# BeagleBone_Black_Wireless.net
KiCad netlist of a schematic drawn in EAGLE
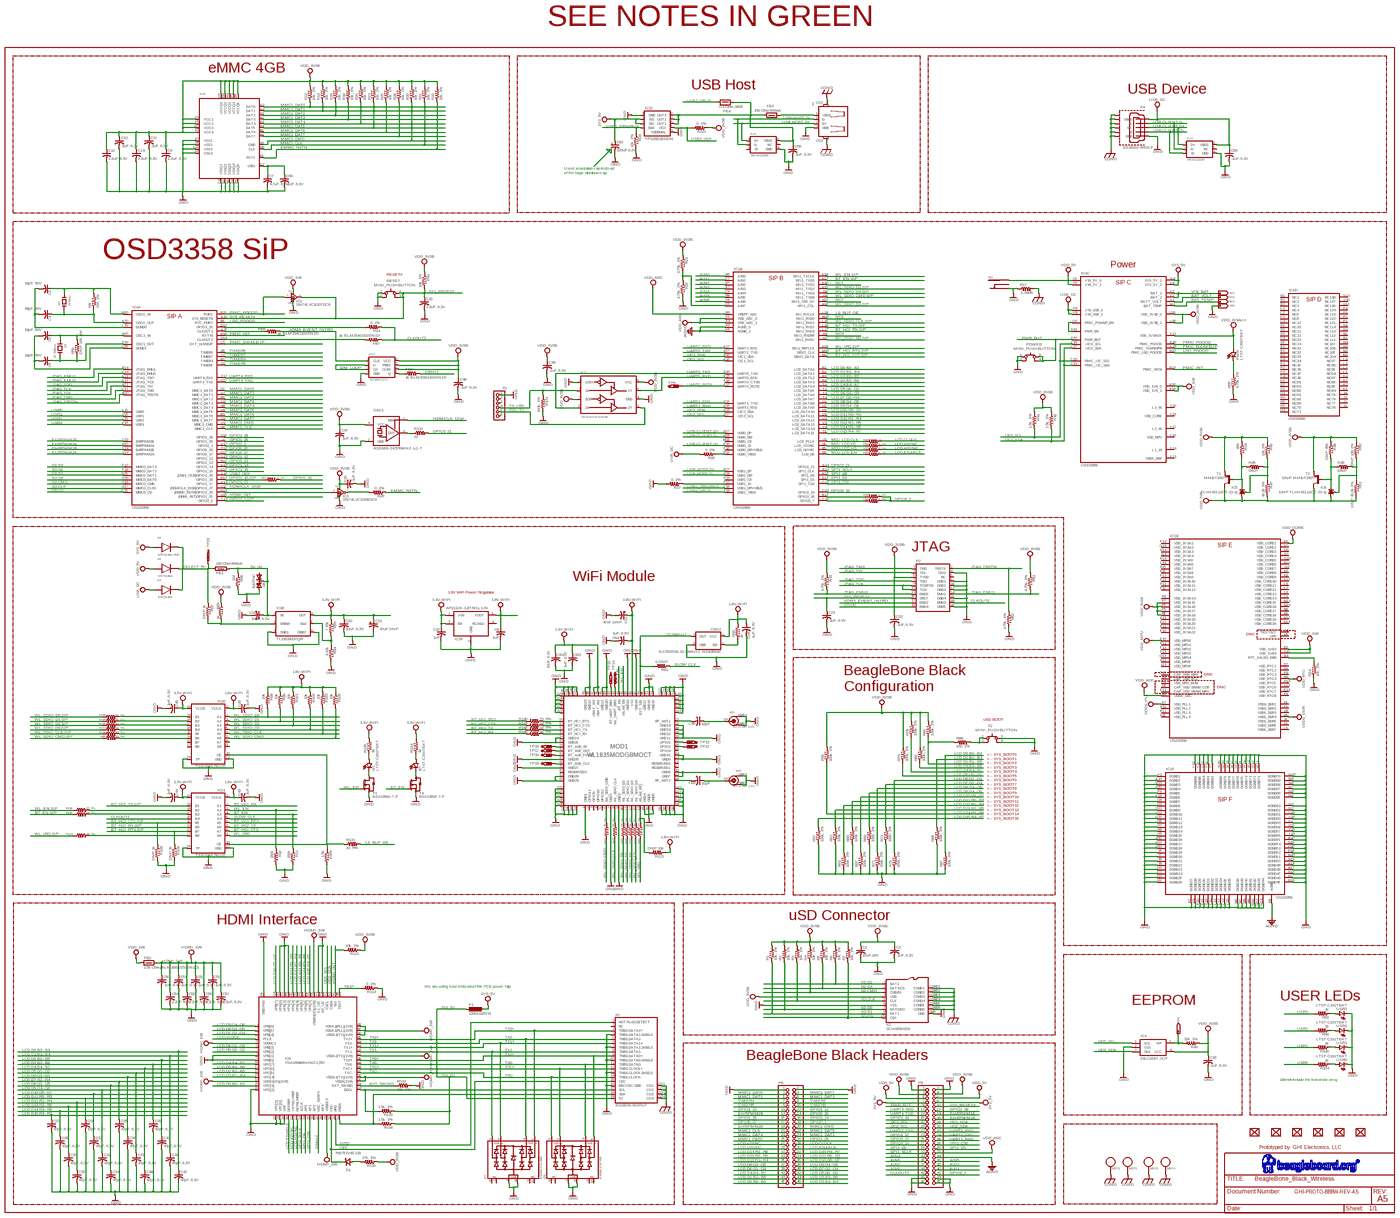
[diagram p0: schematic, sheet 1, overview]
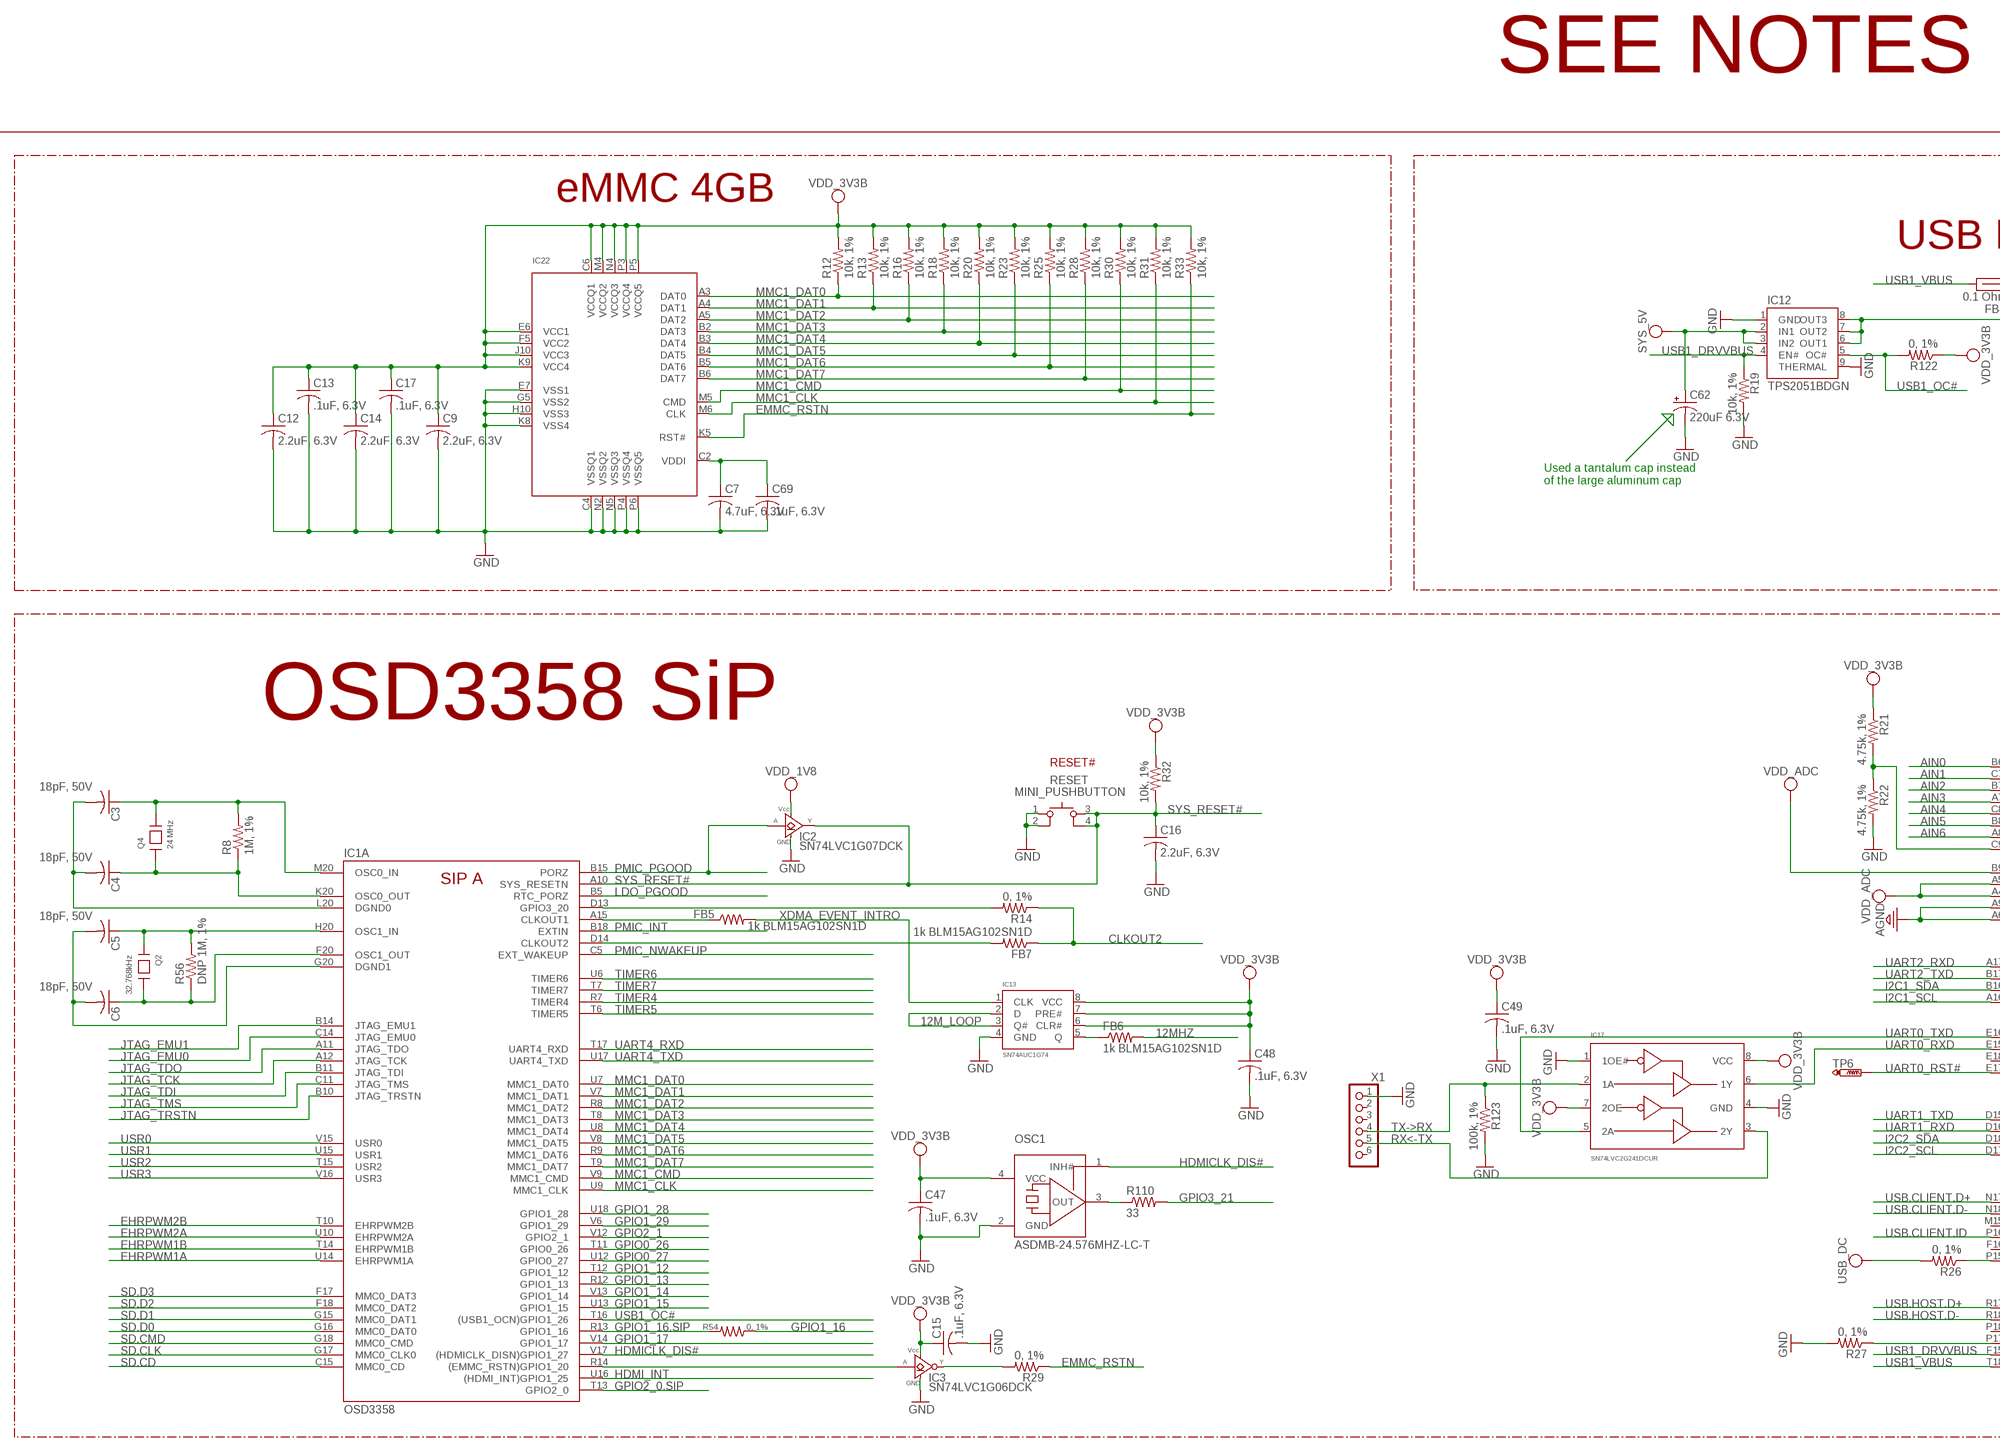
[diagram p1: schematic, sheet 1, part 1 of 4]
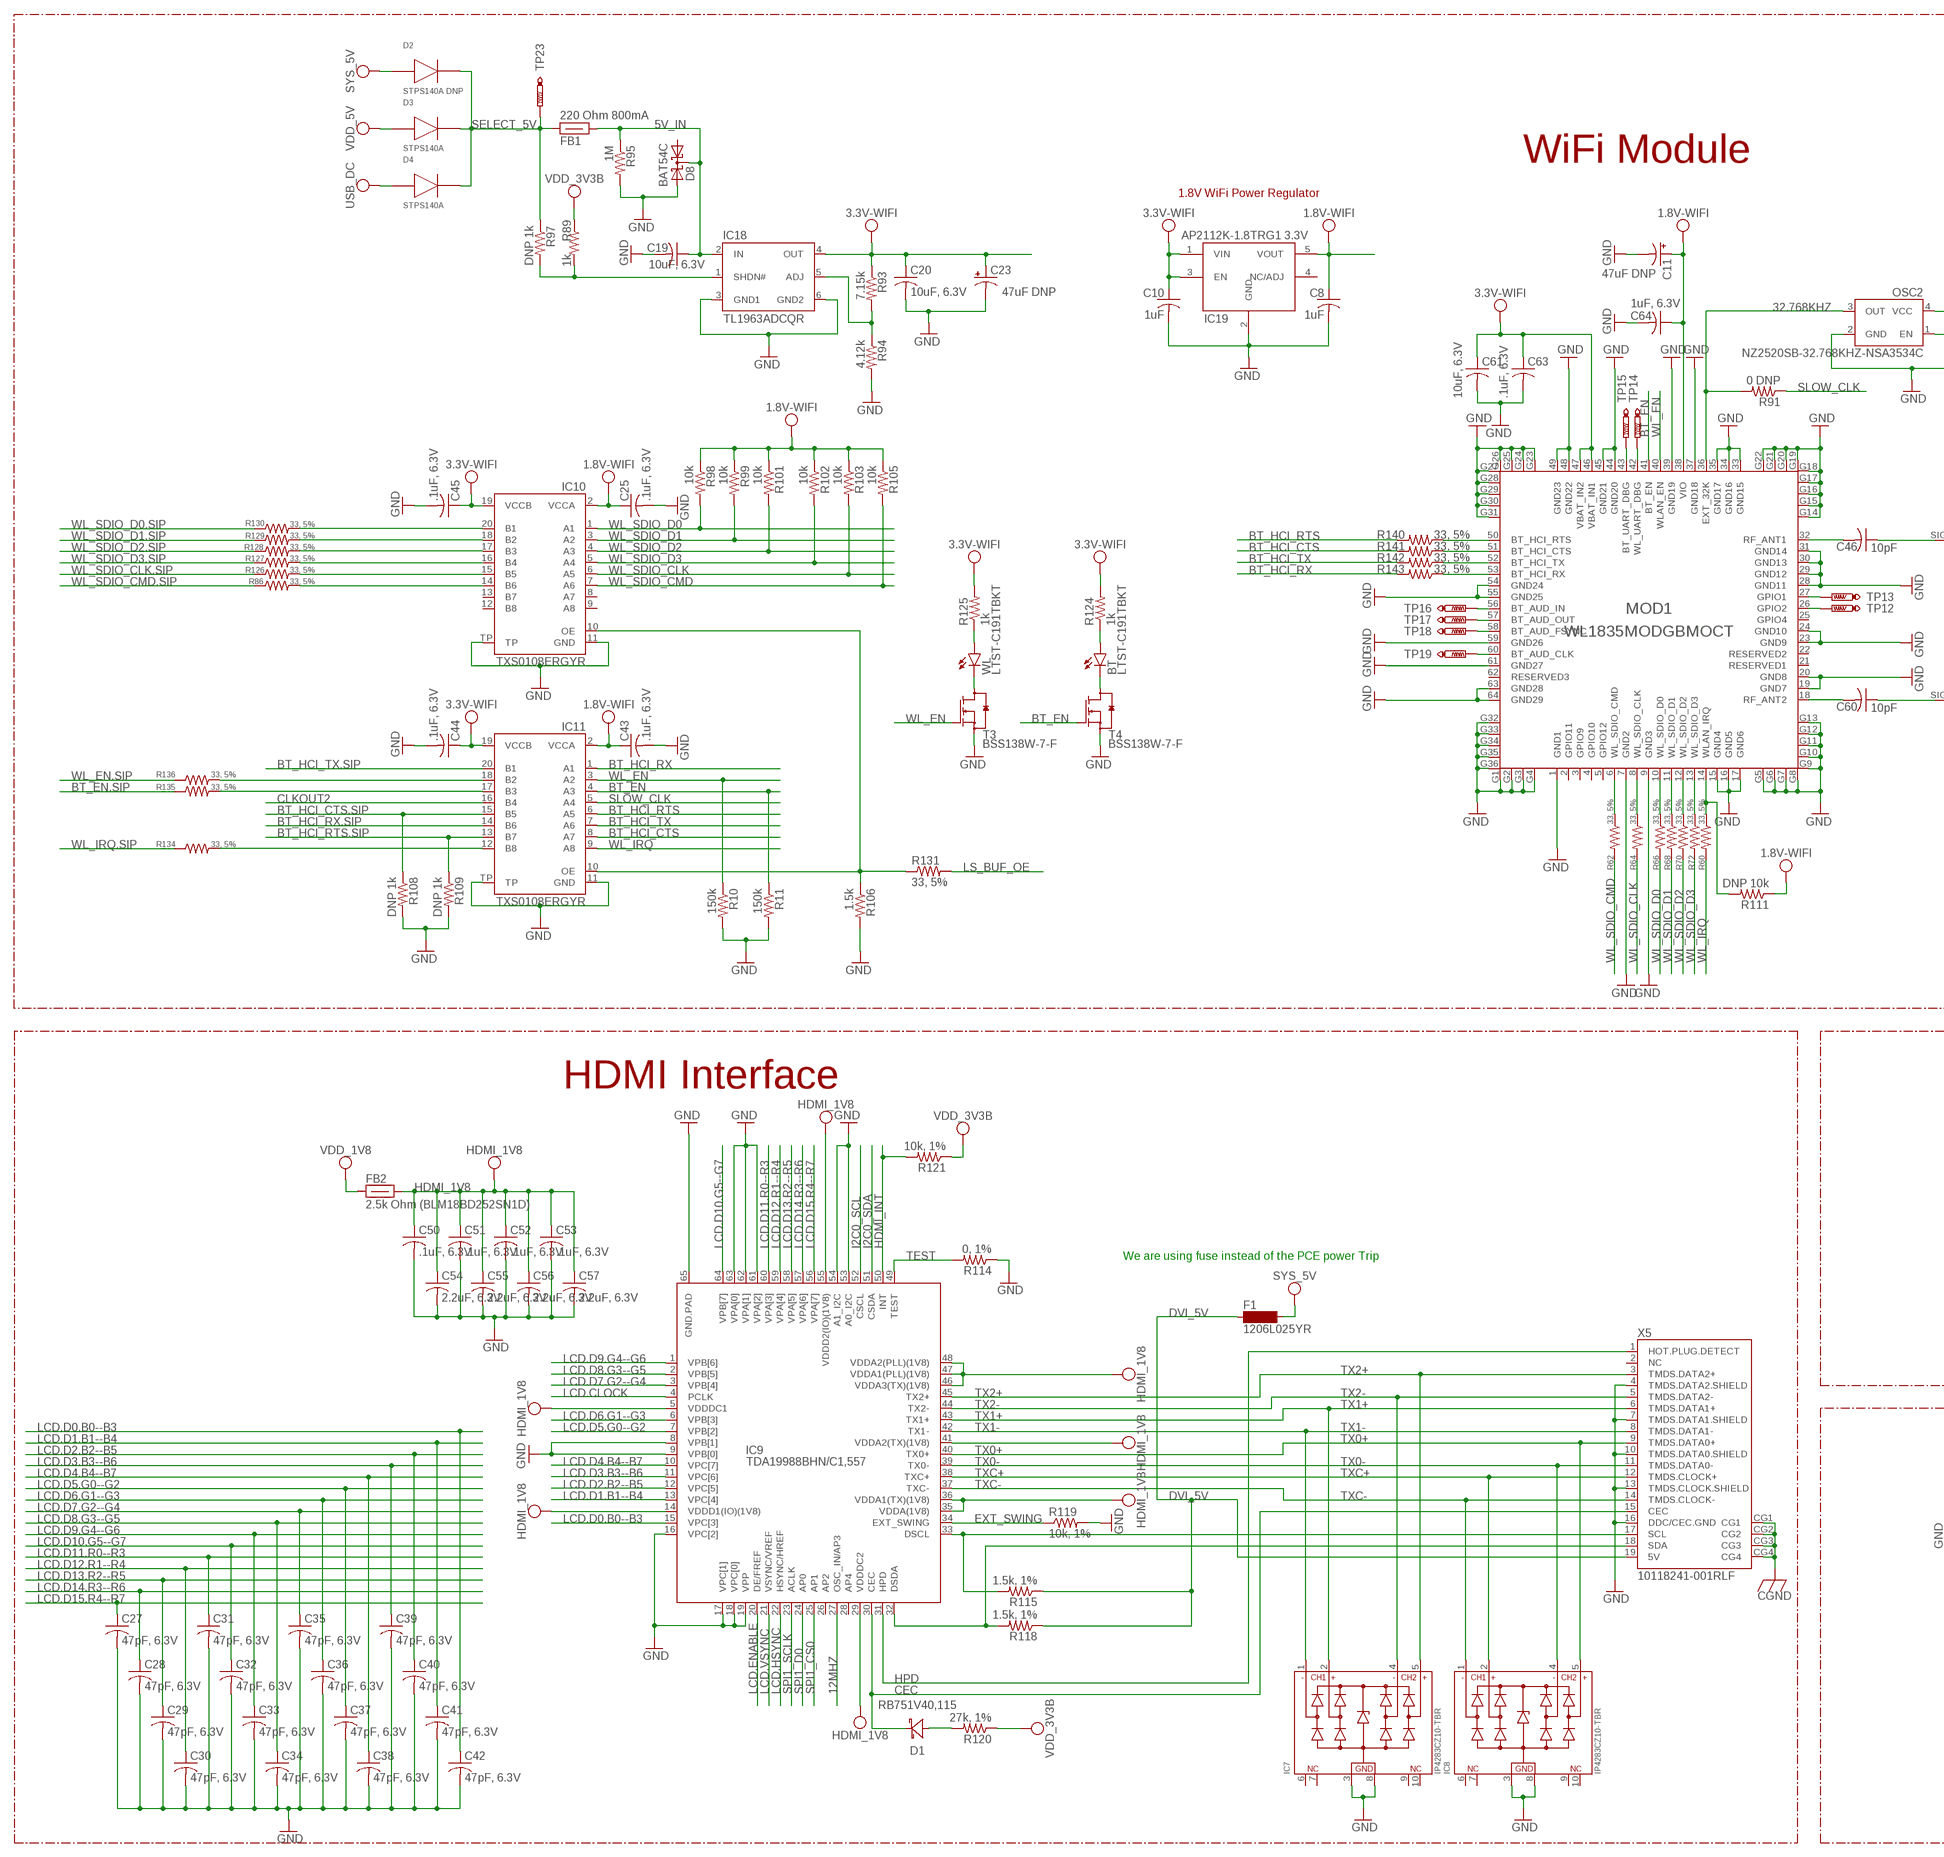
[diagram p2: schematic, sheet 1, part 2 of 4]
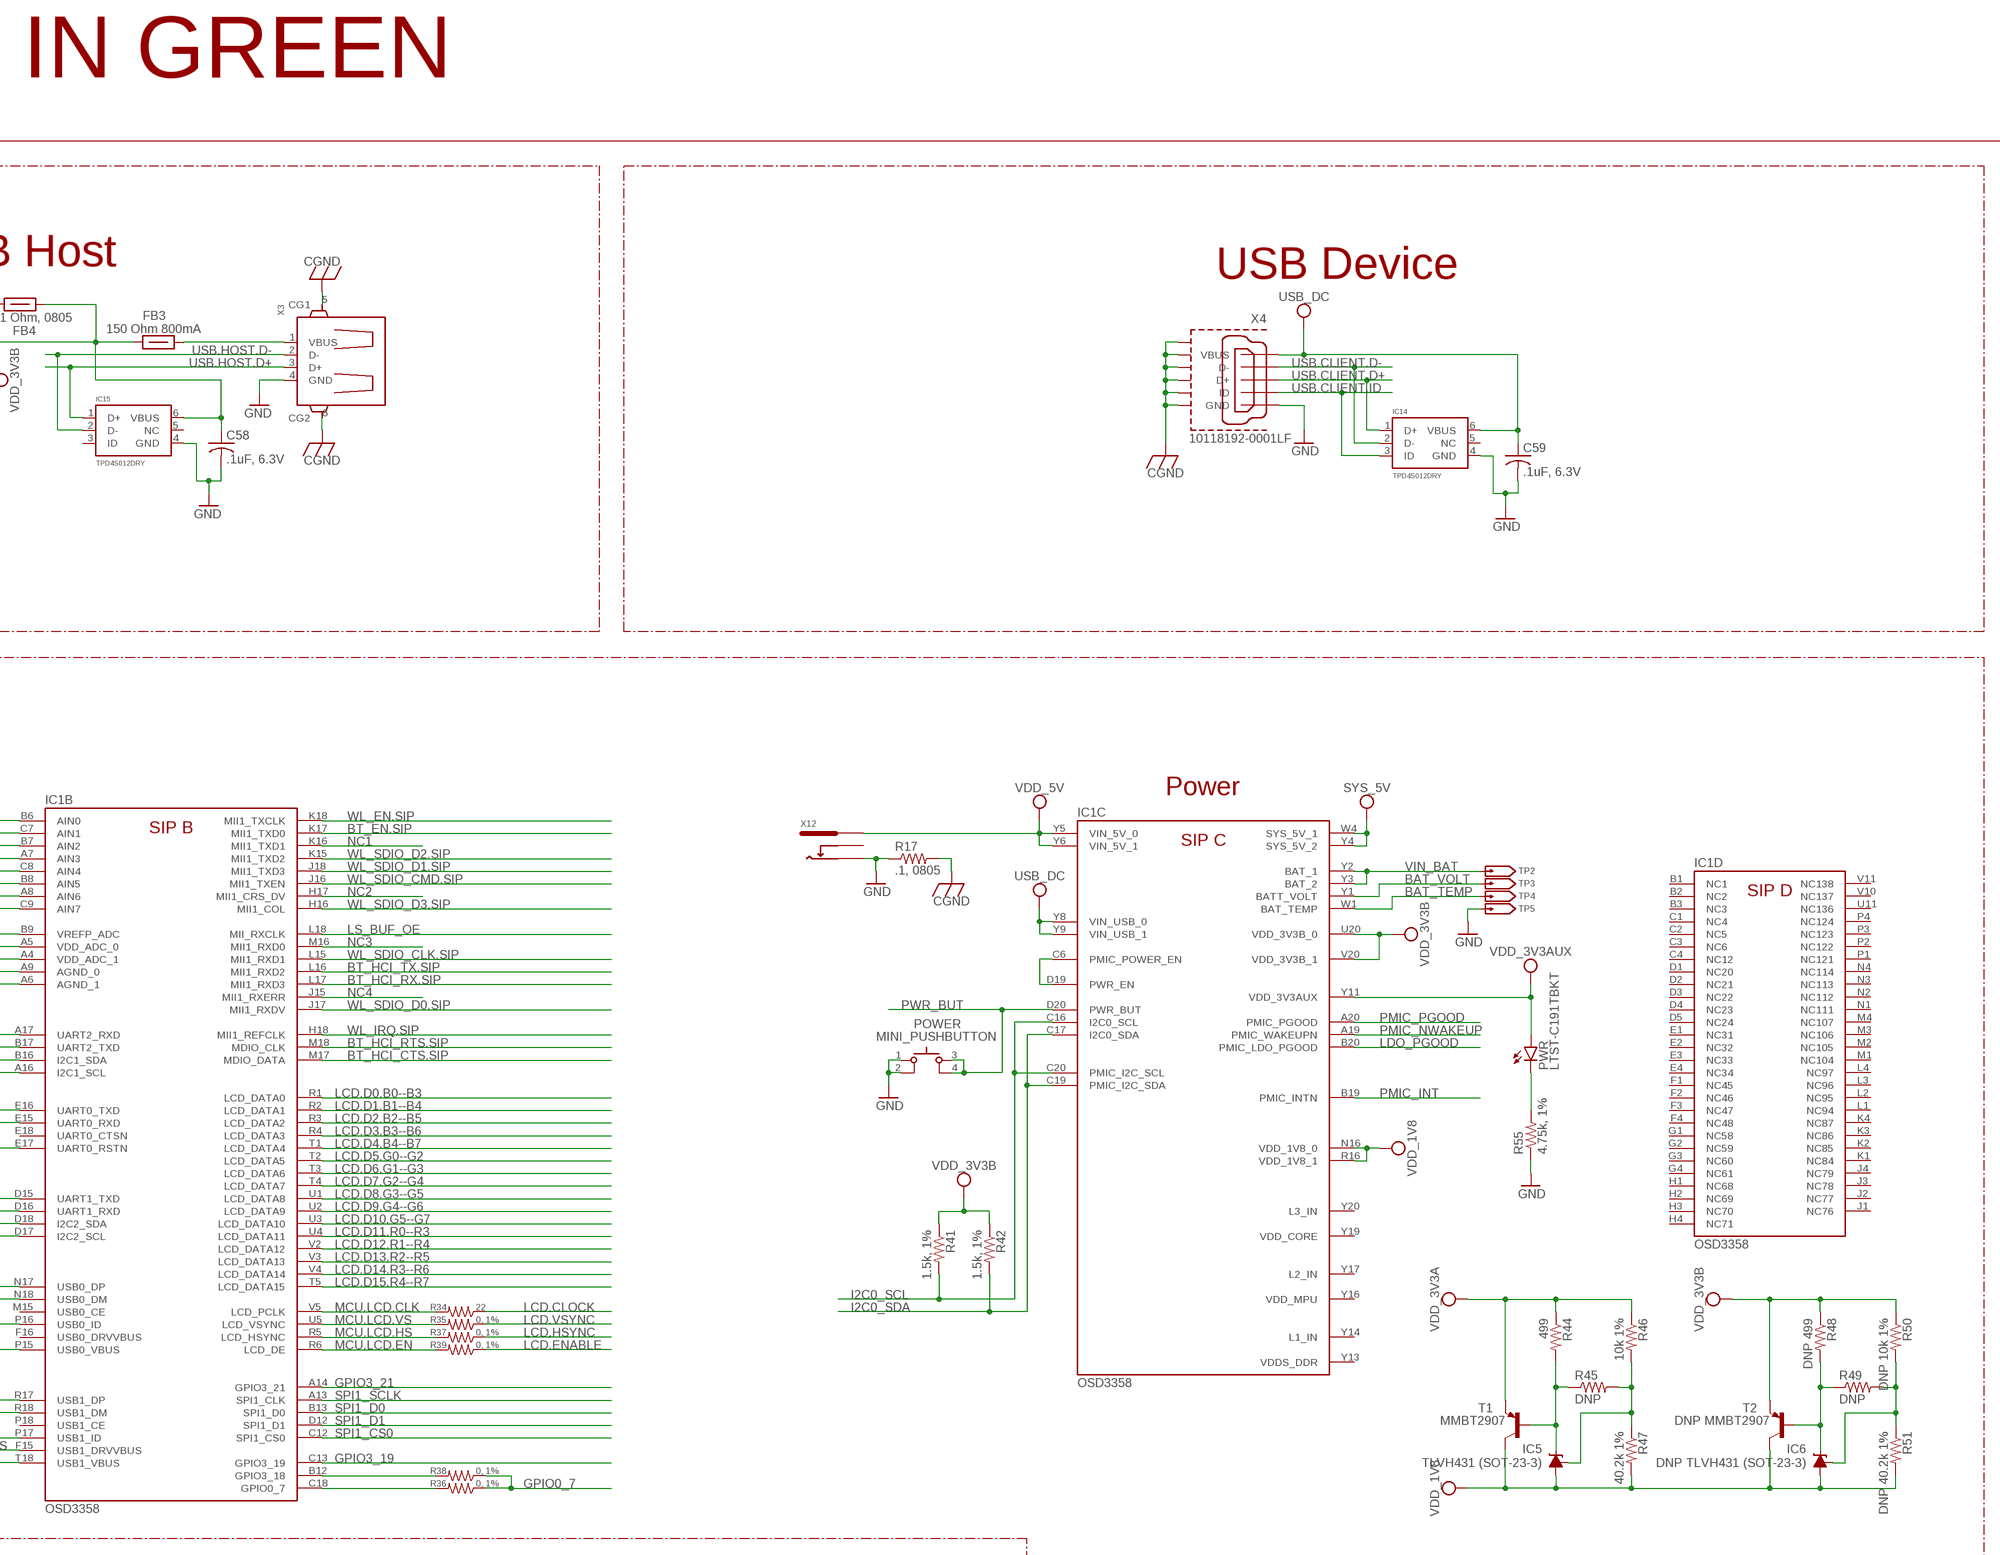
[diagram p3: schematic, sheet 1, part 3 of 4]
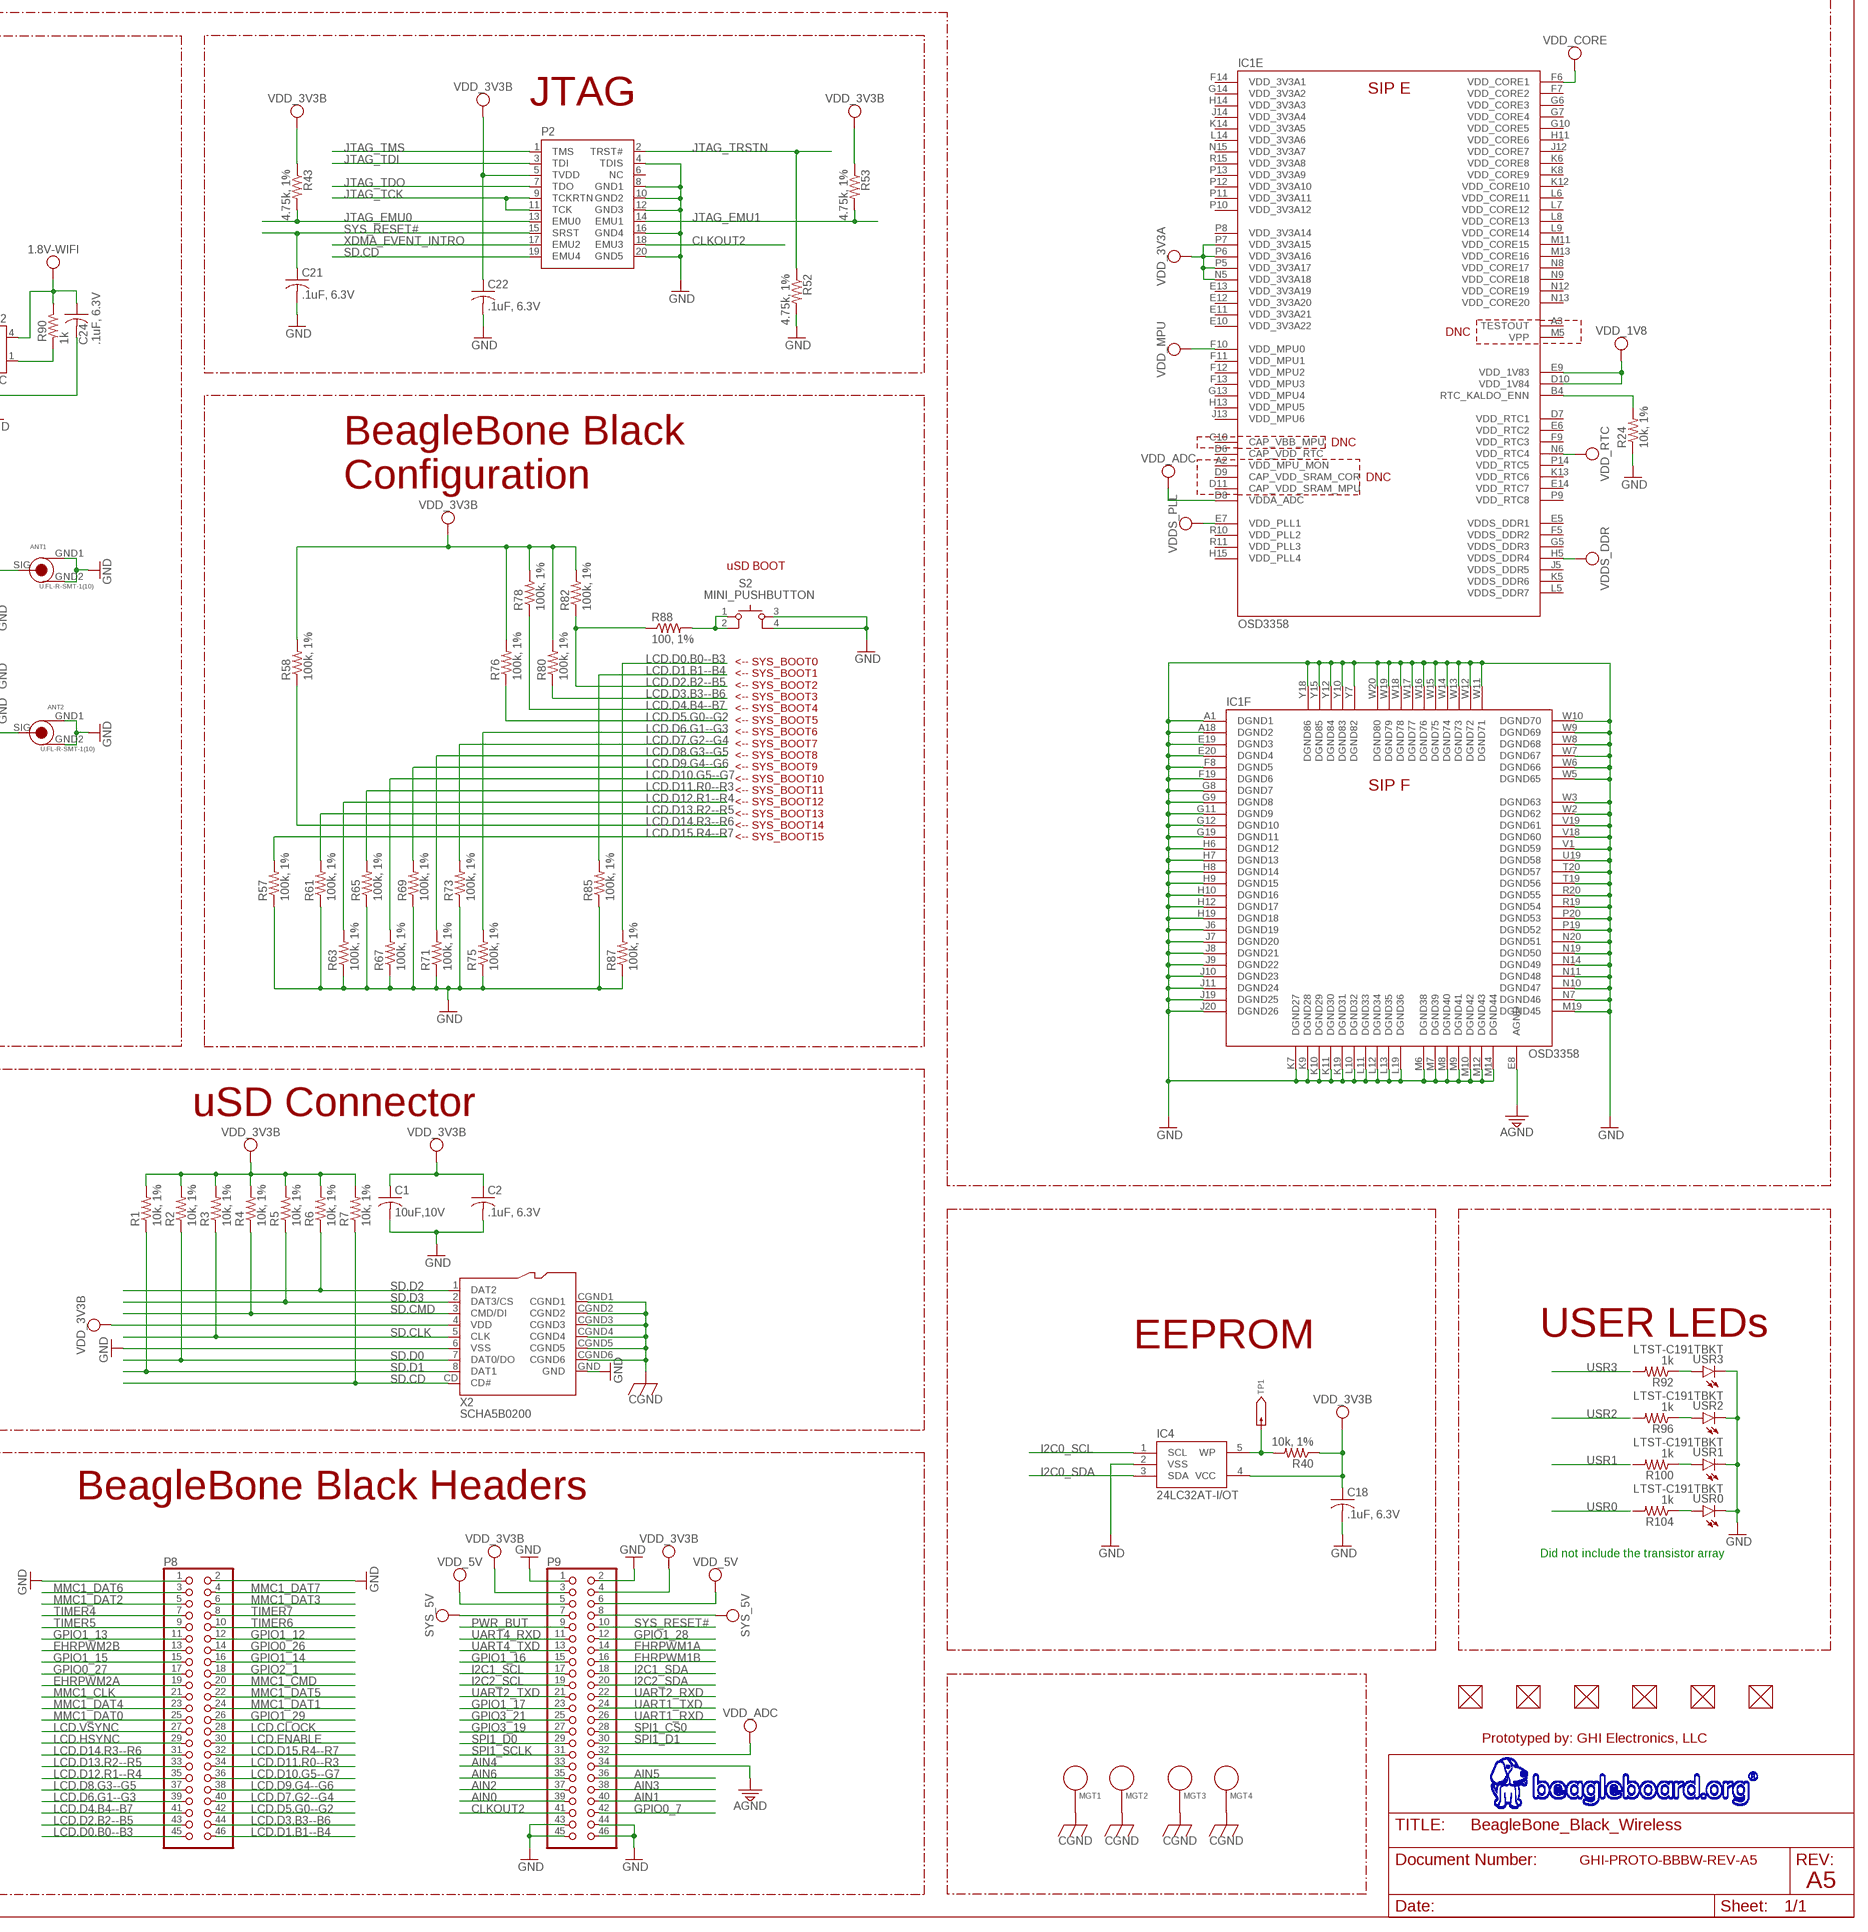
[diagram p4: schematic, sheet 1, part 4 of 4]

(export (version "E")
  (design (tool "Eeschema 10.0.6"))
  (components
    (comp (ref "ANT1")
      (value "U.FL-R-SMT-1(10)")
      (footprint "eagle-import:U.FL-R-SMT-1")
      (libsource (lib "eagle-import") (part "U.FL-R-SMT-1"))
    )
    (comp (ref "ANT2")
      (value "U.FL-R-SMT-1(10)")
      (footprint "eagle-import:U.FL-R-SMT-1")
      (libsource (lib "eagle-import") (part "U.FL-R-SMT-1"))
    )
    (comp (ref "BT")
      (value "LTST-C191TBKT")
      (footprint "eagle-import:0603-LED")
      (libsource (lib "eagle-import") (part "LED-(INCH)-0603"))
    )
    (comp (ref "C1")
      (value "10uF,10V")
      (footprint "eagle-import:C0603K")
      (libsource (lib "eagle-import") (part "C-USC0603K"))
    )
    (comp (ref "C2")
      (value ".1uF, 6.3V")
      (footprint "eagle-import:C0402K")
      (libsource (lib "eagle-import") (part "C-USC0402K"))
    )
    (comp (ref "C3")
      (value "18pF, 50V")
      (footprint "eagle-import:C0402K")
      (libsource (lib "eagle-import") (part "C-USC0402K"))
    )
    (comp (ref "C4")
      (value "18pF, 50V")
      (footprint "eagle-import:C0402K")
      (libsource (lib "eagle-import") (part "C-USC0402K"))
    )
    (comp (ref "C5")
      (value "18pF, 50V")
      (footprint "eagle-import:C0402K")
      (libsource (lib "eagle-import") (part "C-USC0402K"))
    )
    (comp (ref "C6")
      (value "18pF, 50V")
      (footprint "eagle-import:C0402K")
      (libsource (lib "eagle-import") (part "C-USC0402K"))
    )
    (comp (ref "C7")
      (value "4.7uF, 6.3V")
      (footprint "eagle-import:C0805K")
      (libsource (lib "eagle-import") (part "C-USC0805K"))
    )
    (comp (ref "C8")
      (value "1uF")
      (footprint "eagle-import:C0402K")
      (libsource (lib "eagle-import") (part "C-USC0402K"))
    )
    (comp (ref "C9")
      (value "2.2uF, 6.3V")
      (footprint "eagle-import:C0805K")
      (libsource (lib "eagle-import") (part "C-USC0805K"))
    )
    (comp (ref "C10")
      (value "1uF")
      (footprint "eagle-import:C0402K")
      (libsource (lib "eagle-import") (part "C-USC0402K"))
    )
    (comp (ref "C11")
      (value "47uF DNP")
      (footprint "eagle-import:CT3528")
      (libsource (lib "eagle-import") (part "CPOL-USCT3528"))
    )
    (comp (ref "C12")
      (value "2.2uF, 6.3V")
      (footprint "eagle-import:C0805K")
      (libsource (lib "eagle-import") (part "C-USC0805K"))
    )
    (comp (ref "C13")
      (value ".1uF, 6.3V")
      (footprint "eagle-import:C0402K")
      (libsource (lib "eagle-import") (part "C-USC0402K"))
    )
    (comp (ref "C14")
      (value "2.2uF, 6.3V")
      (footprint "eagle-import:C0805K")
      (libsource (lib "eagle-import") (part "C-USC0805K"))
    )
    (comp (ref "C15")
      (value ".1uF, 6.3V")
      (footprint "eagle-import:C0402K")
      (libsource (lib "eagle-import") (part "C-USC0402K"))
    )
    (comp (ref "C16")
      (value "2.2uF, 6.3V")
      (footprint "eagle-import:C0603K")
      (libsource (lib "eagle-import") (part "C-USC0603K"))
    )
    (comp (ref "C17")
      (value ".1uF, 6.3V")
      (footprint "eagle-import:C0402K")
      (libsource (lib "eagle-import") (part "C-USC0402K"))
    )
    (comp (ref "C18")
      (value ".1uF, 6.3V")
      (footprint "eagle-import:C0402K")
      (libsource (lib "eagle-import") (part "C-USC0402K"))
    )
    (comp (ref "C19")
      (value "10uF, 6.3V")
      (footprint "eagle-import:C0603K")
      (libsource (lib "eagle-import") (part "C-USC0603K"))
    )
    (comp (ref "C20")
      (value "10uF, 6.3V")
      (footprint "eagle-import:C0603K")
      (libsource (lib "eagle-import") (part "C-USC0603K"))
    )
    (comp (ref "C21")
      (value ".1uF, 6.3V")
      (footprint "eagle-import:C0402K")
      (libsource (lib "eagle-import") (part "C-USC0402K"))
    )
    (comp (ref "C22")
      (value ".1uF, 6.3V")
      (footprint "eagle-import:C0402K")
      (libsource (lib "eagle-import") (part "C-USC0402K"))
    )
    (comp (ref "C23")
      (value "47uF DNP")
      (footprint "eagle-import:CT3528")
      (libsource (lib "eagle-import") (part "CPOL-USCT3528"))
    )
    (comp (ref "C24")
      (value ".1uF, 6.3V")
      (footprint "eagle-import:C0402K")
      (libsource (lib "eagle-import") (part "C-USC0402K"))
    )
    (comp (ref "C25")
      (value ".1uF, 6.3V")
      (footprint "eagle-import:C0402K")
      (libsource (lib "eagle-import") (part "C-USC0402K"))
    )
    (comp (ref "C27")
      (value "47pF, 6.3V")
      (footprint "eagle-import:C0402K")
      (libsource (lib "eagle-import") (part "C-USC0402K"))
    )
    (comp (ref "C28")
      (value "47pF, 6.3V")
      (footprint "eagle-import:C0402K")
      (libsource (lib "eagle-import") (part "C-USC0402K"))
    )
    (comp (ref "C29")
      (value "47pF, 6.3V")
      (footprint "eagle-import:C0402K")
      (libsource (lib "eagle-import") (part "C-USC0402K"))
    )
    (comp (ref "C30")
      (value "47pF, 6.3V")
      (footprint "eagle-import:C0402K")
      (libsource (lib "eagle-import") (part "C-USC0402K"))
    )
    (comp (ref "C31")
      (value "47pF, 6.3V")
      (footprint "eagle-import:C0402K")
      (libsource (lib "eagle-import") (part "C-USC0402K"))
    )
    (comp (ref "C32")
      (value "47pF, 6.3V")
      (footprint "eagle-import:C0402K")
      (libsource (lib "eagle-import") (part "C-USC0402K"))
    )
    (comp (ref "C33")
      (value "47pF, 6.3V")
      (footprint "eagle-import:C0402K")
      (libsource (lib "eagle-import") (part "C-USC0402K"))
    )
    (comp (ref "C34")
      (value "47pF, 6.3V")
      (footprint "eagle-import:C0402K")
      (libsource (lib "eagle-import") (part "C-USC0402K"))
    )
    (comp (ref "C35")
      (value "47pF, 6.3V")
      (footprint "eagle-import:C0402K")
      (libsource (lib "eagle-import") (part "C-USC0402K"))
    )
    (comp (ref "C36")
      (value "47pF, 6.3V")
      (footprint "eagle-import:C0402K")
      (libsource (lib "eagle-import") (part "C-USC0402K"))
    )
    (comp (ref "C37")
      (value "47pF, 6.3V")
      (footprint "eagle-import:C0402K")
      (libsource (lib "eagle-import") (part "C-USC0402K"))
    )
    (comp (ref "C38")
      (value "47pF, 6.3V")
      (footprint "eagle-import:C0402K")
      (libsource (lib "eagle-import") (part "C-USC0402K"))
    )
    (comp (ref "C39")
      (value "47pF, 6.3V")
      (footprint "eagle-import:C0402K")
      (libsource (lib "eagle-import") (part "C-USC0402K"))
    )
    (comp (ref "C40")
      (value "47pF, 6.3V")
      (footprint "eagle-import:C0402K")
      (libsource (lib "eagle-import") (part "C-USC0402K"))
    )
    (comp (ref "C41")
      (value "47pF, 6.3V")
      (footprint "eagle-import:C0402K")
      (libsource (lib "eagle-import") (part "C-USC0402K"))
    )
    (comp (ref "C42")
      (value "47pF, 6.3V")
      (footprint "eagle-import:C0402K")
      (libsource (lib "eagle-import") (part "C-USC0402K"))
    )
    (comp (ref "C43")
      (value ".1uF, 6.3V")
      (footprint "eagle-import:C0402K")
      (libsource (lib "eagle-import") (part "C-USC0402K"))
    )
    (comp (ref "C44")
      (value ".1uF, 6.3V")
      (footprint "eagle-import:C0402K")
      (libsource (lib "eagle-import") (part "C-USC0402K"))
    )
    (comp (ref "C45")
      (value ".1uF, 6.3V")
      (footprint "eagle-import:C0402K")
      (libsource (lib "eagle-import") (part "C-USC0402K"))
    )
    (comp (ref "C46")
      (value "10pF")
      (footprint "eagle-import:C0402K")
      (libsource (lib "eagle-import") (part "C-USC0402K"))
    )
    (comp (ref "C47")
      (value ".1uF, 6.3V")
      (footprint "eagle-import:C0402K")
      (libsource (lib "eagle-import") (part "C-USC0402K"))
    )
    (comp (ref "C48")
      (value ".1uF, 6.3V")
      (footprint "eagle-import:C0402K")
      (libsource (lib "eagle-import") (part "C-USC0402K"))
    )
    (comp (ref "C49")
      (value ".1uF, 6.3V")
      (footprint "eagle-import:C0402K")
      (libsource (lib "eagle-import") (part "C-USC0402K"))
    )
    (comp (ref "C50")
      (value ".1uF, 6.3V")
      (footprint "eagle-import:C0402K")
      (libsource (lib "eagle-import") (part "C-USC0402K"))
    )
    (comp (ref "C51")
      (value ".1uF, 6.3V")
      (footprint "eagle-import:C0402K")
      (libsource (lib "eagle-import") (part "C-USC0402K"))
    )
    (comp (ref "C52")
      (value ".1uF, 6.3V")
      (footprint "eagle-import:C0402K")
      (libsource (lib "eagle-import") (part "C-USC0402K"))
    )
    (comp (ref "C53")
      (value ".1uF, 6.3V")
      (footprint "eagle-import:C0402K")
      (libsource (lib "eagle-import") (part "C-USC0402K"))
    )
    (comp (ref "C54")
      (value "2.2uF, 6.3V")
      (footprint "eagle-import:C0603K")
      (libsource (lib "eagle-import") (part "C-USC0603K"))
    )
    (comp (ref "C55")
      (value "2.2uF, 6.3V")
      (footprint "eagle-import:C0603K")
      (libsource (lib "eagle-import") (part "C-USC0603K"))
    )
    (comp (ref "C56")
      (value "2.2uF, 6.3V")
      (footprint "eagle-import:C0603K")
      (libsource (lib "eagle-import") (part "C-USC0603K"))
    )
    (comp (ref "C57")
      (value "2.2uF, 6.3V")
      (footprint "eagle-import:C0603K")
      (libsource (lib "eagle-import") (part "C-USC0603K"))
    )
    (comp (ref "C58")
      (value ".1uF, 6.3V")
      (footprint "eagle-import:C0402K")
      (libsource (lib "eagle-import") (part "C-USC0402K"))
    )
    (comp (ref "C59")
      (value ".1uF, 6.3V")
      (footprint "eagle-import:C0402K")
      (libsource (lib "eagle-import") (part "C-USC0402K"))
    )
    (comp (ref "C60")
      (value "10pF")
      (footprint "eagle-import:C0402K")
      (libsource (lib "eagle-import") (part "C-USC0402K"))
    )
    (comp (ref "C61")
      (value "10uF, 6.3V")
      (footprint "eagle-import:C0603K")
      (libsource (lib "eagle-import") (part "C-USC0603K"))
    )
    (comp (ref "C62")
      (value "220uF 6.3V")
      (footprint "eagle-import:D_7343-31W")
      (libsource (lib "eagle-import") (part "CPOL-USD/7343-31W"))
    )
    (comp (ref "C63")
      (value ".1uF, 6.3V")
      (footprint "eagle-import:C0402K")
      (libsource (lib "eagle-import") (part "C-USC0402K"))
    )
    (comp (ref "C64")
      (value "1uF, 6.3V")
      (footprint "eagle-import:C0402K")
      (libsource (lib "eagle-import") (part "C-USC0402K"))
    )
    (comp (ref "C69")
      (value ".1uF, 6.3V")
      (footprint "eagle-import:C0402K")
      (libsource (lib "eagle-import") (part "C-USC0402K"))
    )
    (comp (ref "D1")
      (value "RB751V40,115")
      (footprint "eagle-import:SOD323(NXP)REFLOW")
      (libsource (lib "eagle-import") (part "DIODE-SCHOTTKY-(NXP)-SOD323-(REFLOW)"))
    )
    (comp (ref "D2")
      (value "STPS140A DNP")
      (footprint "eagle-import:DIODE_SMA")
      (libsource (lib "eagle-import") (part "DIODE_SMA"))
    )
    (comp (ref "D3")
      (value "STPS140A")
      (footprint "eagle-import:DIODE_SMA")
      (libsource (lib "eagle-import") (part "DIODE_SMA"))
    )
    (comp (ref "D4")
      (value "STPS140A")
      (footprint "eagle-import:DIODE_SMA")
      (libsource (lib "eagle-import") (part "DIODE_SMA"))
    )
    (comp (ref "D8")
      (value "BAT54C")
      (footprint "eagle-import:SOT23")
      (libsource (lib "eagle-import") (part "BAT54C"))
    )
    (comp (ref "F1")
      (value "1206L025YR")
      (footprint "eagle-import:SM-1206")
      (libsource (lib "eagle-import") (part "SM-1206"))
    )
    (comp (ref "FB1")
      (value "220 Ohm 800mA")
      (footprint "eagle-import:0805-RESISTOR")
      (libsource (lib "eagle-import") (part "FB-(INCH)-0805"))
    )
    (comp (ref "FB2")
      (value "2.5k Ohm (BLM18BD252SN1D)")
      (footprint "eagle-import:0805-RESISTOR")
      (libsource (lib "eagle-import") (part "FB-(INCH)-0805"))
    )
    (comp (ref "FB3")
      (value "150 Ohm 800mA")
      (footprint "eagle-import:0805-RESISTOR")
      (libsource (lib "eagle-import") (part "FB-(INCH)-0805"))
    )
    (comp (ref "FB4")
      (value "0.1 Ohm, 0805")
      (footprint "eagle-import:0805-RESISTOR")
      (libsource (lib "eagle-import") (part "FB-(INCH)-0805"))
    )
    (comp (ref "FB5")
      (value "1k BLM15AG102SN1D")
      (footprint "eagle-import:R0402")
      (libsource (lib "eagle-import") (part "R-US_R0402"))
    )
    (comp (ref "FB6")
      (value "1k BLM15AG102SN1D")
      (footprint "eagle-import:R0402")
      (libsource (lib "eagle-import") (part "R-US_R0402"))
    )
    (comp (ref "FB7")
      (value "1k BLM15AG102SN1D")
      (footprint "eagle-import:R0402")
      (libsource (lib "eagle-import") (part "R-US_R0402"))
    )
    (comp (ref "FUD1")
      (value "FIDUCIAL")
      (footprint "eagle-import:FIDUCIAL_40MIL")
      (libsource (lib "eagle-import") (part "FIDUCIAL"))
    )
    (comp (ref "FUD2")
      (value "FIDUCIAL")
      (footprint "eagle-import:FIDUCIAL_40MIL")
      (libsource (lib "eagle-import") (part "FIDUCIAL"))
    )
    (comp (ref "FUD3")
      (value "FIDUCIAL")
      (footprint "eagle-import:FIDUCIAL_40MIL")
      (libsource (lib "eagle-import") (part "FIDUCIAL"))
    )
    (comp (ref "FUD4")
      (value "FIDUCIAL")
      (footprint "eagle-import:FIDUCIAL_40MIL")
      (libsource (lib "eagle-import") (part "FIDUCIAL"))
    )
    (comp (ref "FUD5")
      (value "FIDUCIAL")
      (footprint "eagle-import:FIDUCIAL_40MIL")
      (libsource (lib "eagle-import") (part "FIDUCIAL"))
    )
    (comp (ref "FUD6")
      (value "FIDUCIAL")
      (footprint "eagle-import:FIDUCIAL_40MIL")
      (libsource (lib "eagle-import") (part "FIDUCIAL"))
    )
    (comp (ref "IC1")
      (value "OSD3358")
      (footprint "eagle-import:OSD3358")
      (libsource (lib "eagle-import") (part "SIP1000"))
    )
    (comp (ref "IC2")
      (value "SN74LVC1G07DCK")
      (footprint "eagle-import:SC70(TI-DCK)")
      (libsource (lib "eagle-import") (part "SN74LVC1G07DCK"))
    )
    (comp (ref "IC3")
      (value "SN74LVC1G06DCK")
      (footprint "eagle-import:SC70(TI-DCK)")
      (libsource (lib "eagle-import") (part "SN74LVC1G06DCK"))
    )
    (comp (ref "IC4")
      (value "24LC32AT-I/OT")
      (footprint "eagle-import:SOT23-5(MICROCHIP)")
      (libsource (lib "eagle-import") (part "24LC32A{dblquote}"))
    )
    (comp (ref "IC5")
      (value "TLVH431 (SOT-23-3)")
      (footprint "eagle-import:DBZ_R-PDSO-G3")
      (fields (field (name "MF") "TEXAS INSTRUMENT CONNECTORS") (field (name "MPN") "LM4041DIDBZR"))
      (libsource (lib "eagle-import") (part "LM4041IDBZD"))
    )
    (comp (ref "IC6")
      (value "DNP TLVH431 (SOT-23-3)")
      (footprint "eagle-import:DBZ_R-PDSO-G3")
      (fields (field (name "MF") "TEXAS INSTRUMENT CONNECTORS") (field (name "MPN") "LM4041DIDBZR"))
      (libsource (lib "eagle-import") (part "LM4041IDBZD"))
    )
    (comp (ref "IC7")
      (value "IP4283CZ10-TBR")
      (footprint "eagle-import:SOT1176-1(NXP)")
      (libsource (lib "eagle-import") (part "IP4283CZ10IP4283CZ10-TBR"))
    )
    (comp (ref "IC8")
      (value "IP4283CZ10-TBR")
      (footprint "eagle-import:SOT1176-1(NXP)")
      (libsource (lib "eagle-import") (part "IP4283CZ10IP4283CZ10-TBR"))
    )
    (comp (ref "IC9")
      (value "TDA19988BHN/C1,557")
      (footprint "eagle-import:SOT804-4(NXP)")
      (libsource (lib "eagle-import") (part "TDA19988BHN/C1"))
    )
    (comp (ref "IC10")
      (value "TXS0108ERGYR")
      (footprint "eagle-import:R-PVQFN-N20(TI)")
      (libsource (lib "eagle-import") (part "TXS0108ERGYR"))
    )
    (comp (ref "IC11")
      (value "TXS0108ERGYR")
      (footprint "eagle-import:R-PVQFN-N20(TI)")
      (libsource (lib "eagle-import") (part "TXS0108ERGYR"))
    )
    (comp (ref "IC12")
      (value "TPS2051BDGN")
      (footprint "eagle-import:MSOP-POWER.PAD-8(TI)")
      (libsource (lib "eagle-import") (part "TPS2051B"))
    )
    (comp (ref "IC13")
      (value "SN74AUC1G74")
      (footprint "eagle-import:SM8-8(TI)")
      (libsource (lib "eagle-import") (part "SN74AUC1G74"))
    )
    (comp (ref "IC14")
      (value "TPD4S012DRY")
      (footprint "eagle-import:SON-6(TI)-DRY")
      (libsource (lib "eagle-import") (part "TPD4S012DRYR"))
    )
    (comp (ref "IC15")
      (value "TPD4S012DRY")
      (footprint "eagle-import:SON-6(TI)-DRY")
      (libsource (lib "eagle-import") (part "TPD4S012DRYR"))
    )
    (comp (ref "IC17")
      (value "SN74LVC2G241DCUR")
      (footprint "eagle-import:VSSOP8(TI)")
      (libsource (lib "eagle-import") (part "SN74LVC2G241DCUR"))
    )
    (comp (ref "IC18")
      (value "TL1963ADCQR")
      (footprint "eagle-import:SOT-223(DCQ_R-PDSO-G6_TI)")
      (libsource (lib "eagle-import") (part "TL1963A"))
    )
    (comp (ref "IC19")
      (value "AP2112K-1.8TRG1 3.3V")
      (footprint "eagle-import:SOT23-5")
      (libsource (lib "eagle-import") (part "5PIN_REG"))
    )
    (comp (ref "IC22")
      (value "EMMC04G-S100-B08U")
      (footprint "eagle-import:MICRON_EMMC_153")
      (libsource (lib "eagle-import") (part "EMMC04G-S100-B08U"))
    )
    (comp (ref "MGT1")
      (value "MOUNTING_HOLE")
      (footprint "eagle-import:MOUNTING_HOLE")
      (libsource (lib "eagle-import") (part "MOUNTING_HOLE"))
    )
    (comp (ref "MGT2")
      (value "MOUNTING_HOLE")
      (footprint "eagle-import:MOUNTING_HOLE")
      (libsource (lib "eagle-import") (part "MOUNTING_HOLE"))
    )
    (comp (ref "MGT3")
      (value "MOUNTING_HOLE")
      (footprint "eagle-import:MOUNTING_HOLE")
      (libsource (lib "eagle-import") (part "MOUNTING_HOLE"))
    )
    (comp (ref "MGT4")
      (value "MOUNTING_HOLE")
      (footprint "eagle-import:MOUNTING_HOLE")
      (libsource (lib "eagle-import") (part "MOUNTING_HOLE"))
    )
    (comp (ref "MOD1")
      (value "WL1835MODGBMOCT")
      (footprint "eagle-import:MOC-100(TI)")
      (libsource (lib "eagle-import") (part "WL1835MOD"))
    )
    (comp (ref "OSC1")
      (value "ASDMB-24.576MHZ-LC-T")
      (footprint "eagle-import:OSCILLATOR-2.5X2.0-BBB")
      (libsource (lib "eagle-import") (part "OSC-2.5X2.0"))
    )
    (comp (ref "OSC2")
      (value "NZ2520SB-32.768KHZ-NSA3534C")
      (footprint "eagle-import:NZ2520S")
      (libsource (lib "eagle-import") (part "OSCILLATOR"))
    )
    (comp (ref "P2")
      (value "JTAG")
      (footprint "eagle-import:JTAG")
      (libsource (lib "eagle-import") (part "JTAG"))
    )
    (comp (ref "P8")
      (value "HEADER-2X23-(INCH)-0.1-TH")
      (footprint "eagle-import:TH-2X23")
      (libsource (lib "eagle-import") (part "HEADER-2X23-(INCH)-0.1-TH"))
    )
    (comp (ref "P9")
      (value "HEADER-2X23-(INCH)-0.1-TH")
      (footprint "eagle-import:TH-2X23")
      (libsource (lib "eagle-import") (part "HEADER-2X23-(INCH)-0.1-TH"))
    )
    (comp (ref "POWER")
      (value "MINI_PUSHBUTTON")
      (footprint "eagle-import:MINI_PUSHBUTTON")
      (libsource (lib "eagle-import") (part "MINI_PUSHBUTTON"))
    )
    (comp (ref "PWR")
      (value "LTST-C191TBKT")
      (footprint "eagle-import:0603-LED")
      (libsource (lib "eagle-import") (part "LED-(INCH)-0603"))
    )
    (comp (ref "Q2")
      (value "32.768kHz")
      (footprint "eagle-import:CRYSTAL_3.2X1.5")
      (libsource (lib "eagle-import") (part "CRYSTAL_3.2X1.5"))
    )
    (comp (ref "Q4")
      (value "24 MHz")
      (footprint "eagle-import:CRYSTAL_5X3.2MM")
      (libsource (lib "eagle-import") (part "CRYSTAL_5X3.2MM"))
    )
    (comp (ref "R1")
      (value "10k, 1%")
      (footprint "eagle-import:R0402")
      (libsource (lib "eagle-import") (part "R-US_R0402"))
    )
    (comp (ref "R2")
      (value "10k, 1%")
      (footprint "eagle-import:R0402")
      (libsource (lib "eagle-import") (part "R-US_R0402"))
    )
    (comp (ref "R3")
      (value "10k, 1%")
      (footprint "eagle-import:R0402")
      (libsource (lib "eagle-import") (part "R-US_R0402"))
    )
    (comp (ref "R4")
      (value "10k, 1%")
      (footprint "eagle-import:R0402")
      (libsource (lib "eagle-import") (part "R-US_R0402"))
    )
    (comp (ref "R5")
      (value "10k, 1%")
      (footprint "eagle-import:R0402")
      (libsource (lib "eagle-import") (part "R-US_R0402"))
    )
    (comp (ref "R6")
      (value "10k, 1%")
      (footprint "eagle-import:R0402")
      (libsource (lib "eagle-import") (part "R-US_R0402"))
    )
    (comp (ref "R7")
      (value "10k, 1%")
      (footprint "eagle-import:R0402")
      (libsource (lib "eagle-import") (part "R-US_R0402"))
    )
    (comp (ref "R8")
      (value "1M, 1%")
      (footprint "eagle-import:R0402")
      (libsource (lib "eagle-import") (part "R-US_R0402"))
    )
    (comp (ref "R10")
      (value "150k")
      (footprint "eagle-import:R0402")
      (libsource (lib "eagle-import") (part "R-US_R0402"))
    )
    (comp (ref "R11")
      (value "150k")
      (footprint "eagle-import:R0402")
      (libsource (lib "eagle-import") (part "R-US_R0402"))
    )
    (comp (ref "R12")
      (value "10k, 1%")
      (footprint "eagle-import:R0402")
      (libsource (lib "eagle-import") (part "R-US_R0402"))
    )
    (comp (ref "R13")
      (value "10k, 1%")
      (footprint "eagle-import:R0402")
      (libsource (lib "eagle-import") (part "R-US_R0402"))
    )
    (comp (ref "R14")
      (value "0, 1%")
      (footprint "eagle-import:R0402")
      (libsource (lib "eagle-import") (part "R-US_R0402"))
    )
    (comp (ref "R16")
      (value "10k, 1%")
      (footprint "eagle-import:R0402")
      (libsource (lib "eagle-import") (part "R-US_R0402"))
    )
    (comp (ref "R17")
      (value ".1, 0805")
      (footprint "eagle-import:R0805")
      (libsource (lib "eagle-import") (part "R-US_R0805"))
    )
    (comp (ref "R18")
      (value "10k, 1%")
      (footprint "eagle-import:R0402")
      (libsource (lib "eagle-import") (part "R-US_R0402"))
    )
    (comp (ref "R19")
      (value "10k, 1%")
      (footprint "eagle-import:R0402")
      (libsource (lib "eagle-import") (part "R-US_R0402"))
    )
    (comp (ref "R20")
      (value "10k, 1%")
      (footprint "eagle-import:R0402")
      (libsource (lib "eagle-import") (part "R-US_R0402"))
    )
    (comp (ref "R21")
      (value "4.75k, 1%")
      (footprint "eagle-import:R0402")
      (libsource (lib "eagle-import") (part "R-US_R0402"))
    )
    (comp (ref "R22")
      (value "4.75k, 1%")
      (footprint "eagle-import:R0402")
      (libsource (lib "eagle-import") (part "R-US_R0402"))
    )
    (comp (ref "R23")
      (value "10k, 1%")
      (footprint "eagle-import:R0402")
      (libsource (lib "eagle-import") (part "R-US_R0402"))
    )
    (comp (ref "R24")
      (value "10k, 1%")
      (footprint "eagle-import:R0402")
      (libsource (lib "eagle-import") (part "R-US_R0402"))
    )
    (comp (ref "R25")
      (value "10k, 1%")
      (footprint "eagle-import:R0402")
      (libsource (lib "eagle-import") (part "R-US_R0402"))
    )
    (comp (ref "R26")
      (value "0, 1%")
      (footprint "eagle-import:R0402")
      (libsource (lib "eagle-import") (part "R-US_R0402"))
    )
    (comp (ref "R27")
      (value "0, 1%")
      (footprint "eagle-import:R0402")
      (libsource (lib "eagle-import") (part "R-US_R0402"))
    )
    (comp (ref "R28")
      (value "10k, 1%")
      (footprint "eagle-import:R0402")
      (libsource (lib "eagle-import") (part "R-US_R0402"))
    )
    (comp (ref "R29")
      (value "0, 1%")
      (footprint "eagle-import:R0402")
      (libsource (lib "eagle-import") (part "R-US_R0402"))
    )
    (comp (ref "R30")
      (value "10k, 1%")
      (footprint "eagle-import:R0402")
      (libsource (lib "eagle-import") (part "R-US_R0402"))
    )
    (comp (ref "R31")
      (value "10k, 1%")
      (footprint "eagle-import:R0402")
      (libsource (lib "eagle-import") (part "R-US_R0402"))
    )
    (comp (ref "R32")
      (value "10k, 1%")
      (footprint "eagle-import:R0402")
      (libsource (lib "eagle-import") (part "R-US_R0402"))
    )
    (comp (ref "R33")
      (value "10k, 1%")
      (footprint "eagle-import:R0402")
      (libsource (lib "eagle-import") (part "R-US_R0402"))
    )
    (comp (ref "R34")
      (value "22")
      (footprint "eagle-import:R0402")
      (libsource (lib "eagle-import") (part "R-US_R0402"))
    )
    (comp (ref "R35")
      (value "0, 1%")
      (footprint "eagle-import:R0402")
      (libsource (lib "eagle-import") (part "R-US_R0402"))
    )
    (comp (ref "R36")
      (value "0, 1%")
      (footprint "eagle-import:R0402")
      (libsource (lib "eagle-import") (part "R-US_R0402"))
    )
    (comp (ref "R37")
      (value "0, 1%")
      (footprint "eagle-import:R0402")
      (libsource (lib "eagle-import") (part "R-US_R0402"))
    )
    (comp (ref "R38")
      (value "0, 1%")
      (footprint "eagle-import:R0402")
      (libsource (lib "eagle-import") (part "R-US_R0402"))
    )
    (comp (ref "R39")
      (value "0, 1%")
      (footprint "eagle-import:R0402")
      (libsource (lib "eagle-import") (part "R-US_R0402"))
    )
    (comp (ref "R40")
      (value "10k, 1%")
      (footprint "eagle-import:R0402")
      (libsource (lib "eagle-import") (part "R-US_R0402"))
    )
    (comp (ref "R41")
      (value "1.5k, 1%")
      (footprint "eagle-import:R0402")
      (libsource (lib "eagle-import") (part "R-US_R0402"))
    )
    (comp (ref "R42")
      (value "1.5k, 1%")
      (footprint "eagle-import:R0402")
      (libsource (lib "eagle-import") (part "R-US_R0402"))
    )
    (comp (ref "R43")
      (value "4.75k, 1%")
      (footprint "eagle-import:R0402")
      (libsource (lib "eagle-import") (part "R-US_R0402"))
    )
    (comp (ref "R44")
      (value "499")
      (footprint "eagle-import:R0402")
      (libsource (lib "eagle-import") (part "R-US_R0402"))
    )
    (comp (ref "R45")
      (value "DNP")
      (footprint "eagle-import:R0402")
      (libsource (lib "eagle-import") (part "R-US_R0402"))
    )
    (comp (ref "R46")
      (value "10k 1%")
      (footprint "eagle-import:R0402")
      (libsource (lib "eagle-import") (part "R-US_R0402"))
    )
    (comp (ref "R47")
      (value "40.2k 1%")
      (footprint "eagle-import:R0402")
      (libsource (lib "eagle-import") (part "R-US_R0402"))
    )
    (comp (ref "R48")
      (value "DNP 499")
      (footprint "eagle-import:R0402")
      (libsource (lib "eagle-import") (part "R-US_R0402"))
    )
    (comp (ref "R49")
      (value "DNP")
      (footprint "eagle-import:R0402")
      (libsource (lib "eagle-import") (part "R-US_R0402"))
    )
    (comp (ref "R50")
      (value "DNP 10k 1%")
      (footprint "eagle-import:R0402")
      (libsource (lib "eagle-import") (part "R-US_R0402"))
    )
    (comp (ref "R51")
      (value "DNP 40.2k 1%")
      (footprint "eagle-import:R0402")
      (libsource (lib "eagle-import") (part "R-US_R0402"))
    )
    (comp (ref "R52")
      (value "4.75k, 1%")
      (footprint "eagle-import:R0402")
      (libsource (lib "eagle-import") (part "R-US_R0402"))
    )
    (comp (ref "R53")
      (value "4.75k, 1%")
      (footprint "eagle-import:R0402")
      (libsource (lib "eagle-import") (part "R-US_R0402"))
    )
    (comp (ref "R54")
      (value "0, 1%")
      (footprint "eagle-import:R0402")
      (libsource (lib "eagle-import") (part "R-US_R0402"))
    )
    (comp (ref "R55")
      (value "4.75k, 1%")
      (footprint "eagle-import:R0402")
      (libsource (lib "eagle-import") (part "R-US_R0402"))
    )
    (comp (ref "R56")
      (value "DNP 1M, 1%")
      (footprint "eagle-import:R0402")
      (libsource (lib "eagle-import") (part "R-US_R0402"))
    )
    (comp (ref "R57")
      (value "100k, 1%")
      (footprint "eagle-import:R0402")
      (libsource (lib "eagle-import") (part "R-US_R0402"))
    )
    (comp (ref "R58")
      (value "100k, 1%")
      (footprint "eagle-import:R0402")
      (libsource (lib "eagle-import") (part "R-US_R0402"))
    )
    (comp (ref "R60")
      (value "33, 5%")
      (footprint "eagle-import:R0402")
      (libsource (lib "eagle-import") (part "R-US_R0402"))
    )
    (comp (ref "R61")
      (value "100k, 1%")
      (footprint "eagle-import:R0402")
      (libsource (lib "eagle-import") (part "R-US_R0402"))
    )
    (comp (ref "R62")
      (value "33, 5%")
      (footprint "eagle-import:R0402")
      (libsource (lib "eagle-import") (part "R-US_R0402"))
    )
    (comp (ref "R63")
      (value "100k, 1%")
      (footprint "eagle-import:R0402")
      (libsource (lib "eagle-import") (part "R-US_R0402"))
    )
    (comp (ref "R64")
      (value "33, 5%")
      (footprint "eagle-import:R0402")
      (libsource (lib "eagle-import") (part "R-US_R0402"))
    )
    (comp (ref "R65")
      (value "100k, 1%")
      (footprint "eagle-import:R0402")
      (libsource (lib "eagle-import") (part "R-US_R0402"))
    )
    (comp (ref "R66")
      (value "33, 5%")
      (footprint "eagle-import:R0402")
      (libsource (lib "eagle-import") (part "R-US_R0402"))
    )
    (comp (ref "R67")
      (value "100k, 1%")
      (footprint "eagle-import:R0402")
      (libsource (lib "eagle-import") (part "R-US_R0402"))
    )
    (comp (ref "R68")
      (value "33, 5%")
      (footprint "eagle-import:R0402")
      (libsource (lib "eagle-import") (part "R-US_R0402"))
    )
    (comp (ref "R69")
      (value "100k, 1%")
      (footprint "eagle-import:R0402")
      (libsource (lib "eagle-import") (part "R-US_R0402"))
    )
    (comp (ref "R70")
      (value "33, 5%")
      (footprint "eagle-import:R0402")
      (libsource (lib "eagle-import") (part "R-US_R0402"))
    )
    (comp (ref "R71")
      (value "100k, 1%")
      (footprint "eagle-import:R0402")
      (libsource (lib "eagle-import") (part "R-US_R0402"))
    )
    (comp (ref "R72")
      (value "33, 5%")
      (footprint "eagle-import:R0402")
      (libsource (lib "eagle-import") (part "R-US_R0402"))
    )
    (comp (ref "R73")
      (value "100k, 1%")
      (footprint "eagle-import:R0402")
      (libsource (lib "eagle-import") (part "R-US_R0402"))
    )
    (comp (ref "R75")
      (value "100k, 1%")
      (footprint "eagle-import:R0402")
      (libsource (lib "eagle-import") (part "R-US_R0402"))
    )
    (comp (ref "R76")
      (value "100k, 1%")
      (footprint "eagle-import:R0402")
      (libsource (lib "eagle-import") (part "R-US_R0402"))
    )
    (comp (ref "R78")
      (value "100k, 1%")
      (footprint "eagle-import:R0402")
      (libsource (lib "eagle-import") (part "R-US_R0402"))
    )
    (comp (ref "R80")
      (value "100k, 1%")
      (footprint "eagle-import:R0402")
      (libsource (lib "eagle-import") (part "R-US_R0402"))
    )
    (comp (ref "R82")
      (value "100k, 1%")
      (footprint "eagle-import:R0402")
      (libsource (lib "eagle-import") (part "R-US_R0402"))
    )
    (comp (ref "R85")
      (value "100k, 1%")
      (footprint "eagle-import:R0402")
      (libsource (lib "eagle-import") (part "R-US_R0402"))
    )
    (comp (ref "R86")
      (value "33, 5%")
      (footprint "eagle-import:R0603")
      (libsource (lib "eagle-import") (part "R-US_R0603"))
    )
    (comp (ref "R87")
      (value "100k, 1%")
      (footprint "eagle-import:R0402")
      (libsource (lib "eagle-import") (part "R-US_R0402"))
    )
    (comp (ref "R88")
      (value "100, 1%")
      (footprint "eagle-import:R0402")
      (libsource (lib "eagle-import") (part "R-US_R0402"))
    )
    (comp (ref "R89")
      (value "1k")
      (footprint "eagle-import:R0402")
      (libsource (lib "eagle-import") (part "R-US_R0402"))
    )
    (comp (ref "R90")
      (value "1k")
      (footprint "eagle-import:R0402")
      (libsource (lib "eagle-import") (part "R-US_R0402"))
    )
    (comp (ref "R91")
      (value "0 DNP")
      (footprint "eagle-import:R0402")
      (libsource (lib "eagle-import") (part "R-US_R0402"))
    )
    (comp (ref "R92")
      (value "1k")
      (footprint "eagle-import:R0402")
      (libsource (lib "eagle-import") (part "R-US_R0402"))
    )
    (comp (ref "R93")
      (value "7.15k")
      (footprint "eagle-import:R0402")
      (libsource (lib "eagle-import") (part "R-US_R0402"))
    )
    (comp (ref "R94")
      (value "4.12k")
      (footprint "eagle-import:R0402")
      (libsource (lib "eagle-import") (part "R-US_R0402"))
    )
    (comp (ref "R95")
      (value "1M")
      (footprint "eagle-import:R0402")
      (libsource (lib "eagle-import") (part "R-US_R0402"))
    )
    (comp (ref "R96")
      (value "1k")
      (footprint "eagle-import:R0402")
      (libsource (lib "eagle-import") (part "R-US_R0402"))
    )
    (comp (ref "R97")
      (value "DNP 1k")
      (footprint "eagle-import:R0402")
      (libsource (lib "eagle-import") (part "R-US_R0402"))
    )
    (comp (ref "R98")
      (value "10k")
      (footprint "eagle-import:R0402")
      (libsource (lib "eagle-import") (part "R-US_R0402"))
    )
    (comp (ref "R99")
      (value "10k")
      (footprint "eagle-import:R0402")
      (libsource (lib "eagle-import") (part "R-US_R0402"))
    )
    (comp (ref "R100")
      (value "1k")
      (footprint "eagle-import:R0402")
      (libsource (lib "eagle-import") (part "R-US_R0402"))
    )
    (comp (ref "R101")
      (value "10k")
      (footprint "eagle-import:R0402")
      (libsource (lib "eagle-import") (part "R-US_R0402"))
    )
    (comp (ref "R102")
      (value "10k")
      (footprint "eagle-import:R0402")
      (libsource (lib "eagle-import") (part "R-US_R0402"))
    )
    (comp (ref "R103")
      (value "10k")
      (footprint "eagle-import:R0402")
      (libsource (lib "eagle-import") (part "R-US_R0402"))
    )
    (comp (ref "R104")
      (value "1k")
      (footprint "eagle-import:R0402")
      (libsource (lib "eagle-import") (part "R-US_R0402"))
    )
    (comp (ref "R105")
      (value "10k")
      (footprint "eagle-import:R0402")
      (libsource (lib "eagle-import") (part "R-US_R0402"))
    )
    (comp (ref "R106")
      (value "1.5k")
      (footprint "eagle-import:R0402")
      (libsource (lib "eagle-import") (part "R-US_R0402"))
    )
    (comp (ref "R108")
      (value "DNP 1k")
      (footprint "eagle-import:R0402")
      (libsource (lib "eagle-import") (part "R-US_R0402"))
    )
    (comp (ref "R109")
      (value "DNP 1k")
      (footprint "eagle-import:R0402")
      (libsource (lib "eagle-import") (part "R-US_R0402"))
    )
    (comp (ref "R110")
      (value "33")
      (footprint "eagle-import:R0402")
      (libsource (lib "eagle-import") (part "R-US_R0402"))
    )
    (comp (ref "R111")
      (value "DNP 10k")
      (footprint "eagle-import:R0402")
      (libsource (lib "eagle-import") (part "R-US_R0402"))
    )
    (comp (ref "R114")
      (value "0, 1%")
      (footprint "eagle-import:R0402")
      (libsource (lib "eagle-import") (part "R-US_R0402"))
    )
    (comp (ref "R115")
      (value "1.5k, 1%")
      (footprint "eagle-import:R0402")
      (libsource (lib "eagle-import") (part "R-US_R0402"))
    )
    (comp (ref "R118")
      (value "1.5k, 1%")
      (footprint "eagle-import:R0402")
      (libsource (lib "eagle-import") (part "R-US_R0402"))
    )
    (comp (ref "R119")
      (value "10k, 1%")
      (footprint "eagle-import:R0402")
      (libsource (lib "eagle-import") (part "R-US_R0402"))
    )
    (comp (ref "R120")
      (value "27k, 1%")
      (footprint "eagle-import:R0402")
      (libsource (lib "eagle-import") (part "R-US_R0402"))
    )
    (comp (ref "R121")
      (value "10k, 1%")
      (footprint "eagle-import:R0402")
      (libsource (lib "eagle-import") (part "R-US_R0402"))
    )
    (comp (ref "R122")
      (value "0, 1%")
      (footprint "eagle-import:R0402")
      (libsource (lib "eagle-import") (part "R-US_R0402"))
    )
    (comp (ref "R123")
      (value "100k, 1%")
      (footprint "eagle-import:R0402")
      (libsource (lib "eagle-import") (part "R-US_R0402"))
    )
    (comp (ref "R124")
      (value "1k")
      (footprint "eagle-import:R0402")
      (libsource (lib "eagle-import") (part "R-US_R0402"))
    )
    (comp (ref "R125")
      (value "1k")
      (footprint "eagle-import:R0402")
      (libsource (lib "eagle-import") (part "R-US_R0402"))
    )
    (comp (ref "R126")
      (value "33, 5%")
      (footprint "eagle-import:R0603")
      (libsource (lib "eagle-import") (part "R-US_R0603"))
    )
    (comp (ref "R127")
      (value "33, 5%")
      (footprint "eagle-import:R0603")
      (libsource (lib "eagle-import") (part "R-US_R0603"))
    )
    (comp (ref "R128")
      (value "33, 5%")
      (footprint "eagle-import:R0603")
      (libsource (lib "eagle-import") (part "R-US_R0603"))
    )
    (comp (ref "R129")
      (value "33, 5%")
      (footprint "eagle-import:R0603")
      (libsource (lib "eagle-import") (part "R-US_R0603"))
    )
    (comp (ref "R130")
      (value "33, 5%")
      (footprint "eagle-import:R0603")
      (libsource (lib "eagle-import") (part "R-US_R0603"))
    )
    (comp (ref "R131")
      (value "33, 5%")
      (footprint "eagle-import:R0603")
      (libsource (lib "eagle-import") (part "R-US_R0603"))
    )
    (comp (ref "R134")
      (value "33, 5%")
      (footprint "eagle-import:R0603")
      (libsource (lib "eagle-import") (part "R-US_R0603"))
    )
    (comp (ref "R135")
      (value "33, 5%")
      (footprint "eagle-import:R0603")
      (libsource (lib "eagle-import") (part "R-US_R0603"))
    )
    (comp (ref "R136")
      (value "33, 5%")
      (footprint "eagle-import:R0603")
      (libsource (lib "eagle-import") (part "R-US_R0603"))
    )
    (comp (ref "R140")
      (value "33, 5%")
      (footprint "eagle-import:R0402")
      (libsource (lib "eagle-import") (part "R-US_R0402"))
    )
    (comp (ref "R141")
      (value "33, 5%")
      (footprint "eagle-import:R0402")
      (libsource (lib "eagle-import") (part "R-US_R0402"))
    )
    (comp (ref "R142")
      (value "33, 5%")
      (footprint "eagle-import:R0402")
      (libsource (lib "eagle-import") (part "R-US_R0402"))
    )
    (comp (ref "R143")
      (value "33, 5%")
      (footprint "eagle-import:R0402")
      (libsource (lib "eagle-import") (part "R-US_R0402"))
    )
    (comp (ref "RESET")
      (value "MINI_PUSHBUTTON")
      (footprint "eagle-import:MINI_PUSHBUTTON")
      (libsource (lib "eagle-import") (part "MINI_PUSHBUTTON"))
    )
    (comp (ref "S2")
      (value "MINI_PUSHBUTTON")
      (footprint "eagle-import:MINI_PUSHBUTTON")
      (libsource (lib "eagle-import") (part "MINI_PUSHBUTTON"))
    )
    (comp (ref "T1")
      (value "MMBT2907")
      (footprint "eagle-import:SOT23-BEC")
      (libsource (lib "eagle-import") (part "MMBT2907SMDALT1"))
    )
    (comp (ref "T2")
      (value "DNP MMBT2907")
      (footprint "eagle-import:SOT23-BEC")
      (libsource (lib "eagle-import") (part "MMBT2907SMDALT1"))
    )
    (comp (ref "T3")
      (value "BSS138W-7-F")
      (footprint "eagle-import:SOT-323(DIODES)")
      (libsource (lib "eagle-import") (part "BSS138W-7-F"))
    )
    (comp (ref "T4")
      (value "BSS138W-7-F")
      (footprint "eagle-import:SOT-323(DIODES)")
      (libsource (lib "eagle-import") (part "BSS138W-7-F"))
    )
    (comp (ref "TP1")
      (value "TESTPAD/W_HOLE_1X1")
      (footprint "eagle-import:TESTPAD_W_HOLE_1X1")
      (libsource (lib "eagle-import") (part "TESTPAD/W_HOLE_1X1"))
    )
    (comp (ref "TP2")
      (value "TESTPAD/W_HOLE_1X1")
      (footprint "eagle-import:TESTPAD_W_HOLE_1X1")
      (libsource (lib "eagle-import") (part "TESTPAD/W_HOLE_1X1"))
    )
    (comp (ref "TP3")
      (value "TESTPAD/W_HOLE_1X1")
      (footprint "eagle-import:TESTPAD_W_HOLE_1X1")
      (libsource (lib "eagle-import") (part "TESTPAD/W_HOLE_1X1"))
    )
    (comp (ref "TP4")
      (value "TESTPAD/W_HOLE_1X1")
      (footprint "eagle-import:TESTPAD_W_HOLE_1X1")
      (libsource (lib "eagle-import") (part "TESTPAD/W_HOLE_1X1"))
    )
    (comp (ref "TP5")
      (value "TESTPAD/W_HOLE_1X1")
      (footprint "eagle-import:TESTPAD_W_HOLE_1X1")
      (libsource (lib "eagle-import") (part "TESTPAD/W_HOLE_1X1"))
    )
    (comp (ref "TP6")
      (value "PTR1B1,27")
      (footprint "eagle-import:B1,27")
      (libsource (lib "eagle-import") (part "PTR1B1,27"))
    )
    (comp (ref "TP12")
      (value "PTR1B1,27")
      (footprint "eagle-import:B1,27")
      (libsource (lib "eagle-import") (part "PTR1B1,27"))
    )
    (comp (ref "TP13")
      (value "PTR1B1,27")
      (footprint "eagle-import:B1,27")
      (libsource (lib "eagle-import") (part "PTR1B1,27"))
    )
    (comp (ref "TP14")
      (value "PTR1B1,27")
      (footprint "eagle-import:B1,27")
      (libsource (lib "eagle-import") (part "PTR1B1,27"))
    )
    (comp (ref "TP15")
      (value "PTR1B1,27")
      (footprint "eagle-import:B1,27")
      (libsource (lib "eagle-import") (part "PTR1B1,27"))
    )
    (comp (ref "TP16")
      (value "PTR1B1,27")
      (footprint "eagle-import:B1,27")
      (libsource (lib "eagle-import") (part "PTR1B1,27"))
    )
    (comp (ref "TP17")
      (value "PTR1B1,27")
      (footprint "eagle-import:B1,27")
      (libsource (lib "eagle-import") (part "PTR1B1,27"))
    )
    (comp (ref "TP18")
      (value "PTR1B1,27")
      (footprint "eagle-import:B1,27")
      (libsource (lib "eagle-import") (part "PTR1B1,27"))
    )
    (comp (ref "TP19")
      (value "PTR1B1,27")
      (footprint "eagle-import:B1,27")
      (libsource (lib "eagle-import") (part "PTR1B1,27"))
    )
    (comp (ref "TP23")
      (value "PTR1B1,27")
      (footprint "eagle-import:B1,27")
      (libsource (lib "eagle-import") (part "PTR1B1,27"))
    )
    (comp (ref "USR0")
      (value "LTST-C191TBKT")
      (footprint "eagle-import:0603-LED")
      (libsource (lib "eagle-import") (part "LED-(INCH)-0603"))
    )
    (comp (ref "USR1")
      (value "LTST-C191TBKT")
      (footprint "eagle-import:0603-LED")
      (libsource (lib "eagle-import") (part "LED-(INCH)-0603"))
    )
    (comp (ref "USR2")
      (value "LTST-C191TBKT")
      (footprint "eagle-import:0603-LED")
      (libsource (lib "eagle-import") (part "LED-(INCH)-0603"))
    )
    (comp (ref "USR3")
      (value "LTST-C191TBKT")
      (footprint "eagle-import:0603-LED")
      (libsource (lib "eagle-import") (part "LED-(INCH)-0603"))
    )
    (comp (ref "WL")
      (value "LTST-C191TBKT")
      (footprint "eagle-import:0603-LED")
      (libsource (lib "eagle-import") (part "LED-(INCH)-0603"))
    )
    (comp (ref "X1")
      (value "1X6-(INCH)-0.1-TH")
      (footprint "eagle-import:TH-1X6")
      (libsource (lib "eagle-import") (part "1X6-(INCH)-0.1-TH"))
    )
    (comp (ref "X2")
      (value "SCHA5B0200")
      (footprint "eagle-import:SCHA5B0200")
      (libsource (lib "eagle-import") (part "SCHA5B0200(ALPS_USD)"))
    )
    (comp (ref "X3")
      (value "USB_HOST_W/CHASSIS_GND")
      (footprint "eagle-import:USB_HOST_HORIZONTAL_W_CHASSIS_GND")
      (libsource (lib "eagle-import") (part "USB_HOST_W/CHASSIS_GND"))
    )
    (comp (ref "X4")
      (value "10118192-0001LF")
      (footprint "eagle-import:10118192-0001LF(MICRO-USB-B-AMPHENOL-FCI)")
      (libsource (lib "eagle-import") (part "10118192-0001LF"))
    )
    (comp (ref "X5")
      (value "10118241-001RLF")
      (footprint "eagle-import:HDMI-TYPE-D-10118241")
      (libsource (lib "eagle-import") (part "HDMI-TYPE-D-10118241"))
    )
    (comp (ref "X12")
      (value "PJ-102B_POWER_CON")
      (footprint "eagle-import:PJ-102B_POWER_CON")
      (libsource (lib "eagle-import") (part "PJ-102B_POWER_CON"))
    )
  )
  (nets
    (net (code "1") (name "/5V_IN") (class "Default")
      (node (ref "C19") (pin "1") (pinfunction "1_1") (pintype "passive"))
      (node (ref "D8") (pin "3") (pinfunction "CC_3") (pintype "passive"))
      (node (ref "FB1") (pin "2") (pinfunction "P$2_2") (pintype "bidirectional"))
      (node (ref "IC18") (pin "2") (pinfunction "IN_2") (pintype "bidirectional"))
      (node (ref "R95") (pin "1") (pinfunction "1_1") (pintype "passive"))
    )
    (net (code "2") (name "/12MHZ") (class "Default")
      (node (ref "FB6") (pin "2") (pinfunction "2_2") (pintype "passive"))
      (node (ref "IC9") (pin "27") (pinfunction "OSC_IN/AP3_27") (pintype "bidirectional"))
    )
    (net (code "3") (name "/12M_LOOP") (class "Default")
      (node (ref "IC13") (pin "2") (pinfunction "D_2") (pintype "bidirectional"))
      (node (ref "IC13") (pin "3") (pinfunction "Q#_3") (pintype "bidirectional"))
    )
    (net (code "4") (name "/32.768KHZ") (class "Default")
      (node (ref "MOD1") (pin "36") (pinfunction "EXT_32K_36") (pintype "bidirectional"))
      (node (ref "OSC2") (pin "3") (pinfunction "OUT_3") (pintype "bidirectional"))
      (node (ref "R91") (pin "2") (pinfunction "2_2") (pintype "passive"))
    )
    (net (code "5") (name "/AIN0") (class "Default")
      (node (ref "IC1") (pin "B6") (pinfunction "AIN0_B6") (pintype "bidirectional"))
      (node (ref "P9") (pin "39") (pinfunction "39_39") (pintype "passive"))
    )
    (net (code "6") (name "/AIN1") (class "Default")
      (node (ref "IC1") (pin "C7") (pinfunction "AIN1_C7") (pintype "bidirectional"))
      (node (ref "P9") (pin "40") (pinfunction "40_40") (pintype "passive"))
    )
    (net (code "7") (name "/AIN2") (class "Default")
      (node (ref "IC1") (pin "B7") (pinfunction "AIN2_B7") (pintype "bidirectional"))
      (node (ref "P9") (pin "37") (pinfunction "37_37") (pintype "passive"))
    )
    (net (code "8") (name "/AIN3") (class "Default")
      (node (ref "IC1") (pin "A7") (pinfunction "AIN3_A7") (pintype "bidirectional"))
      (node (ref "P9") (pin "38") (pinfunction "38_38") (pintype "passive"))
    )
    (net (code "9") (name "/AIN4") (class "Default")
      (node (ref "IC1") (pin "C8") (pinfunction "AIN4_C8") (pintype "bidirectional"))
      (node (ref "P9") (pin "33") (pinfunction "33_33") (pintype "passive"))
    )
    (net (code "10") (name "/AIN5") (class "Default")
      (node (ref "IC1") (pin "B8") (pinfunction "AIN5_B8") (pintype "bidirectional"))
      (node (ref "P9") (pin "36") (pinfunction "36_36") (pintype "passive"))
    )
    (net (code "11") (name "/AIN6") (class "Default")
      (node (ref "IC1") (pin "A8") (pinfunction "AIN6_A8") (pintype "bidirectional"))
      (node (ref "P9") (pin "35") (pinfunction "35_35") (pintype "passive"))
    )
    (net (code "12") (name "/BAT_TEMP") (class "Default")
      (node (ref "IC1") (pin "W1") (pinfunction "BAT_TEMP_W1") (pintype "bidirectional"))
      (node (ref "TP4") (pin "P$1") (pinfunction "TP_P$1") (pintype "bidirectional"))
    )
    (net (code "13") (name "/BAT_VOLT") (class "Default")
      (node (ref "IC1") (pin "Y1") (pinfunction "BATT_VOLT_Y1") (pintype "bidirectional"))
      (node (ref "TP3") (pin "P$1") (pinfunction "TP_P$1") (pintype "bidirectional"))
    )
    (net (code "14") (name "/BT_EN") (class "Default")
      (node (ref "IC11") (pin "4") (pinfunction "A3_4") (pintype "bidirectional"))
      (node (ref "MOD1") (pin "41") (pinfunction "BT_EN_41") (pintype "bidirectional"))
      (node (ref "R11") (pin "1") (pinfunction "1_1") (pintype "passive"))
      (node (ref "T4") (pin "G") (pinfunction "G_G") (pintype "bidirectional"))
    )
    (net (code "15") (name "/BT_EN.SIP") (class "Default")
      (node (ref "IC1") (pin "K17") (pinfunction "MII1_TXD0_K17") (pintype "bidirectional"))
      (node (ref "R135") (pin "1") (pinfunction "1_1") (pintype "passive"))
    )
    (net (code "16") (name "/BT_HCI_CTS") (class "Default")
      (node (ref "IC11") (pin "8") (pinfunction "A7_8") (pintype "bidirectional"))
      (node (ref "R141") (pin "2") (pinfunction "2_2") (pintype "passive"))
    )
    (net (code "17") (name "/BT_HCI_CTS.SIP") (class "Default")
      (node (ref "IC1") (pin "M17") (pinfunction "MDIO_DATA_M17") (pintype "bidirectional"))
      (node (ref "IC11") (pin "15") (pinfunction "B5_15") (pintype "bidirectional"))
      (node (ref "R108") (pin "1") (pinfunction "1_1") (pintype "passive"))
    )
    (net (code "18") (name "/BT_HCI_RTS") (class "Default")
      (node (ref "IC11") (pin "6") (pinfunction "A5_6") (pintype "bidirectional"))
      (node (ref "R140") (pin "2") (pinfunction "2_2") (pintype "passive"))
    )
    (net (code "19") (name "/BT_HCI_RTS.SIP") (class "Default")
      (node (ref "IC1") (pin "M18") (pinfunction "MDIO_CLK_M18") (pintype "bidirectional"))
      (node (ref "IC11") (pin "13") (pinfunction "B7_13") (pintype "bidirectional"))
      (node (ref "R109") (pin "1") (pinfunction "1_1") (pintype "passive"))
    )
    (net (code "20") (name "/BT_HCI_RX") (class "Default")
      (node (ref "IC11") (pin "1") (pinfunction "A1_1") (pintype "bidirectional"))
      (node (ref "R143") (pin "2") (pinfunction "2_2") (pintype "passive"))
    )
    (net (code "21") (name "/BT_HCI_RX.SIP") (class "Default")
      (node (ref "IC1") (pin "L17") (pinfunction "MII1_RXD3_L17") (pintype "bidirectional"))
      (node (ref "IC11") (pin "14") (pinfunction "B6_14") (pintype "bidirectional"))
    )
    (net (code "22") (name "/BT_HCI_TX") (class "Default")
      (node (ref "IC11") (pin "7") (pinfunction "A6_7") (pintype "bidirectional"))
      (node (ref "R142") (pin "2") (pinfunction "2_2") (pintype "passive"))
    )
    (net (code "23") (name "/BT_HCI_TX.SIP") (class "Default")
      (node (ref "IC1") (pin "L16") (pinfunction "MII1_RXD2_L16") (pintype "bidirectional"))
      (node (ref "IC11") (pin "20") (pinfunction "B1_20") (pintype "bidirectional"))
    )
    (net (code "24") (name "/CEC") (class "Default")
      (node (ref "D1") (pin "C") (pinfunction "CATHODE_C") (pintype "bidirectional"))
      (node (ref "IC9") (pin "30") (pinfunction "CEC_30") (pintype "bidirectional"))
      (node (ref "X5") (pin "15") (pinfunction "CEC_15") (pintype "bidirectional"))
    )
    (net (code "25") (name "/CLKOUT2") (class "Default")
      (node (ref "FB7") (pin "1") (pinfunction "1_1") (pintype "passive"))
      (node (ref "IC11") (pin "16") (pinfunction "B4_16") (pintype "bidirectional"))
      (node (ref "P2") (pin "18") (pinfunction "EMU3_18") (pintype "bidirectional"))
      (node (ref "P9") (pin "41") (pinfunction "41_41") (pintype "passive"))
      (node (ref "R14") (pin "1") (pinfunction "1_1") (pintype "passive"))
    )
    (net (code "26") (name "/DVI_5V") (class "Default")
      (node (ref "F1") (pin "1") (pinfunction "1_1") (pintype "passive"))
      (node (ref "R115") (pin "1") (pinfunction "1_1") (pintype "passive"))
      (node (ref "R118") (pin "1") (pinfunction "1_1") (pintype "passive"))
      (node (ref "X5") (pin "19") (pinfunction "5V_19") (pintype "bidirectional"))
    )
    (net (code "27") (name "/EHRPWM1A") (class "Default")
      (node (ref "IC1") (pin "U14") (pinfunction "EHRPWM1A_U14") (pintype "bidirectional"))
      (node (ref "P9") (pin "14") (pinfunction "14_14") (pintype "passive"))
    )
    (net (code "28") (name "/EHRPWM1B") (class "Default")
      (node (ref "IC1") (pin "T14") (pinfunction "EHRPWM1B_T14") (pintype "bidirectional"))
      (node (ref "P9") (pin "16") (pinfunction "16_16") (pintype "passive"))
    )
    (net (code "29") (name "/EHRPWM2A") (class "Default")
      (node (ref "IC1") (pin "U10") (pinfunction "EHRPWM2A_U10") (pintype "bidirectional"))
      (node (ref "P8") (pin "19") (pinfunction "19_19") (pintype "passive"))
    )
    (net (code "30") (name "/EHRPWM2B") (class "Default")
      (node (ref "IC1") (pin "T10") (pinfunction "EHRPWM2B_T10") (pintype "bidirectional"))
      (node (ref "P8") (pin "13") (pinfunction "13_13") (pintype "passive"))
    )
    (net (code "31") (name "/EMMC_RSTN") (class "Default")
      (node (ref "IC22") (pin "K5") (pinfunction "RST#_K5") (pintype "bidirectional"))
      (node (ref "R29") (pin "1") (pinfunction "1_1") (pintype "passive"))
      (node (ref "R33") (pin "1") (pinfunction "1_1") (pintype "passive"))
    )
    (net (code "32") (name "/EXT_SWING") (class "Default")
      (node (ref "IC9") (pin "34") (pinfunction "EXT_SWING_34") (pintype "bidirectional"))
      (node (ref "R119") (pin "1") (pinfunction "1_1") (pintype "passive"))
    )
    (net (code "33") (name "/GPIO0_7") (class "Default")
      (node (ref "P9") (pin "42") (pinfunction "42_42") (pintype "passive"))
      (node (ref "R36") (pin "1") (pinfunction "1_1") (pintype "passive"))
      (node (ref "R38") (pin "1") (pinfunction "1_1") (pintype "passive"))
    )
    (net (code "34") (name "/GPIO0_26") (class "Default")
      (node (ref "IC1") (pin "T11") (pinfunction "GPIO0_26_T11") (pintype "bidirectional"))
      (node (ref "P8") (pin "14") (pinfunction "14_14") (pintype "passive"))
    )
    (net (code "35") (name "/GPIO0_27") (class "Default")
      (node (ref "IC1") (pin "U12") (pinfunction "GPIO0_27_U12") (pintype "bidirectional"))
      (node (ref "P8") (pin "17") (pinfunction "17_17") (pintype "passive"))
    )
    (net (code "36") (name "/GPIO1_12") (class "Default")
      (node (ref "IC1") (pin "T12") (pinfunction "GPIO1_12_T12") (pintype "bidirectional"))
      (node (ref "P8") (pin "12") (pinfunction "12_12") (pintype "passive"))
    )
    (net (code "37") (name "/GPIO1_13") (class "Default")
      (node (ref "IC1") (pin "R12") (pinfunction "GPIO1_13_R12") (pintype "bidirectional"))
      (node (ref "P8") (pin "11") (pinfunction "11_11") (pintype "passive"))
    )
    (net (code "38") (name "/GPIO1_14") (class "Default")
      (node (ref "IC1") (pin "V13") (pinfunction "GPIO1_14_V13") (pintype "bidirectional"))
      (node (ref "P8") (pin "16") (pinfunction "16_16") (pintype "passive"))
    )
    (net (code "39") (name "/GPIO1_15") (class "Default")
      (node (ref "IC1") (pin "U13") (pinfunction "GPIO1_15_U13") (pintype "bidirectional"))
      (node (ref "P8") (pin "15") (pinfunction "15_15") (pintype "passive"))
    )
    (net (code "40") (name "/GPIO1_16") (class "Default")
      (node (ref "P9") (pin "15") (pinfunction "15_15") (pintype "passive"))
      (node (ref "R54") (pin "1") (pinfunction "1_1") (pintype "passive"))
    )
    (net (code "41") (name "/GPIO1_16.SIP") (class "Default")
      (node (ref "IC1") (pin "R13") (pinfunction "GPIO1_16_R13") (pintype "bidirectional"))
      (node (ref "R54") (pin "2") (pinfunction "2_2") (pintype "passive"))
    )
    (net (code "42") (name "/GPIO1_17") (class "Default")
      (node (ref "IC1") (pin "V14") (pinfunction "GPIO1_17_V14") (pintype "bidirectional"))
      (node (ref "P9") (pin "23") (pinfunction "23_23") (pintype "passive"))
    )
    (net (code "43") (name "/GPIO1_28") (class "Default")
      (node (ref "IC1") (pin "U18") (pinfunction "GPIO1_28_U18") (pintype "bidirectional"))
      (node (ref "P9") (pin "12") (pinfunction "12_12") (pintype "passive"))
    )
    (net (code "44") (name "/GPIO1_29") (class "Default")
      (node (ref "IC1") (pin "V6") (pinfunction "GPIO1_29_V6") (pintype "bidirectional"))
      (node (ref "P8") (pin "26") (pinfunction "26_26") (pintype "passive"))
    )
    (net (code "45") (name "/GPIO2_0.SIP") (class "Default")
      (node (ref "IC1") (pin "T13") (pinfunction "GPIO2_0_T13") (pintype "bidirectional"))
    )
    (net (code "46") (name "/GPIO2_1") (class "Default")
      (node (ref "IC1") (pin "V12") (pinfunction "GPIO2_1_V12") (pintype "bidirectional"))
      (node (ref "P8") (pin "18") (pinfunction "18_18") (pintype "passive"))
    )
    (net (code "47") (name "/GPIO3_19") (class "Default")
      (node (ref "IC1") (pin "C13") (pinfunction "GPIO3_19_C13") (pintype "bidirectional"))
      (node (ref "P9") (pin "27") (pinfunction "27_27") (pintype "passive"))
    )
    (net (code "48") (name "/GPIO3_21") (class "Default")
      (node (ref "IC1") (pin "A14") (pinfunction "GPIO3_21_A14") (pintype "bidirectional"))
      (node (ref "P9") (pin "25") (pinfunction "25_25") (pintype "passive"))
      (node (ref "R110") (pin "2") (pinfunction "2_2") (pintype "passive"))
    )
    (net (code "49") (name "/HDMICLK_DIS#") (class "Default")
      (node (ref "IC1") (pin "V17") (pinfunction "(HDMICLK_DISN)GPIO1_27_V17") (pintype "bidirectional"))
      (node (ref "OSC1") (pin "1") (pinfunction "INH#_1") (pintype "bidirectional"))
    )
    (net (code "50") (name "/HDMI_INT") (class "Default")
      (node (ref "IC1") (pin "U16") (pinfunction "(HDMI_INT)GPIO1_25_U16") (pintype "bidirectional"))
      (node (ref "IC9") (pin "50") (pinfunction "INT_50") (pintype "bidirectional"))
      (node (ref "R121") (pin "2") (pinfunction "2_2") (pintype "passive"))
    )
    (net (code "51") (name "/HPD") (class "Default")
      (node (ref "IC9") (pin "31") (pinfunction "HPD_31") (pintype "bidirectional"))
      (node (ref "X5") (pin "1") (pinfunction "HOT.PLUG.DETECT_1") (pintype "bidirectional"))
    )
    (net (code "52") (name "/I2C0_SCL") (class "Default")
      (node (ref "IC1") (pin "C16") (pinfunction "I2C0_SCL_C16") (pintype "bidirectional"))
      (node (ref "IC1") (pin "C20") (pinfunction "PMIC_I2C_SCL_C20") (pintype "bidirectional"))
      (node (ref "IC4") (pin "1") (pinfunction "SCL_1") (pintype "bidirectional"))
      (node (ref "IC9") (pin "52") (pinfunction "CSCL_52") (pintype "bidirectional"))
      (node (ref "R41") (pin "2") (pinfunction "2_2") (pintype "passive"))
    )
    (net (code "53") (name "/I2C0_SDA") (class "Default")
      (node (ref "IC1") (pin "C17") (pinfunction "I2C0_SDA_C17") (pintype "bidirectional"))
      (node (ref "IC1") (pin "C19") (pinfunction "PMIC_I2C_SDA_C19") (pintype "bidirectional"))
      (node (ref "IC4") (pin "3") (pinfunction "SDA_3") (pintype "bidirectional"))
      (node (ref "IC9") (pin "51") (pinfunction "CSDA_51") (pintype "bidirectional"))
      (node (ref "R42") (pin "2") (pinfunction "2_2") (pintype "passive"))
    )
    (net (code "54") (name "/I2C1_SCL") (class "Default")
      (node (ref "IC1") (pin "A16") (pinfunction "I2C1_SCL_A16") (pintype "bidirectional"))
      (node (ref "P9") (pin "17") (pinfunction "17_17") (pintype "passive"))
    )
    (net (code "55") (name "/I2C1_SDA") (class "Default")
      (node (ref "IC1") (pin "B16") (pinfunction "I2C1_SDA_B16") (pintype "bidirectional"))
      (node (ref "P9") (pin "18") (pinfunction "18_18") (pintype "passive"))
    )
    (net (code "56") (name "/I2C2_SCL") (class "Default")
      (node (ref "IC1") (pin "D17") (pinfunction "I2C2_SCL_D17") (pintype "bidirectional"))
      (node (ref "P9") (pin "19") (pinfunction "19_19") (pintype "passive"))
    )
    (net (code "57") (name "/I2C2_SDA") (class "Default")
      (node (ref "IC1") (pin "D18") (pinfunction "I2C2_SDA_D18") (pintype "bidirectional"))
      (node (ref "P9") (pin "20") (pinfunction "20_20") (pintype "passive"))
    )
    (net (code "58") (name "/JTAG_EMU0") (class "Default")
      (node (ref "IC1") (pin "C14") (pinfunction "JTAG_EMU0_C14") (pintype "bidirectional"))
      (node (ref "P2") (pin "13") (pinfunction "EMU0_13") (pintype "bidirectional"))
      (node (ref "R43") (pin "2") (pinfunction "2_2") (pintype "passive"))
    )
    (net (code "59") (name "/JTAG_EMU1") (class "Default")
      (node (ref "IC1") (pin "B14") (pinfunction "JTAG_EMU1_B14") (pintype "bidirectional"))
      (node (ref "P2") (pin "14") (pinfunction "EMU1_14") (pintype "bidirectional"))
      (node (ref "R53") (pin "2") (pinfunction "2_2") (pintype "passive"))
    )
    (net (code "60") (name "/JTAG_TCK") (class "Default")
      (node (ref "IC1") (pin "A12") (pinfunction "JTAG_TCK_A12") (pintype "bidirectional"))
      (node (ref "P2") (pin "11") (pinfunction "TCK_11") (pintype "bidirectional"))
      (node (ref "P2") (pin "9") (pinfunction "TCKRTN_9") (pintype "bidirectional"))
    )
    (net (code "61") (name "/JTAG_TDI") (class "Default")
      (node (ref "IC1") (pin "B11") (pinfunction "JTAG_TDI_B11") (pintype "bidirectional"))
      (node (ref "P2") (pin "3") (pinfunction "TDI_3") (pintype "bidirectional"))
    )
    (net (code "62") (name "/JTAG_TDO") (class "Default")
      (node (ref "IC1") (pin "A11") (pinfunction "JTAG_TDO_A11") (pintype "bidirectional"))
      (node (ref "P2") (pin "7") (pinfunction "TDO_7") (pintype "bidirectional"))
    )
    (net (code "63") (name "/JTAG_TMS") (class "Default")
      (node (ref "IC1") (pin "C11") (pinfunction "JTAG_TMS_C11") (pintype "bidirectional"))
      (node (ref "P2") (pin "1") (pinfunction "TMS_1") (pintype "bidirectional"))
    )
    (net (code "64") (name "/JTAG_TRSTN") (class "Default")
      (node (ref "IC1") (pin "B10") (pinfunction "JTAG_TRSTN_B10") (pintype "bidirectional"))
      (node (ref "P2") (pin "2") (pinfunction "TRST#_2") (pintype "bidirectional"))
      (node (ref "R52") (pin "1") (pinfunction "1_1") (pintype "passive"))
    )
    (net (code "65") (name "/LCD.CLOCK") (class "Default")
      (node (ref "IC9") (pin "4") (pinfunction "PCLK_4") (pintype "bidirectional"))
      (node (ref "P8") (pin "28") (pinfunction "28_28") (pintype "passive"))
      (node (ref "R34") (pin "1") (pinfunction "1_1") (pintype "passive"))
    )
    (net (code "66") (name "/LCD.D0.B0--B3") (class "Default")
      (node (ref "C42") (pin "1") (pinfunction "1_1") (pintype "passive"))
      (node (ref "IC1") (pin "R1") (pinfunction "LCD_DATA0_R1") (pintype "bidirectional"))
      (node (ref "IC9") (pin "15") (pinfunction "VPC[3]_15") (pintype "bidirectional"))
      (node (ref "P8") (pin "45") (pinfunction "45_45") (pintype "passive"))
      (node (ref "R87") (pin "2") (pinfunction "2_2") (pintype "passive"))
    )
    (net (code "67") (name "/LCD.D1.B1--B4") (class "Default")
      (node (ref "C41") (pin "1") (pinfunction "1_1") (pintype "passive"))
      (node (ref "IC1") (pin "R2") (pinfunction "LCD_DATA1_R2") (pintype "bidirectional"))
      (node (ref "IC9") (pin "13") (pinfunction "VPC[4]_13") (pintype "bidirectional"))
      (node (ref "P8") (pin "46") (pinfunction "46_46") (pintype "passive"))
      (node (ref "R85") (pin "2") (pinfunction "2_2") (pintype "passive"))
    )
    (net (code "68") (name "/LCD.D2.B2--B5") (class "Default")
      (node (ref "C40") (pin "1") (pinfunction "1_1") (pintype "passive"))
      (node (ref "IC1") (pin "R3") (pinfunction "LCD_DATA2_R3") (pintype "bidirectional"))
      (node (ref "IC9") (pin "12") (pinfunction "VPC[5]_12") (pintype "bidirectional"))
      (node (ref "P8") (pin "43") (pinfunction "43_43") (pintype "passive"))
      (node (ref "R82") (pin "1") (pinfunction "1_1") (pintype "passive"))
      (node (ref "R88") (pin "1") (pinfunction "1_1") (pintype "passive"))
    )
    (net (code "69") (name "/LCD.D3.B3--B6") (class "Default")
      (node (ref "C39") (pin "1") (pinfunction "1_1") (pintype "passive"))
      (node (ref "IC1") (pin "R4") (pinfunction "LCD_DATA3_R4") (pintype "bidirectional"))
      (node (ref "IC9") (pin "11") (pinfunction "VPC[6]_11") (pintype "bidirectional"))
      (node (ref "P8") (pin "44") (pinfunction "44_44") (pintype "passive"))
      (node (ref "R80") (pin "1") (pinfunction "1_1") (pintype "passive"))
    )
    (net (code "70") (name "/LCD.D4.B4--B7") (class "Default")
      (node (ref "C38") (pin "1") (pinfunction "1_1") (pintype "passive"))
      (node (ref "IC1") (pin "T1") (pinfunction "LCD_DATA4_T1") (pintype "bidirectional"))
      (node (ref "IC9") (pin "10") (pinfunction "VPC[7]_10") (pintype "bidirectional"))
      (node (ref "P8") (pin "41") (pinfunction "41_41") (pintype "passive"))
      (node (ref "R78") (pin "1") (pinfunction "1_1") (pintype "passive"))
    )
    (net (code "71") (name "/LCD.D5.G0--G2") (class "Default")
      (node (ref "C37") (pin "1") (pinfunction "1_1") (pintype "passive"))
      (node (ref "IC1") (pin "T2") (pinfunction "LCD_DATA5_T2") (pintype "bidirectional"))
      (node (ref "IC9") (pin "7") (pinfunction "VPB[2]_7") (pintype "bidirectional"))
      (node (ref "P8") (pin "42") (pinfunction "42_42") (pintype "passive"))
      (node (ref "R76") (pin "1") (pinfunction "1_1") (pintype "passive"))
    )
    (net (code "72") (name "/LCD.D6.G1--G3") (class "Default")
      (node (ref "C36") (pin "1") (pinfunction "1_1") (pintype "passive"))
      (node (ref "IC1") (pin "T3") (pinfunction "LCD_DATA6_T3") (pintype "bidirectional"))
      (node (ref "IC9") (pin "6") (pinfunction "VPB[3]_6") (pintype "bidirectional"))
      (node (ref "P8") (pin "39") (pinfunction "39_39") (pintype "passive"))
      (node (ref "R75") (pin "2") (pinfunction "2_2") (pintype "passive"))
    )
    (net (code "73") (name "/LCD.D7.G2--G4") (class "Default")
      (node (ref "C35") (pin "1") (pinfunction "1_1") (pintype "passive"))
      (node (ref "IC1") (pin "T4") (pinfunction "LCD_DATA7_T4") (pintype "bidirectional"))
      (node (ref "IC9") (pin "3") (pinfunction "VPB[4]_3") (pintype "bidirectional"))
      (node (ref "P8") (pin "40") (pinfunction "40_40") (pintype "passive"))
      (node (ref "R73") (pin "2") (pinfunction "2_2") (pintype "passive"))
    )
    (net (code "74") (name "/LCD.D8.G3--G5") (class "Default")
      (node (ref "C34") (pin "1") (pinfunction "1_1") (pintype "passive"))
      (node (ref "IC1") (pin "U1") (pinfunction "LCD_DATA8_U1") (pintype "bidirectional"))
      (node (ref "IC9") (pin "2") (pinfunction "VPB[5]_2") (pintype "bidirectional"))
      (node (ref "P8") (pin "37") (pinfunction "37_37") (pintype "passive"))
      (node (ref "R71") (pin "2") (pinfunction "2_2") (pintype "passive"))
    )
    (net (code "75") (name "/LCD.D9.G4--G6") (class "Default")
      (node (ref "C33") (pin "1") (pinfunction "1_1") (pintype "passive"))
      (node (ref "IC1") (pin "U2") (pinfunction "LCD_DATA9_U2") (pintype "bidirectional"))
      (node (ref "IC9") (pin "1") (pinfunction "VPB[6]_1") (pintype "bidirectional"))
      (node (ref "P8") (pin "38") (pinfunction "38_38") (pintype "passive"))
      (node (ref "R69") (pin "2") (pinfunction "2_2") (pintype "passive"))
    )
    (net (code "76") (name "/LCD.D10.G5--G7") (class "Default")
      (node (ref "C32") (pin "1") (pinfunction "1_1") (pintype "passive"))
      (node (ref "IC1") (pin "U3") (pinfunction "LCD_DATA10_U3") (pintype "bidirectional"))
      (node (ref "IC9") (pin "64") (pinfunction "VPB[7]_64") (pintype "bidirectional"))
      (node (ref "P8") (pin "36") (pinfunction "36_36") (pintype "passive"))
      (node (ref "R67") (pin "2") (pinfunction "2_2") (pintype "passive"))
    )
    (net (code "77") (name "/LCD.D11.R0--R3") (class "Default")
      (node (ref "C31") (pin "1") (pinfunction "1_1") (pintype "passive"))
      (node (ref "IC1") (pin "U4") (pinfunction "LCD_DATA11_U4") (pintype "bidirectional"))
      (node (ref "IC9") (pin "60") (pinfunction "VPA[3]_60") (pintype "bidirectional"))
      (node (ref "P8") (pin "34") (pinfunction "34_34") (pintype "passive"))
      (node (ref "R65") (pin "2") (pinfunction "2_2") (pintype "passive"))
    )
    (net (code "78") (name "/LCD.D12.R1--R4") (class "Default")
      (node (ref "C30") (pin "1") (pinfunction "1_1") (pintype "passive"))
      (node (ref "IC1") (pin "V2") (pinfunction "LCD_DATA12_V2") (pintype "bidirectional"))
      (node (ref "IC9") (pin "59") (pinfunction "VPA[4]_59") (pintype "bidirectional"))
      (node (ref "P8") (pin "35") (pinfunction "35_35") (pintype "passive"))
      (node (ref "R63") (pin "2") (pinfunction "2_2") (pintype "passive"))
    )
    (net (code "79") (name "/LCD.D13.R2--R5") (class "Default")
      (node (ref "C29") (pin "1") (pinfunction "1_1") (pintype "passive"))
      (node (ref "IC1") (pin "V3") (pinfunction "LCD_DATA13_V3") (pintype "bidirectional"))
      (node (ref "IC9") (pin "58") (pinfunction "VPA[5]_58") (pintype "bidirectional"))
      (node (ref "P8") (pin "33") (pinfunction "33_33") (pintype "passive"))
      (node (ref "R61") (pin "2") (pinfunction "2_2") (pintype "passive"))
    )
    (net (code "80") (name "/LCD.D14.R3--R6") (class "Default")
      (node (ref "C28") (pin "1") (pinfunction "1_1") (pintype "passive"))
      (node (ref "IC1") (pin "V4") (pinfunction "LCD_DATA14_V4") (pintype "bidirectional"))
      (node (ref "IC9") (pin "57") (pinfunction "VPA[6]_57") (pintype "bidirectional"))
      (node (ref "P8") (pin "31") (pinfunction "31_31") (pintype "passive"))
      (node (ref "R58") (pin "1") (pinfunction "1_1") (pintype "passive"))
    )
    (net (code "81") (name "/LCD.D15.R4--R7") (class "Default")
      (node (ref "C27") (pin "1") (pinfunction "1_1") (pintype "passive"))
      (node (ref "IC1") (pin "T5") (pinfunction "LCD_DATA15_T5") (pintype "bidirectional"))
      (node (ref "IC9") (pin "56") (pinfunction "VPA[7]_56") (pintype "bidirectional"))
      (node (ref "P8") (pin "32") (pinfunction "32_32") (pintype "passive"))
      (node (ref "R57") (pin "2") (pinfunction "2_2") (pintype "passive"))
    )
    (net (code "82") (name "/LCD.ENABLE") (class "Default")
      (node (ref "IC9") (pin "20") (pinfunction "DE/FREF_20") (pintype "bidirectional"))
      (node (ref "P8") (pin "30") (pinfunction "30_30") (pintype "passive"))
      (node (ref "R39") (pin "1") (pinfunction "1_1") (pintype "passive"))
    )
    (net (code "83") (name "/LCD.HSYNC") (class "Default")
      (node (ref "IC9") (pin "22") (pinfunction "HSYNC/HREF_22") (pintype "bidirectional"))
      (node (ref "P8") (pin "29") (pinfunction "29_29") (pintype "passive"))
      (node (ref "R37") (pin "1") (pinfunction "1_1") (pintype "passive"))
    )
    (net (code "84") (name "/LCD.VSYNC") (class "Default")
      (node (ref "IC9") (pin "21") (pinfunction "VSYNC/VREF_21") (pintype "bidirectional"))
      (node (ref "P8") (pin "27") (pinfunction "27_27") (pintype "passive"))
      (node (ref "R35") (pin "1") (pinfunction "1_1") (pintype "passive"))
    )
    (net (code "85") (name "/LDO_PGOOD") (class "Default")
      (node (ref "IC1") (pin "B20") (pinfunction "PMIC_LDO_PGOOD_B20") (pintype "bidirectional"))
      (node (ref "IC1") (pin "B5") (pinfunction "RTC_PORZ_B5") (pintype "bidirectional"))
    )
    (net (code "86") (name "/LS_BUF_OE") (class "Default")
      (node (ref "IC1") (pin "L18") (pinfunction "MII_RXCLK_L18") (pintype "bidirectional"))
      (node (ref "R131") (pin "2") (pinfunction "2_2") (pintype "passive"))
    )
    (net (code "87") (name "/MCU.LCD.CLK") (class "Default")
      (node (ref "IC1") (pin "V5") (pinfunction "LCD_PCLK_V5") (pintype "bidirectional"))
      (node (ref "R34") (pin "2") (pinfunction "2_2") (pintype "passive"))
    )
    (net (code "88") (name "/MCU.LCD.EN") (class "Default")
      (node (ref "IC1") (pin "R6") (pinfunction "LCD_DE_R6") (pintype "bidirectional"))
      (node (ref "R39") (pin "2") (pinfunction "2_2") (pintype "passive"))
    )
    (net (code "89") (name "/MCU.LCD.HS") (class "Default")
      (node (ref "IC1") (pin "R5") (pinfunction "LCD_HSYNC_R5") (pintype "bidirectional"))
      (node (ref "R37") (pin "2") (pinfunction "2_2") (pintype "passive"))
    )
    (net (code "90") (name "/MCU.LCD.VS") (class "Default")
      (node (ref "IC1") (pin "U5") (pinfunction "LCD_VSYNC_U5") (pintype "bidirectional"))
      (node (ref "R35") (pin "2") (pinfunction "2_2") (pintype "passive"))
    )
    (net (code "91") (name "/MMC1_CLK") (class "Default")
      (node (ref "IC1") (pin "U9") (pinfunction "MMC1_CLK_U9") (pintype "bidirectional"))
      (node (ref "IC22") (pin "M6") (pinfunction "CLK_M6") (pintype "bidirectional"))
      (node (ref "P8") (pin "21") (pinfunction "21_21") (pintype "passive"))
      (node (ref "R31") (pin "1") (pinfunction "1_1") (pintype "passive"))
    )
    (net (code "92") (name "/MMC1_CMD") (class "Default")
      (node (ref "IC1") (pin "V9") (pinfunction "MMC1_CMD_V9") (pintype "bidirectional"))
      (node (ref "IC22") (pin "M5") (pinfunction "CMD_M5") (pintype "bidirectional"))
      (node (ref "P8") (pin "20") (pinfunction "20_20") (pintype "passive"))
      (node (ref "R30") (pin "1") (pinfunction "1_1") (pintype "passive"))
    )
    (net (code "93") (name "/MMC1_DAT0") (class "Default")
      (node (ref "IC1") (pin "U7") (pinfunction "MMC1_DAT0_U7") (pintype "bidirectional"))
      (node (ref "IC22") (pin "A3") (pinfunction "DAT0_A3") (pintype "bidirectional"))
      (node (ref "P8") (pin "25") (pinfunction "25_25") (pintype "passive"))
      (node (ref "R12") (pin "1") (pinfunction "1_1") (pintype "passive"))
    )
    (net (code "94") (name "/MMC1_DAT1") (class "Default")
      (node (ref "IC1") (pin "V7") (pinfunction "MMC1_DAT1_V7") (pintype "bidirectional"))
      (node (ref "IC22") (pin "A4") (pinfunction "DAT1_A4") (pintype "bidirectional"))
      (node (ref "P8") (pin "24") (pinfunction "24_24") (pintype "passive"))
      (node (ref "R13") (pin "1") (pinfunction "1_1") (pintype "passive"))
    )
    (net (code "95") (name "/MMC1_DAT2") (class "Default")
      (node (ref "IC1") (pin "R8") (pinfunction "MMC1_DAT2_R8") (pintype "bidirectional"))
      (node (ref "IC22") (pin "A5") (pinfunction "DAT2_A5") (pintype "bidirectional"))
      (node (ref "P8") (pin "5") (pinfunction "5_5") (pintype "passive"))
      (node (ref "R16") (pin "1") (pinfunction "1_1") (pintype "passive"))
    )
    (net (code "96") (name "/MMC1_DAT3") (class "Default")
      (node (ref "IC1") (pin "T8") (pinfunction "MMC1_DAT3_T8") (pintype "bidirectional"))
      (node (ref "IC22") (pin "B2") (pinfunction "DAT3_B2") (pintype "bidirectional"))
      (node (ref "P8") (pin "6") (pinfunction "6_6") (pintype "passive"))
      (node (ref "R18") (pin "1") (pinfunction "1_1") (pintype "passive"))
    )
    (net (code "97") (name "/MMC1_DAT4") (class "Default")
      (node (ref "IC1") (pin "U8") (pinfunction "MMC1_DAT4_U8") (pintype "bidirectional"))
      (node (ref "IC22") (pin "B3") (pinfunction "DAT4_B3") (pintype "bidirectional"))
      (node (ref "P8") (pin "23") (pinfunction "23_23") (pintype "passive"))
      (node (ref "R20") (pin "1") (pinfunction "1_1") (pintype "passive"))
    )
    (net (code "98") (name "/MMC1_DAT5") (class "Default")
      (node (ref "IC1") (pin "V8") (pinfunction "MMC1_DAT5_V8") (pintype "bidirectional"))
      (node (ref "IC22") (pin "B4") (pinfunction "DAT5_B4") (pintype "bidirectional"))
      (node (ref "P8") (pin "22") (pinfunction "22_22") (pintype "passive"))
      (node (ref "R23") (pin "1") (pinfunction "1_1") (pintype "passive"))
    )
    (net (code "99") (name "/MMC1_DAT6") (class "Default")
      (node (ref "IC1") (pin "R9") (pinfunction "MMC1_DAT6_R9") (pintype "bidirectional"))
      (node (ref "IC22") (pin "B5") (pinfunction "DAT6_B5") (pintype "bidirectional"))
      (node (ref "P8") (pin "3") (pinfunction "3_3") (pintype "passive"))
      (node (ref "R25") (pin "1") (pinfunction "1_1") (pintype "passive"))
    )
    (net (code "100") (name "/MMC1_DAT7") (class "Default")
      (node (ref "IC1") (pin "T9") (pinfunction "MMC1_DAT7_T9") (pintype "bidirectional"))
      (node (ref "IC22") (pin "B6") (pinfunction "DAT7_B6") (pintype "bidirectional"))
      (node (ref "P8") (pin "4") (pinfunction "4_4") (pintype "passive"))
      (node (ref "R28") (pin "1") (pinfunction "1_1") (pintype "passive"))
    )
    (net (code "101") (name "/NC1") (class "Default")
      (node (ref "IC1") (pin "K16") (pinfunction "MII1_TXD1_K16") (pintype "bidirectional"))
    )
    (net (code "102") (name "/NC2") (class "Default")
      (node (ref "IC1") (pin "H17") (pinfunction "MII1_CRS_DV_H17") (pintype "bidirectional"))
    )
    (net (code "103") (name "/NC3") (class "Default")
      (node (ref "IC1") (pin "M16") (pinfunction "MII1_RXD0_M16") (pintype "bidirectional"))
    )
    (net (code "104") (name "/NC4") (class "Default")
      (node (ref "IC1") (pin "J15") (pinfunction "MII1_RXERR_J15") (pintype "bidirectional"))
    )
    (net (code "105") (name "/PMIC_INT") (class "Default")
      (node (ref "IC1") (pin "B18") (pinfunction "EXTIN_B18") (pintype "bidirectional"))
      (node (ref "IC1") (pin "B19") (pinfunction "PMIC_INTN_B19") (pintype "bidirectional"))
    )
    (net (code "106") (name "/PMIC_NWAKEUP") (class "Default")
      (node (ref "IC1") (pin "A19") (pinfunction "PMIC_WAKEUPN_A19") (pintype "bidirectional"))
      (node (ref "IC1") (pin "C5") (pinfunction "EXT_WAKEUP_C5") (pintype "bidirectional"))
    )
    (net (code "107") (name "/PMIC_PGOOD") (class "Default")
      (node (ref "IC1") (pin "A20") (pinfunction "PMIC_PGOOD_A20") (pintype "bidirectional"))
      (node (ref "IC1") (pin "B15") (pinfunction "PORZ_B15") (pintype "bidirectional"))
      (node (ref "IC2") (pin "2") (pinfunction "A_2") (pintype "bidirectional"))
    )
    (net (code "108") (name "/PWR_BUT") (class "Default")
      (node (ref "IC1") (pin "D20") (pinfunction "PWR_BUT_D20") (pintype "bidirectional"))
      (node (ref "P9") (pin "9") (pinfunction "9_9") (pintype "passive"))
      (node (ref "POWER") (pin "3") (pinfunction "3_3") (pintype "bidirectional"))
      (node (ref "POWER") (pin "4") (pinfunction "4_4") (pintype "bidirectional"))
    )
    (net (code "109") (name "/RX<-TX") (class "Default")
      (node (ref "IC17") (pin "3") (pinfunction "2Y_3") (pintype "bidirectional"))
      (node (ref "X1") (pin "5") (pinfunction "5_5") (pintype "passive"))
    )
    (net (code "110") (name "/SD.CD") (class "Default")
      (node (ref "IC1") (pin "C15") (pinfunction "MMC0_CD_C15") (pintype "bidirectional"))
      (node (ref "P2") (pin "19") (pinfunction "EMU4_19") (pintype "bidirectional"))
      (node (ref "R7") (pin "1") (pinfunction "1_1") (pintype "passive"))
      (node (ref "X2") (pin "CD") (pinfunction "CD#_CD") (pintype "bidirectional"))
    )
    (net (code "111") (name "/SD.CLK") (class "Default")
      (node (ref "IC1") (pin "G17") (pinfunction "MMC0_CLK0_G17") (pintype "bidirectional"))
      (node (ref "R3") (pin "1") (pinfunction "1_1") (pintype "passive"))
      (node (ref "X2") (pin "5") (pinfunction "CLK_5") (pintype "bidirectional"))
    )
    (net (code "112") (name "/SD.CMD") (class "Default")
      (node (ref "IC1") (pin "G18") (pinfunction "MMC0_CMD_G18") (pintype "bidirectional"))
      (node (ref "R4") (pin "1") (pinfunction "1_1") (pintype "passive"))
      (node (ref "X2") (pin "3") (pinfunction "CMD/DI_3") (pintype "bidirectional"))
    )
    (net (code "113") (name "/SD.D0") (class "Default")
      (node (ref "IC1") (pin "G16") (pinfunction "MMC0_DAT0_G16") (pintype "bidirectional"))
      (node (ref "R2") (pin "1") (pinfunction "1_1") (pintype "passive"))
      (node (ref "X2") (pin "7") (pinfunction "DAT0/DO_7") (pintype "bidirectional"))
    )
    (net (code "114") (name "/SD.D1") (class "Default")
      (node (ref "IC1") (pin "G15") (pinfunction "MMC0_DAT1_G15") (pintype "bidirectional"))
      (node (ref "R1") (pin "1") (pinfunction "1_1") (pintype "passive"))
      (node (ref "X2") (pin "8") (pinfunction "DAT1_8") (pintype "bidirectional"))
    )
    (net (code "115") (name "/SD.D2") (class "Default")
      (node (ref "IC1") (pin "F18") (pinfunction "MMC0_DAT2_F18") (pintype "bidirectional"))
      (node (ref "R6") (pin "1") (pinfunction "1_1") (pintype "passive"))
      (node (ref "X2") (pin "1") (pinfunction "DAT2_1") (pintype "bidirectional"))
    )
    (net (code "116") (name "/SD.D3") (class "Default")
      (node (ref "IC1") (pin "F17") (pinfunction "MMC0_DAT3_F17") (pintype "bidirectional"))
      (node (ref "R5") (pin "1") (pinfunction "1_1") (pintype "passive"))
      (node (ref "X2") (pin "2") (pinfunction "DAT3/CS_2") (pintype "bidirectional"))
    )
    (net (code "117") (name "/SELECT_5V") (class "Default")
      (node (ref "D2") (pin "K") (pinfunction "K_K") (pintype "bidirectional"))
      (node (ref "D3") (pin "K") (pinfunction "K_K") (pintype "bidirectional"))
      (node (ref "D4") (pin "K") (pinfunction "K_K") (pintype "bidirectional"))
      (node (ref "FB1") (pin "1") (pinfunction "P$1_1") (pintype "bidirectional"))
      (node (ref "R97") (pin "1") (pinfunction "1_1") (pintype "passive"))
      (node (ref "TP23") (pin "TP") (pinfunction "TP_TP") (pintype "input"))
    )
    (net (code "118") (name "/SLOW_CLK") (class "Default")
      (node (ref "IC11") (pin "5") (pinfunction "A4_5") (pintype "bidirectional"))
      (node (ref "R91") (pin "1") (pinfunction "1_1") (pintype "passive"))
    )
    (net (code "119") (name "/SPI1_CS0") (class "Default")
      (node (ref "IC1") (pin "C12") (pinfunction "SPI1_CS0_C12") (pintype "bidirectional"))
      (node (ref "IC9") (pin "25") (pinfunction "AP1_25") (pintype "bidirectional"))
      (node (ref "P9") (pin "28") (pinfunction "28_28") (pintype "passive"))
    )
    (net (code "120") (name "/SPI1_D0") (class "Default")
      (node (ref "IC1") (pin "B13") (pinfunction "SPI1_D0_B13") (pintype "bidirectional"))
      (node (ref "IC9") (pin "24") (pinfunction "AP0_24") (pintype "bidirectional"))
      (node (ref "P9") (pin "29") (pinfunction "29_29") (pintype "passive"))
    )
    (net (code "121") (name "/SPI1_D1") (class "Default")
      (node (ref "IC1") (pin "D12") (pinfunction "SPI1_D1_D12") (pintype "bidirectional"))
      (node (ref "P9") (pin "30") (pinfunction "30_30") (pintype "passive"))
    )
    (net (code "122") (name "/SPI1_SCLK") (class "Default")
      (node (ref "IC1") (pin "A13") (pinfunction "SPI1_CLK_A13") (pintype "bidirectional"))
      (node (ref "IC9") (pin "23") (pinfunction "ACLK_23") (pintype "bidirectional"))
      (node (ref "P9") (pin "31") (pinfunction "31_31") (pintype "passive"))
    )
    (net (code "123") (name "/SYS_RESET#") (class "Default")
      (node (ref "C16") (pin "1") (pinfunction "1_1") (pintype "passive"))
      (node (ref "C21") (pin "1") (pinfunction "1_1") (pintype "passive"))
      (node (ref "IC1") (pin "A10") (pinfunction "SYS_RESETN_A10") (pintype "bidirectional"))
      (node (ref "IC2") (pin "4") (pinfunction "Y_4") (pintype "bidirectional"))
      (node (ref "P2") (pin "15") (pinfunction "SRST_15") (pintype "bidirectional"))
      (node (ref "P9") (pin "10") (pinfunction "10_10") (pintype "passive"))
      (node (ref "R32") (pin "2") (pinfunction "2_2") (pintype "passive"))
      (node (ref "RESET") (pin "3") (pinfunction "3_3") (pintype "bidirectional"))
      (node (ref "RESET") (pin "4") (pinfunction "4_4") (pintype "bidirectional"))
    )
    (net (code "124") (name "/TEST") (class "Default")
      (node (ref "IC9") (pin "49") (pinfunction "TEST_49") (pintype "bidirectional"))
      (node (ref "R114") (pin "2") (pinfunction "2_2") (pintype "passive"))
    )
    (net (code "125") (name "/TIMER4") (class "Default")
      (node (ref "IC1") (pin "R7") (pinfunction "TIMER4_R7") (pintype "bidirectional"))
      (node (ref "P8") (pin "7") (pinfunction "7_7") (pintype "passive"))
    )
    (net (code "126") (name "/TIMER5") (class "Default")
      (node (ref "IC1") (pin "T6") (pinfunction "TIMER5_T6") (pintype "bidirectional"))
      (node (ref "P8") (pin "9") (pinfunction "9_9") (pintype "passive"))
    )
    (net (code "127") (name "/TIMER6") (class "Default")
      (node (ref "IC1") (pin "U6") (pinfunction "TIMER6_U6") (pintype "bidirectional"))
      (node (ref "P8") (pin "10") (pinfunction "10_10") (pintype "passive"))
    )
    (net (code "128") (name "/TIMER7") (class "Default")
      (node (ref "IC1") (pin "T7") (pinfunction "TIMER7_T7") (pintype "bidirectional"))
      (node (ref "P8") (pin "8") (pinfunction "8_8") (pintype "passive"))
    )
    (net (code "129") (name "/TX->RX") (class "Default")
      (node (ref "IC17") (pin "2") (pinfunction "1A_2") (pintype "bidirectional"))
      (node (ref "R123") (pin "1") (pinfunction "1_1") (pintype "passive"))
      (node (ref "X1") (pin "4") (pinfunction "4_4") (pintype "passive"))
    )
    (net (code "130") (name "/TX0+") (class "Default")
      (node (ref "IC8") (pin "5") (pinfunction "TMDS.CH2+_5") (pintype "bidirectional"))
      (node (ref "IC9") (pin "40") (pinfunction "TX0+_40") (pintype "bidirectional"))
      (node (ref "X5") (pin "9") (pinfunction "TMDS.DATA0+_9") (pintype "bidirectional"))
    )
    (net (code "131") (name "/TX0-") (class "Default")
      (node (ref "IC8") (pin "4") (pinfunction "TMDS.CH2-_4") (pintype "bidirectional"))
      (node (ref "IC9") (pin "39") (pinfunction "TX0-_39") (pintype "bidirectional"))
      (node (ref "X5") (pin "11") (pinfunction "TMDS.DATA0-_11") (pintype "bidirectional"))
    )
    (net (code "132") (name "/TX1+") (class "Default")
      (node (ref "IC7") (pin "2") (pinfunction "TMDS.CH1+_2") (pintype "bidirectional"))
      (node (ref "IC9") (pin "43") (pinfunction "TX1+_43") (pintype "bidirectional"))
      (node (ref "X5") (pin "6") (pinfunction "TMDS.DATA1+_6") (pintype "bidirectional"))
    )
    (net (code "133") (name "/TX1-") (class "Default")
      (node (ref "IC7") (pin "1") (pinfunction "TMDS.CH1-_1") (pintype "bidirectional"))
      (node (ref "IC9") (pin "42") (pinfunction "TX1-_42") (pintype "bidirectional"))
      (node (ref "X5") (pin "8") (pinfunction "TMDS.DATA1-_8") (pintype "bidirectional"))
    )
    (net (code "134") (name "/TX2+") (class "Default")
      (node (ref "IC7") (pin "5") (pinfunction "TMDS.CH2+_5") (pintype "bidirectional"))
      (node (ref "IC9") (pin "45") (pinfunction "TX2+_45") (pintype "bidirectional"))
      (node (ref "X5") (pin "3") (pinfunction "TMDS.DATA2+_3") (pintype "bidirectional"))
    )
    (net (code "135") (name "/TX2-") (class "Default")
      (node (ref "IC7") (pin "4") (pinfunction "TMDS.CH2-_4") (pintype "bidirectional"))
      (node (ref "IC9") (pin "44") (pinfunction "TX2-_44") (pintype "bidirectional"))
      (node (ref "X5") (pin "5") (pinfunction "TMDS.DATA2-_5") (pintype "bidirectional"))
    )
    (net (code "136") (name "/TXC+") (class "Default")
      (node (ref "IC8") (pin "2") (pinfunction "TMDS.CH1+_2") (pintype "bidirectional"))
      (node (ref "IC9") (pin "38") (pinfunction "TXC+_38") (pintype "bidirectional"))
      (node (ref "X5") (pin "12") (pinfunction "TMDS.CLOCK+_12") (pintype "bidirectional"))
    )
    (net (code "137") (name "/TXC-") (class "Default")
      (node (ref "IC8") (pin "1") (pinfunction "TMDS.CH1-_1") (pintype "bidirectional"))
      (node (ref "IC9") (pin "37") (pinfunction "TXC-_37") (pintype "bidirectional"))
      (node (ref "X5") (pin "14") (pinfunction "TMDS.CLOCK-_14") (pintype "bidirectional"))
    )
    (net (code "138") (name "/UART0_RST#") (class "Default")
      (node (ref "IC1") (pin "E17") (pinfunction "UART0_RSTN_E17") (pintype "bidirectional"))
      (node (ref "TP6") (pin "TP") (pinfunction "TP_TP") (pintype "input"))
    )
    (net (code "139") (name "/UART0_RXD") (class "Default")
      (node (ref "IC1") (pin "E15") (pinfunction "UART0_RXD_E15") (pintype "bidirectional"))
      (node (ref "IC17") (pin "6") (pinfunction "1Y_6") (pintype "bidirectional"))
    )
    (net (code "140") (name "/UART0_TXD") (class "Default")
      (node (ref "IC1") (pin "E16") (pinfunction "UART0_TXD_E16") (pintype "bidirectional"))
      (node (ref "IC17") (pin "5") (pinfunction "2A_5") (pintype "bidirectional"))
    )
    (net (code "141") (name "/UART1_RXD") (class "Default")
      (node (ref "IC1") (pin "D16") (pinfunction "UART1_RXD_D16") (pintype "bidirectional"))
      (node (ref "P9") (pin "26") (pinfunction "26_26") (pintype "passive"))
    )
    (net (code "142") (name "/UART1_TXD") (class "Default")
      (node (ref "IC1") (pin "D15") (pinfunction "UART1_TXD_D15") (pintype "bidirectional"))
      (node (ref "P9") (pin "24") (pinfunction "24_24") (pintype "passive"))
    )
    (net (code "143") (name "/UART2_RXD") (class "Default")
      (node (ref "IC1") (pin "A17") (pinfunction "UART2_RXD_A17") (pintype "bidirectional"))
      (node (ref "P9") (pin "22") (pinfunction "22_22") (pintype "passive"))
    )
    (net (code "144") (name "/UART2_TXD") (class "Default")
      (node (ref "IC1") (pin "B17") (pinfunction "UART2_TXD_B17") (pintype "bidirectional"))
      (node (ref "P9") (pin "21") (pinfunction "21_21") (pintype "passive"))
    )
    (net (code "145") (name "/UART4_RXD") (class "Default")
      (node (ref "IC1") (pin "T17") (pinfunction "UART4_RXD_T17") (pintype "bidirectional"))
      (node (ref "P9") (pin "11") (pinfunction "11_11") (pintype "passive"))
    )
    (net (code "146") (name "/UART4_TXD") (class "Default")
      (node (ref "IC1") (pin "U17") (pinfunction "UART4_TXD_U17") (pintype "bidirectional"))
      (node (ref "P9") (pin "13") (pinfunction "13_13") (pintype "passive"))
    )
    (net (code "147") (name "/USB.CLIENT.D+") (class "Default")
      (node (ref "IC1") (pin "N17") (pinfunction "USB0_DP_N17") (pintype "bidirectional"))
      (node (ref "IC14") (pin "1") (pinfunction "D+_1") (pintype "bidirectional"))
      (node (ref "X4") (pin "D+") (pinfunction "D+_D+") (pintype "input"))
    )
    (net (code "148") (name "/USB.CLIENT.D-") (class "Default")
      (node (ref "IC1") (pin "N18") (pinfunction "USB0_DM_N18") (pintype "bidirectional"))
      (node (ref "IC14") (pin "2") (pinfunction "D-_2") (pintype "bidirectional"))
      (node (ref "X4") (pin "D-") (pinfunction "D-_D-") (pintype "input"))
    )
    (net (code "149") (name "/USB.CLIENT.ID") (class "Default")
      (node (ref "IC1") (pin "P16") (pinfunction "USB0_ID_P16") (pintype "bidirectional"))
      (node (ref "IC14") (pin "3") (pinfunction "ID_3") (pintype "bidirectional"))
      (node (ref "X4") (pin "ID") (pinfunction "ID_ID") (pintype "input"))
    )
    (net (code "150") (name "/USB.HOST.D+") (class "Default")
      (node (ref "IC1") (pin "R17") (pinfunction "USB1_DP_R17") (pintype "bidirectional"))
      (node (ref "IC15") (pin "1") (pinfunction "D+_1") (pintype "bidirectional"))
      (node (ref "X3") (pin "3") (pinfunction "D+_3") (pintype "bidirectional"))
    )
    (net (code "151") (name "/USB.HOST.D-") (class "Default")
      (node (ref "IC1") (pin "R18") (pinfunction "USB1_DM_R18") (pintype "bidirectional"))
      (node (ref "IC15") (pin "2") (pinfunction "D-_2") (pintype "bidirectional"))
      (node (ref "X3") (pin "2") (pinfunction "D-_2") (pintype "bidirectional"))
    )
    (net (code "152") (name "/USB1_DRVVBUS") (class "Default")
      (node (ref "IC1") (pin "F15") (pinfunction "USB1_DRVVBUS_F15") (pintype "bidirectional"))
      (node (ref "IC12") (pin "4") (pinfunction "EN#_4") (pintype "bidirectional"))
      (node (ref "R19") (pin "1") (pinfunction "1_1") (pintype "passive"))
    )
    (net (code "153") (name "/USB1_OC#") (class "Default")
      (node (ref "IC1") (pin "T16") (pinfunction "(USB1_OCN)GPIO1_26_T16") (pintype "bidirectional"))
      (node (ref "IC12") (pin "5") (pinfunction "OC#_5") (pintype "bidirectional"))
      (node (ref "R122") (pin "2") (pinfunction "2_2") (pintype "passive"))
    )
    (net (code "154") (name "/USB1_VBUS") (class "Default")
      (node (ref "FB4") (pin "2") (pinfunction "P$2_2") (pintype "bidirectional"))
      (node (ref "IC1") (pin "T18") (pinfunction "USB1_VBUS_T18") (pintype "bidirectional"))
    )
    (net (code "155") (name "/USR0") (class "Default")
      (node (ref "IC1") (pin "V15") (pinfunction "USR0_V15") (pintype "bidirectional"))
      (node (ref "R104") (pin "2") (pinfunction "2_2") (pintype "passive"))
    )
    (net (code "156") (name "/USR1") (class "Default")
      (node (ref "IC1") (pin "U15") (pinfunction "USR1_U15") (pintype "bidirectional"))
      (node (ref "R100") (pin "2") (pinfunction "2_2") (pintype "passive"))
    )
    (net (code "157") (name "/USR2") (class "Default")
      (node (ref "IC1") (pin "T15") (pinfunction "USR2_T15") (pintype "bidirectional"))
      (node (ref "R96") (pin "2") (pinfunction "2_2") (pintype "passive"))
    )
    (net (code "158") (name "/USR3") (class "Default")
      (node (ref "IC1") (pin "V16") (pinfunction "USR3_V16") (pintype "bidirectional"))
      (node (ref "R92") (pin "2") (pinfunction "2_2") (pintype "passive"))
    )
    (net (code "159") (name "/VIN_BAT") (class "Default")
      (node (ref "IC1") (pin "Y2") (pinfunction "BAT_1_Y2") (pintype "bidirectional"))
      (node (ref "IC1") (pin "Y3") (pinfunction "BAT_2_Y3") (pintype "bidirectional"))
      (node (ref "TP2") (pin "P$1") (pinfunction "TP_P$1") (pintype "bidirectional"))
    )
    (net (code "160") (name "/WL_EN") (class "Default")
      (node (ref "IC11") (pin "3") (pinfunction "A2_3") (pintype "bidirectional"))
      (node (ref "MOD1") (pin "40") (pinfunction "WLAN_EN_40") (pintype "bidirectional"))
      (node (ref "R10") (pin "1") (pinfunction "1_1") (pintype "passive"))
      (node (ref "T3") (pin "G") (pinfunction "G_G") (pintype "bidirectional"))
    )
    (net (code "161") (name "/WL_EN.SIP") (class "Default")
      (node (ref "IC1") (pin "K18") (pinfunction "MII1_TXCLK_K18") (pintype "bidirectional"))
      (node (ref "R136") (pin "1") (pinfunction "1_1") (pintype "passive"))
    )
    (net (code "162") (name "/WL_IRQ") (class "Default")
      (node (ref "IC11") (pin "9") (pinfunction "A8_9") (pintype "bidirectional"))
      (node (ref "R60") (pin "2") (pinfunction "2_2") (pintype "passive"))
    )
    (net (code "163") (name "/WL_IRQ.SIP") (class "Default")
      (node (ref "IC1") (pin "H18") (pinfunction "MII1_REFCLK_H18") (pintype "bidirectional"))
      (node (ref "R134") (pin "1") (pinfunction "1_1") (pintype "passive"))
    )
    (net (code "164") (name "/WL_SDIO_CLK") (class "Default")
      (node (ref "IC10") (pin "6") (pinfunction "A5_6") (pintype "bidirectional"))
      (node (ref "R103") (pin "2") (pinfunction "2_2") (pintype "passive"))
      (node (ref "R64") (pin "2") (pinfunction "2_2") (pintype "passive"))
    )
    (net (code "165") (name "/WL_SDIO_CLK.SIP") (class "Default")
      (node (ref "IC1") (pin "L15") (pinfunction "MII1_RXD1_L15") (pintype "bidirectional"))
      (node (ref "R126") (pin "1") (pinfunction "1_1") (pintype "passive"))
    )
    (net (code "166") (name "/WL_SDIO_CMD") (class "Default")
      (node (ref "IC10") (pin "7") (pinfunction "A6_7") (pintype "bidirectional"))
      (node (ref "R105") (pin "2") (pinfunction "2_2") (pintype "passive"))
      (node (ref "R62") (pin "2") (pinfunction "2_2") (pintype "passive"))
    )
    (net (code "167") (name "/WL_SDIO_CMD.SIP") (class "Default")
      (node (ref "IC1") (pin "J16") (pinfunction "MII1_TXEN_J16") (pintype "bidirectional"))
      (node (ref "R86") (pin "1") (pinfunction "1_1") (pintype "passive"))
    )
    (net (code "168") (name "/WL_SDIO_D0") (class "Default")
      (node (ref "IC10") (pin "1") (pinfunction "A1_1") (pintype "bidirectional"))
      (node (ref "R66") (pin "2") (pinfunction "2_2") (pintype "passive"))
      (node (ref "R98") (pin "2") (pinfunction "2_2") (pintype "passive"))
    )
    (net (code "169") (name "/WL_SDIO_D0.SIP") (class "Default")
      (node (ref "IC1") (pin "J17") (pinfunction "MII1_RXDV_J17") (pintype "bidirectional"))
      (node (ref "R130") (pin "1") (pinfunction "1_1") (pintype "passive"))
    )
    (net (code "170") (name "/WL_SDIO_D1") (class "Default")
      (node (ref "IC10") (pin "3") (pinfunction "A2_3") (pintype "bidirectional"))
      (node (ref "R68") (pin "2") (pinfunction "2_2") (pintype "passive"))
      (node (ref "R99") (pin "2") (pinfunction "2_2") (pintype "passive"))
    )
    (net (code "171") (name "/WL_SDIO_D1.SIP") (class "Default")
      (node (ref "IC1") (pin "J18") (pinfunction "MII1_TXD3_J18") (pintype "bidirectional"))
      (node (ref "R129") (pin "1") (pinfunction "1_1") (pintype "passive"))
    )
    (net (code "172") (name "/WL_SDIO_D2") (class "Default")
      (node (ref "IC10") (pin "4") (pinfunction "A3_4") (pintype "bidirectional"))
      (node (ref "R101") (pin "2") (pinfunction "2_2") (pintype "passive"))
      (node (ref "R70") (pin "2") (pinfunction "2_2") (pintype "passive"))
    )
    (net (code "173") (name "/WL_SDIO_D2.SIP") (class "Default")
      (node (ref "IC1") (pin "K15") (pinfunction "MII1_TXD2_K15") (pintype "bidirectional"))
      (node (ref "R128") (pin "1") (pinfunction "1_1") (pintype "passive"))
    )
    (net (code "174") (name "/WL_SDIO_D3") (class "Default")
      (node (ref "IC10") (pin "5") (pinfunction "A4_5") (pintype "bidirectional"))
      (node (ref "R102") (pin "2") (pinfunction "2_2") (pintype "passive"))
      (node (ref "R72") (pin "2") (pinfunction "2_2") (pintype "passive"))
    )
    (net (code "175") (name "/WL_SDIO_D3.SIP") (class "Default")
      (node (ref "IC1") (pin "H16") (pinfunction "MII1_COL_H16") (pintype "bidirectional"))
      (node (ref "R127") (pin "1") (pinfunction "1_1") (pintype "passive"))
    )
    (net (code "176") (name "/XDMA_EVENT_INTRO") (class "Default")
      (node (ref "FB5") (pin "2") (pinfunction "2_2") (pintype "passive"))
      (node (ref "IC13") (pin "1") (pinfunction "CLK_1") (pintype "bidirectional"))
      (node (ref "P2") (pin "17") (pinfunction "EMU2_17") (pintype "bidirectional"))
    )
    (net (code "177") (name "1.8V-WIFI") (class "Default")
      (node (ref "C11") (pin "+") (pinfunction "+_+") (pintype "passive"))
      (node (ref "C24") (pin "1") (pinfunction "1_1") (pintype "passive"))
      (node (ref "C25") (pin "1") (pinfunction "1_1") (pintype "passive"))
      (node (ref "C43") (pin "1") (pinfunction "1_1") (pintype "passive"))
      (node (ref "C64") (pin "1") (pinfunction "1_1") (pintype "passive"))
      (node (ref "C8") (pin "1") (pinfunction "1_1") (pintype "passive"))
      (node (ref "IC10") (pin "2") (pinfunction "VCCA_2") (pintype "bidirectional"))
      (node (ref "IC11") (pin "2") (pinfunction "VCCA_2") (pintype "bidirectional"))
      (node (ref "IC19") (pin "5") (pinfunction "VOUT_5") (pintype "bidirectional"))
      (node (ref "MOD1") (pin "38") (pinfunction "VIO_38") (pintype "bidirectional"))
      (node (ref "OSC2") (pin "4") (pinfunction "VCC_4") (pintype "bidirectional"))
      (node (ref "R101") (pin "1") (pinfunction "1_1") (pintype "passive"))
      (node (ref "R102") (pin "1") (pinfunction "1_1") (pintype "passive"))
      (node (ref "R103") (pin "1") (pinfunction "1_1") (pintype "passive"))
      (node (ref "R105") (pin "1") (pinfunction "1_1") (pintype "passive"))
      (node (ref "R111") (pin "1") (pinfunction "1_1") (pintype "passive"))
      (node (ref "R90") (pin "1") (pinfunction "1_1") (pintype "passive"))
      (node (ref "R98") (pin "1") (pinfunction "1_1") (pintype "passive"))
      (node (ref "R99") (pin "1") (pinfunction "1_1") (pintype "passive"))
    )
    (net (code "178") (name "3.3V-WIFI") (class "Default")
      (node (ref "C10") (pin "1") (pinfunction "1_1") (pintype "passive"))
      (node (ref "C20") (pin "1") (pinfunction "1_1") (pintype "passive"))
      (node (ref "C23") (pin "+") (pinfunction "+_+") (pintype "passive"))
      (node (ref "C44") (pin "1") (pinfunction "1_1") (pintype "passive"))
      (node (ref "C45") (pin "1") (pinfunction "1_1") (pintype "passive"))
      (node (ref "C61") (pin "1") (pinfunction "1_1") (pintype "passive"))
      (node (ref "C63") (pin "1") (pinfunction "1_1") (pintype "passive"))
      (node (ref "IC10") (pin "19") (pinfunction "VCCB_19") (pintype "bidirectional"))
      (node (ref "IC11") (pin "19") (pinfunction "VCCB_19") (pintype "bidirectional"))
      (node (ref "IC18") (pin "4") (pinfunction "OUT_4") (pintype "bidirectional"))
      (node (ref "IC19") (pin "1") (pinfunction "VIN_1") (pintype "bidirectional"))
      (node (ref "IC19") (pin "3") (pinfunction "EN_3") (pintype "bidirectional"))
      (node (ref "MOD1") (pin "46") (pinfunction "VBAT_IN1_46") (pintype "bidirectional"))
      (node (ref "MOD1") (pin "47") (pinfunction "VBAT_IN2_47") (pintype "bidirectional"))
      (node (ref "R124") (pin "2") (pinfunction "2_2") (pintype "passive"))
      (node (ref "R125") (pin "2") (pinfunction "2_2") (pintype "passive"))
      (node (ref "R93") (pin "1") (pinfunction "1_1") (pintype "passive"))
    )
    (net (code "179") (name "AGND") (class "Default")
      (node (ref "IC1") (pin "A6") (pinfunction "AGND_1_A6") (pintype "bidirectional"))
      (node (ref "IC1") (pin "A9") (pinfunction "AGND_0_A9") (pintype "bidirectional"))
      (node (ref "IC1") (pin "E8") (pinfunction "AGND_E8") (pintype "bidirectional"))
      (node (ref "P9") (pin "34") (pinfunction "34_34") (pintype "passive"))
    )
    (net (code "180") (name "CGND") (class "Default")
      (node (ref "MGT1") (pin "P$1") (pinfunction "P$1_P$1") (pintype "bidirectional"))
      (node (ref "MGT2") (pin "P$1") (pinfunction "P$1_P$1") (pintype "bidirectional"))
      (node (ref "MGT3") (pin "P$1") (pinfunction "P$1_P$1") (pintype "bidirectional"))
      (node (ref "MGT4") (pin "P$1") (pinfunction "P$1_P$1") (pintype "bidirectional"))
      (node (ref "R17") (pin "2") (pinfunction "2_2") (pintype "passive"))
      (node (ref "X2") (pin "CGND1") (pinfunction "CGND1_CGND1") (pintype "bidirectional"))
      (node (ref "X2") (pin "CGND2") (pinfunction "CGND2_CGND2") (pintype "bidirectional"))
      (node (ref "X2") (pin "CGND3") (pinfunction "CGND3_CGND3") (pintype "bidirectional"))
      (node (ref "X2") (pin "CGND4") (pinfunction "CGND4_CGND4") (pintype "bidirectional"))
      (node (ref "X2") (pin "CGND5") (pinfunction "CGND5_CGND5") (pintype "bidirectional"))
      (node (ref "X2") (pin "CGND6") (pinfunction "CGND6_CGND6") (pintype "bidirectional"))
      (node (ref "X3") (pin "5") (pinfunction "CG1_5") (pintype "bidirectional"))
      (node (ref "X3") (pin "6") (pinfunction "CG2_6") (pintype "bidirectional"))
      (node (ref "X4") (pin "CGND1") (pinfunction "SGND1_CGND1") (pintype "bidirectional"))
      (node (ref "X4") (pin "CGND2") (pinfunction "SGND2_CGND2") (pintype "bidirectional"))
      (node (ref "X4") (pin "CGND3") (pinfunction "SGND3_CGND3") (pintype "bidirectional"))
      (node (ref "X4") (pin "CGND4") (pinfunction "SGND4_CGND4") (pintype "bidirectional"))
      (node (ref "X4") (pin "CGND5") (pinfunction "SGND5_CGND5") (pintype "bidirectional"))
      (node (ref "X4") (pin "CGND6") (pinfunction "SGND6_CGND6") (pintype "bidirectional"))
      (node (ref "X5") (pin "CG1") (pinfunction "CG1_CG1") (pintype "bidirectional"))
      (node (ref "X5") (pin "CG2") (pinfunction "CG2_CG2") (pintype "bidirectional"))
      (node (ref "X5") (pin "CG3") (pinfunction "CG3_CG3") (pintype "bidirectional"))
      (node (ref "X5") (pin "CG4") (pinfunction "CG4_CG4") (pintype "bidirectional"))
    )
    (net (code "181") (name "GND") (class "Default")
      (node (ref "ANT1") (pin "GND1") (pinfunction "GND1_GND1") (pintype "bidirectional"))
      (node (ref "ANT1") (pin "GND2") (pinfunction "GND2_GND2") (pintype "bidirectional"))
      (node (ref "ANT2") (pin "GND1") (pinfunction "GND1_GND1") (pintype "bidirectional"))
      (node (ref "ANT2") (pin "GND2") (pinfunction "GND2_GND2") (pintype "bidirectional"))
      (node (ref "C1") (pin "2") (pinfunction "2_2") (pintype "passive"))
      (node (ref "C10") (pin "2") (pinfunction "2_2") (pintype "passive"))
      (node (ref "C11") (pin "-") (pinfunction "-_-") (pintype "passive"))
      (node (ref "C12") (pin "2") (pinfunction "2_2") (pintype "passive"))
      (node (ref "C13") (pin "2") (pinfunction "2_2") (pintype "passive"))
      (node (ref "C14") (pin "2") (pinfunction "2_2") (pintype "passive"))
      (node (ref "C15") (pin "2") (pinfunction "2_2") (pintype "passive"))
      (node (ref "C16") (pin "2") (pinfunction "2_2") (pintype "passive"))
      (node (ref "C17") (pin "2") (pinfunction "2_2") (pintype "passive"))
      (node (ref "C18") (pin "2") (pinfunction "2_2") (pintype "passive"))
      (node (ref "C19") (pin "2") (pinfunction "2_2") (pintype "passive"))
      (node (ref "C2") (pin "2") (pinfunction "2_2") (pintype "passive"))
      (node (ref "C20") (pin "2") (pinfunction "2_2") (pintype "passive"))
      (node (ref "C21") (pin "2") (pinfunction "2_2") (pintype "passive"))
      (node (ref "C22") (pin "2") (pinfunction "2_2") (pintype "passive"))
      (node (ref "C23") (pin "-") (pinfunction "-_-") (pintype "passive"))
      (node (ref "C24") (pin "2") (pinfunction "2_2") (pintype "passive"))
      (node (ref "C25") (pin "2") (pinfunction "2_2") (pintype "passive"))
      (node (ref "C27") (pin "2") (pinfunction "2_2") (pintype "passive"))
      (node (ref "C28") (pin "2") (pinfunction "2_2") (pintype "passive"))
      (node (ref "C29") (pin "2") (pinfunction "2_2") (pintype "passive"))
      (node (ref "C30") (pin "2") (pinfunction "2_2") (pintype "passive"))
      (node (ref "C31") (pin "2") (pinfunction "2_2") (pintype "passive"))
      (node (ref "C32") (pin "2") (pinfunction "2_2") (pintype "passive"))
      (node (ref "C33") (pin "2") (pinfunction "2_2") (pintype "passive"))
      (node (ref "C34") (pin "2") (pinfunction "2_2") (pintype "passive"))
      (node (ref "C35") (pin "2") (pinfunction "2_2") (pintype "passive"))
      (node (ref "C36") (pin "2") (pinfunction "2_2") (pintype "passive"))
      (node (ref "C37") (pin "2") (pinfunction "2_2") (pintype "passive"))
      (node (ref "C38") (pin "2") (pinfunction "2_2") (pintype "passive"))
      (node (ref "C39") (pin "2") (pinfunction "2_2") (pintype "passive"))
      (node (ref "C40") (pin "2") (pinfunction "2_2") (pintype "passive"))
      (node (ref "C41") (pin "2") (pinfunction "2_2") (pintype "passive"))
      (node (ref "C42") (pin "2") (pinfunction "2_2") (pintype "passive"))
      (node (ref "C43") (pin "2") (pinfunction "2_2") (pintype "passive"))
      (node (ref "C44") (pin "2") (pinfunction "2_2") (pintype "passive"))
      (node (ref "C45") (pin "2") (pinfunction "2_2") (pintype "passive"))
      (node (ref "C47") (pin "2") (pinfunction "2_2") (pintype "passive"))
      (node (ref "C48") (pin "2") (pinfunction "2_2") (pintype "passive"))
      (node (ref "C49") (pin "2") (pinfunction "2_2") (pintype "passive"))
      (node (ref "C50") (pin "2") (pinfunction "2_2") (pintype "passive"))
      (node (ref "C51") (pin "2") (pinfunction "2_2") (pintype "passive"))
      (node (ref "C52") (pin "2") (pinfunction "2_2") (pintype "passive"))
      (node (ref "C53") (pin "2") (pinfunction "2_2") (pintype "passive"))
      (node (ref "C54") (pin "2") (pinfunction "2_2") (pintype "passive"))
      (node (ref "C55") (pin "2") (pinfunction "2_2") (pintype "passive"))
      (node (ref "C56") (pin "2") (pinfunction "2_2") (pintype "passive"))
      (node (ref "C57") (pin "2") (pinfunction "2_2") (pintype "passive"))
      (node (ref "C58") (pin "2") (pinfunction "2_2") (pintype "passive"))
      (node (ref "C59") (pin "2") (pinfunction "2_2") (pintype "passive"))
      (node (ref "C61") (pin "2") (pinfunction "2_2") (pintype "passive"))
      (node (ref "C62") (pin "-") (pinfunction "-_-") (pintype "passive"))
      (node (ref "C63") (pin "2") (pinfunction "2_2") (pintype "passive"))
      (node (ref "C64") (pin "2") (pinfunction "2_2") (pintype "passive"))
      (node (ref "C69") (pin "2") (pinfunction "2_2") (pintype "passive"))
      (node (ref "C7") (pin "2") (pinfunction "2_2") (pintype "passive"))
      (node (ref "C8") (pin "2") (pinfunction "2_2") (pintype "passive"))
      (node (ref "C9") (pin "2") (pinfunction "2_2") (pintype "passive"))
      (node (ref "D8") (pin "2") (pinfunction "A2_2") (pintype "passive"))
      (node (ref "IC1") (pin "A1") (pinfunction "DGND1_A1") (pintype "bidirectional"))
      (node (ref "IC1") (pin "A18") (pinfunction "DGND2_A18") (pintype "bidirectional"))
      (node (ref "IC1") (pin "E19") (pinfunction "DGND3_E19") (pintype "bidirectional"))
      (node (ref "IC1") (pin "E20") (pinfunction "DGND4_E20") (pintype "bidirectional"))
      (node (ref "IC1") (pin "F19") (pinfunction "DGND6_F19") (pintype "bidirectional"))
      (node (ref "IC1") (pin "F8") (pinfunction "DGND5_F8") (pintype "bidirectional"))
      (node (ref "IC1") (pin "G11") (pinfunction "DGND9_G11") (pintype "bidirectional"))
      (node (ref "IC1") (pin "G12") (pinfunction "DGND10_G12") (pintype "bidirectional"))
      (node (ref "IC1") (pin "G19") (pinfunction "DGND11_G19") (pintype "bidirectional"))
      (node (ref "IC1") (pin "G8") (pinfunction "DGND7_G8") (pintype "bidirectional"))
      (node (ref "IC1") (pin "G9") (pinfunction "DGND8_G9") (pintype "bidirectional"))
      (node (ref "IC1") (pin "H10") (pinfunction "DGND16_H10") (pintype "bidirectional"))
      (node (ref "IC1") (pin "H12") (pinfunction "DGND17_H12") (pintype "bidirectional"))
      (node (ref "IC1") (pin "H19") (pinfunction "DGND18_H19") (pintype "bidirectional"))
      (node (ref "IC1") (pin "H6") (pinfunction "DGND12_H6") (pintype "bidirectional"))
      (node (ref "IC1") (pin "H7") (pinfunction "DGND13_H7") (pintype "bidirectional"))
      (node (ref "IC1") (pin "H8") (pinfunction "DGND14_H8") (pintype "bidirectional"))
      (node (ref "IC1") (pin "H9") (pinfunction "DGND15_H9") (pintype "bidirectional"))
      (node (ref "IC1") (pin "J10") (pinfunction "DGND23_J10") (pintype "bidirectional"))
      (node (ref "IC1") (pin "J11") (pinfunction "DGND24_J11") (pintype "bidirectional"))
      (node (ref "IC1") (pin "J19") (pinfunction "DGND25_J19") (pintype "bidirectional"))
      (node (ref "IC1") (pin "J20") (pinfunction "DGND26_J20") (pintype "bidirectional"))
      (node (ref "IC1") (pin "J6") (pinfunction "DGND19_J6") (pintype "bidirectional"))
      (node (ref "IC1") (pin "J7") (pinfunction "DGND20_J7") (pintype "bidirectional"))
      (node (ref "IC1") (pin "J8") (pinfunction "DGND21_J8") (pintype "bidirectional"))
      (node (ref "IC1") (pin "J9") (pinfunction "DGND22_J9") (pintype "bidirectional"))
      (node (ref "IC1") (pin "K10") (pinfunction "DGND29_K10") (pintype "bidirectional"))
      (node (ref "IC1") (pin "K11") (pinfunction "DGND30_K11") (pintype "bidirectional"))
      (node (ref "IC1") (pin "K19") (pinfunction "DGND31_K19") (pintype "bidirectional"))
      (node (ref "IC1") (pin "K7") (pinfunction "DGND27_K7") (pintype "bidirectional"))
      (node (ref "IC1") (pin "K9") (pinfunction "DGND28_K9") (pintype "bidirectional"))
      (node (ref "IC1") (pin "L10") (pinfunction "DGND32_L10") (pintype "bidirectional"))
      (node (ref "IC1") (pin "L11") (pinfunction "DGND33_L11") (pintype "bidirectional"))
      (node (ref "IC1") (pin "L12") (pinfunction "DGND34_L12") (pintype "bidirectional"))
      (node (ref "IC1") (pin "L13") (pinfunction "DGND35_L13") (pintype "bidirectional"))
      (node (ref "IC1") (pin "L19") (pinfunction "DGND36_L19") (pintype "bidirectional"))
      (node (ref "IC1") (pin "M10") (pinfunction "DGND42_M10") (pintype "bidirectional"))
      (node (ref "IC1") (pin "M12") (pinfunction "DGND43_M12") (pintype "bidirectional"))
      (node (ref "IC1") (pin "M14") (pinfunction "DGND44_M14") (pintype "bidirectional"))
      (node (ref "IC1") (pin "M19") (pinfunction "DGND45_M19") (pintype "bidirectional"))
      (node (ref "IC1") (pin "M6") (pinfunction "DGND38_M6") (pintype "bidirectional"))
      (node (ref "IC1") (pin "M7") (pinfunction "DGND39_M7") (pintype "bidirectional"))
      (node (ref "IC1") (pin "M8") (pinfunction "DGND40_M8") (pintype "bidirectional"))
      (node (ref "IC1") (pin "M9") (pinfunction "DGND41_M9") (pintype "bidirectional"))
      (node (ref "IC1") (pin "N10") (pinfunction "DGND47_N10") (pintype "bidirectional"))
      (node (ref "IC1") (pin "N11") (pinfunction "DGND48_N11") (pintype "bidirectional"))
      (node (ref "IC1") (pin "N14") (pinfunction "DGND49_N14") (pintype "bidirectional"))
      (node (ref "IC1") (pin "N19") (pinfunction "DGND50_N19") (pintype "bidirectional"))
      (node (ref "IC1") (pin "N20") (pinfunction "DGND51_N20") (pintype "bidirectional"))
      (node (ref "IC1") (pin "N7") (pinfunction "DGND46_N7") (pintype "bidirectional"))
      (node (ref "IC1") (pin "P19") (pinfunction "DGND52_P19") (pintype "bidirectional"))
      (node (ref "IC1") (pin "P20") (pinfunction "DGND53_P20") (pintype "bidirectional"))
      (node (ref "IC1") (pin "R19") (pinfunction "DGND54_R19") (pintype "bidirectional"))
      (node (ref "IC1") (pin "R20") (pinfunction "DGND55_R20") (pintype "bidirectional"))
      (node (ref "IC1") (pin "T19") (pinfunction "DGND56_T19") (pintype "bidirectional"))
      (node (ref "IC1") (pin "T20") (pinfunction "DGND57_T20") (pintype "bidirectional"))
      (node (ref "IC1") (pin "U19") (pinfunction "DGND58_U19") (pintype "bidirectional"))
      (node (ref "IC1") (pin "V1") (pinfunction "DGND59_V1") (pintype "bidirectional"))
      (node (ref "IC1") (pin "V18") (pinfunction "DGND60_V18") (pintype "bidirectional"))
      (node (ref "IC1") (pin "V19") (pinfunction "DGND61_V19") (pintype "bidirectional"))
      (node (ref "IC1") (pin "W10") (pinfunction "DGND70_W10") (pintype "bidirectional"))
      (node (ref "IC1") (pin "W11") (pinfunction "DGND71_W11") (pintype "bidirectional"))
      (node (ref "IC1") (pin "W12") (pinfunction "DGND72_W12") (pintype "bidirectional"))
      (node (ref "IC1") (pin "W13") (pinfunction "DGND73_W13") (pintype "bidirectional"))
      (node (ref "IC1") (pin "W14") (pinfunction "DGND74_W14") (pintype "bidirectional"))
      (node (ref "IC1") (pin "W15") (pinfunction "DGND75_W15") (pintype "bidirectional"))
      (node (ref "IC1") (pin "W16") (pinfunction "DGND76_W16") (pintype "bidirectional"))
      (node (ref "IC1") (pin "W17") (pinfunction "DGND77_W17") (pintype "bidirectional"))
      (node (ref "IC1") (pin "W18") (pinfunction "DGND78_W18") (pintype "bidirectional"))
      (node (ref "IC1") (pin "W19") (pinfunction "DGND79_W19") (pintype "bidirectional"))
      (node (ref "IC1") (pin "W2") (pinfunction "DGND62_W2") (pintype "bidirectional"))
      (node (ref "IC1") (pin "W20") (pinfunction "DGND80_W20") (pintype "bidirectional"))
      (node (ref "IC1") (pin "W3") (pinfunction "DGND63_W3") (pintype "bidirectional"))
      (node (ref "IC1") (pin "W5") (pinfunction "DGND65_W5") (pintype "bidirectional"))
      (node (ref "IC1") (pin "W6") (pinfunction "DGND66_W6") (pintype "bidirectional"))
      (node (ref "IC1") (pin "W7") (pinfunction "DGND67_W7") (pintype "bidirectional"))
      (node (ref "IC1") (pin "W8") (pinfunction "DGND68_W8") (pintype "bidirectional"))
      (node (ref "IC1") (pin "W9") (pinfunction "DGND69_W9") (pintype "bidirectional"))
      (node (ref "IC1") (pin "Y10") (pinfunction "DGND83_Y10") (pintype "bidirectional"))
      (node (ref "IC1") (pin "Y12") (pinfunction "DGND84_Y12") (pintype "bidirectional"))
      (node (ref "IC1") (pin "Y15") (pinfunction "DGND85_Y15") (pintype "bidirectional"))
      (node (ref "IC1") (pin "Y18") (pinfunction "DGND86_Y18") (pintype "bidirectional"))
      (node (ref "IC1") (pin "Y7") (pinfunction "DGND82_Y7") (pintype "bidirectional"))
      (node (ref "IC10") (pin "11") (pinfunction "GND_11") (pintype "bidirectional"))
      (node (ref "IC10") (pin "TP") (pinfunction "TP_TP") (pintype "bidirectional"))
      (node (ref "IC11") (pin "11") (pinfunction "GND_11") (pintype "bidirectional"))
      (node (ref "IC11") (pin "TP") (pinfunction "TP_TP") (pintype "bidirectional"))
      (node (ref "IC12") (pin "1") (pinfunction "GND_1") (pintype "bidirectional"))
      (node (ref "IC12") (pin "9") (pinfunction "THERMAL_9") (pintype "bidirectional"))
      (node (ref "IC13") (pin "4") (pinfunction "GND_4") (pintype "bidirectional"))
      (node (ref "IC14") (pin "4") (pinfunction "GND_4") (pintype "bidirectional"))
      (node (ref "IC15") (pin "4") (pinfunction "GND_4") (pintype "bidirectional"))
      (node (ref "IC17") (pin "1") (pinfunction "1OE#_1") (pintype "bidirectional"))
      (node (ref "IC17") (pin "4") (pinfunction "GND_4") (pintype "bidirectional"))
      (node (ref "IC18") (pin "3") (pinfunction "GND1_3") (pintype "bidirectional"))
      (node (ref "IC18") (pin "6") (pinfunction "GND2_6") (pintype "bidirectional"))
      (node (ref "IC19") (pin "2") (pinfunction "GND_2") (pintype "bidirectional"))
      (node (ref "IC2") (pin "3") (pinfunction "GND_3") (pintype "bidirectional"))
      (node (ref "IC22") (pin "C4") (pinfunction "VSSQ1_C4") (pintype "bidirectional"))
      (node (ref "IC22") (pin "E7") (pinfunction "VSS1_E7") (pintype "bidirectional"))
      (node (ref "IC22") (pin "G5") (pinfunction "VSS2_G5") (pintype "bidirectional"))
      (node (ref "IC22") (pin "H10") (pinfunction "VSS3_H10") (pintype "bidirectional"))
      (node (ref "IC22") (pin "K8") (pinfunction "VSS4_K8") (pintype "bidirectional"))
      (node (ref "IC22") (pin "N2") (pinfunction "VSSQ2_N2") (pintype "bidirectional"))
      (node (ref "IC22") (pin "N5") (pinfunction "VSSQ3_N5") (pintype "bidirectional"))
      (node (ref "IC22") (pin "P4") (pinfunction "VSSQ4_P4") (pintype "bidirectional"))
      (node (ref "IC22") (pin "P6") (pinfunction "VSSQ5_P6") (pintype "bidirectional"))
      (node (ref "IC3") (pin "3") (pinfunction "GND_3") (pintype "bidirectional"))
      (node (ref "IC4") (pin "2") (pinfunction "VSS_2") (pintype "bidirectional"))
      (node (ref "IC7") (pin "3") (pinfunction "GND1_3") (pintype "bidirectional"))
      (node (ref "IC7") (pin "8") (pinfunction "GND2_8") (pintype "bidirectional"))
      (node (ref "IC8") (pin "3") (pinfunction "GND1_3") (pintype "bidirectional"))
      (node (ref "IC8") (pin "8") (pinfunction "GND2_8") (pintype "bidirectional"))
      (node (ref "IC9") (pin "16") (pinfunction "VPC[2]_16") (pintype "bidirectional"))
      (node (ref "IC9") (pin "17") (pinfunction "VPC[1]_17") (pintype "bidirectional"))
      (node (ref "IC9") (pin "18") (pinfunction "VPC[0]_18") (pintype "bidirectional"))
      (node (ref "IC9") (pin "19") (pinfunction "VPP_19") (pintype "bidirectional"))
      (node (ref "IC9") (pin "53") (pinfunction "A0_I2C_53") (pintype "bidirectional"))
      (node (ref "IC9") (pin "54") (pinfunction "A1_I2C_54") (pintype "bidirectional"))
      (node (ref "IC9") (pin "61") (pinfunction "VPA[2]_61") (pintype "bidirectional"))
      (node (ref "IC9") (pin "62") (pinfunction "VPA[1]_62") (pintype "bidirectional"))
      (node (ref "IC9") (pin "63") (pinfunction "VPA[0]_63") (pintype "bidirectional"))
      (node (ref "IC9") (pin "65") (pinfunction "GND.PAD_65") (pintype "bidirectional"))
      (node (ref "IC9") (pin "8") (pinfunction "VPB[1]_8") (pintype "bidirectional"))
      (node (ref "IC9") (pin "9") (pinfunction "VPB[0]_9") (pintype "bidirectional"))
      (node (ref "MOD1") (pin "1") (pinfunction "GND1_1") (pintype "bidirectional"))
      (node (ref "MOD1") (pin "15") (pinfunction "GND4_15") (pintype "bidirectional"))
      (node (ref "MOD1") (pin "16") (pinfunction "GND5_16") (pintype "bidirectional"))
      (node (ref "MOD1") (pin "17") (pinfunction "GND6_17") (pintype "bidirectional"))
      (node (ref "MOD1") (pin "19") (pinfunction "GND7_19") (pintype "bidirectional"))
      (node (ref "MOD1") (pin "20") (pinfunction "GND8_20") (pintype "bidirectional"))
      (node (ref "MOD1") (pin "23") (pinfunction "GND9_23") (pintype "bidirectional"))
      (node (ref "MOD1") (pin "24") (pinfunction "GND10_24") (pintype "bidirectional"))
      (node (ref "MOD1") (pin "28") (pinfunction "GND11_28") (pintype "bidirectional"))
      (node (ref "MOD1") (pin "29") (pinfunction "GND12_29") (pintype "bidirectional"))
      (node (ref "MOD1") (pin "30") (pinfunction "GND13_30") (pintype "bidirectional"))
      (node (ref "MOD1") (pin "31") (pinfunction "GND14_31") (pintype "bidirectional"))
      (node (ref "MOD1") (pin "33") (pinfunction "GND15_33") (pintype "bidirectional"))
      (node (ref "MOD1") (pin "34") (pinfunction "GND16_34") (pintype "bidirectional"))
      (node (ref "MOD1") (pin "35") (pinfunction "GND17_35") (pintype "bidirectional"))
      (node (ref "MOD1") (pin "37") (pinfunction "GND18_37") (pintype "bidirectional"))
      (node (ref "MOD1") (pin "39") (pinfunction "GND19_39") (pintype "bidirectional"))
      (node (ref "MOD1") (pin "44") (pinfunction "GND20_44") (pintype "bidirectional"))
      (node (ref "MOD1") (pin "45") (pinfunction "GND21_45") (pintype "bidirectional"))
      (node (ref "MOD1") (pin "48") (pinfunction "GND22_48") (pintype "bidirectional"))
      (node (ref "MOD1") (pin "49") (pinfunction "GND23_49") (pintype "bidirectional"))
      (node (ref "MOD1") (pin "54") (pinfunction "GND24_54") (pintype "bidirectional"))
      (node (ref "MOD1") (pin "55") (pinfunction "GND25_55") (pintype "bidirectional"))
      (node (ref "MOD1") (pin "59") (pinfunction "GND26_59") (pintype "bidirectional"))
      (node (ref "MOD1") (pin "61") (pinfunction "GND27_61") (pintype "bidirectional"))
      (node (ref "MOD1") (pin "63") (pinfunction "GND28_63") (pintype "bidirectional"))
      (node (ref "MOD1") (pin "64") (pinfunction "GND29_64") (pintype "bidirectional"))
      (node (ref "MOD1") (pin "7") (pinfunction "GND2_7") (pintype "bidirectional"))
      (node (ref "MOD1") (pin "9") (pinfunction "GND3_9") (pintype "bidirectional"))
      (node (ref "MOD1") (pin "G1") (pinfunction "G1_G1") (pintype "bidirectional"))
      (node (ref "MOD1") (pin "G10") (pinfunction "G10_G10") (pintype "bidirectional"))
      (node (ref "MOD1") (pin "G11") (pinfunction "G11_G11") (pintype "bidirectional"))
      (node (ref "MOD1") (pin "G12") (pinfunction "G12_G12") (pintype "bidirectional"))
      (node (ref "MOD1") (pin "G13") (pinfunction "G13_G13") (pintype "bidirectional"))
      (node (ref "MOD1") (pin "G14") (pinfunction "G14_G14") (pintype "bidirectional"))
      (node (ref "MOD1") (pin "G15") (pinfunction "G15_G15") (pintype "bidirectional"))
      (node (ref "MOD1") (pin "G16") (pinfunction "G16_G16") (pintype "bidirectional"))
      (node (ref "MOD1") (pin "G17") (pinfunction "G17_G17") (pintype "bidirectional"))
      (node (ref "MOD1") (pin "G18") (pinfunction "G18_G18") (pintype "bidirectional"))
      (node (ref "MOD1") (pin "G19") (pinfunction "G19_G19") (pintype "bidirectional"))
      (node (ref "MOD1") (pin "G2") (pinfunction "G2_G2") (pintype "bidirectional"))
      (node (ref "MOD1") (pin "G20") (pinfunction "G20_G20") (pintype "bidirectional"))
      (node (ref "MOD1") (pin "G21") (pinfunction "G21_G21") (pintype "bidirectional"))
      (node (ref "MOD1") (pin "G22") (pinfunction "G22_G22") (pintype "bidirectional"))
      (node (ref "MOD1") (pin "G23") (pinfunction "G23_G23") (pintype "bidirectional"))
      (node (ref "MOD1") (pin "G24") (pinfunction "G24_G24") (pintype "bidirectional"))
      (node (ref "MOD1") (pin "G25") (pinfunction "G25_G25") (pintype "bidirectional"))
      (node (ref "MOD1") (pin "G26") (pinfunction "G26_G26") (pintype "bidirectional"))
      (node (ref "MOD1") (pin "G27") (pinfunction "G27_G27") (pintype "bidirectional"))
      (node (ref "MOD1") (pin "G28") (pinfunction "G28_G28") (pintype "bidirectional"))
      (node (ref "MOD1") (pin "G29") (pinfunction "G29_G29") (pintype "bidirectional"))
      (node (ref "MOD1") (pin "G3") (pinfunction "G3_G3") (pintype "bidirectional"))
      (node (ref "MOD1") (pin "G30") (pinfunction "G30_G30") (pintype "bidirectional"))
      (node (ref "MOD1") (pin "G31") (pinfunction "G31_G31") (pintype "bidirectional"))
      (node (ref "MOD1") (pin "G32") (pinfunction "G32_G32") (pintype "bidirectional"))
      (node (ref "MOD1") (pin "G33") (pinfunction "G33_G33") (pintype "bidirectional"))
      (node (ref "MOD1") (pin "G34") (pinfunction "G34_G34") (pintype "bidirectional"))
      (node (ref "MOD1") (pin "G35") (pinfunction "G35_G35") (pintype "bidirectional"))
      (node (ref "MOD1") (pin "G36") (pinfunction "G36_G36") (pintype "bidirectional"))
      (node (ref "MOD1") (pin "G4") (pinfunction "G4_G4") (pintype "bidirectional"))
      (node (ref "MOD1") (pin "G5") (pinfunction "G5_G5") (pintype "bidirectional"))
      (node (ref "MOD1") (pin "G6") (pinfunction "G6_G6") (pintype "bidirectional"))
      (node (ref "MOD1") (pin "G7") (pinfunction "G7_G7") (pintype "bidirectional"))
      (node (ref "MOD1") (pin "G8") (pinfunction "G8_G8") (pintype "bidirectional"))
      (node (ref "MOD1") (pin "G9") (pinfunction "G9_G9") (pintype "bidirectional"))
      (node (ref "OSC1") (pin "2") (pinfunction "GND_2") (pintype "bidirectional"))
      (node (ref "OSC2") (pin "2") (pinfunction "GND_2") (pintype "bidirectional"))
      (node (ref "P2") (pin "10") (pinfunction "GND2_10") (pintype "bidirectional"))
      (node (ref "P2") (pin "12") (pinfunction "GND3_12") (pintype "bidirectional"))
      (node (ref "P2") (pin "16") (pinfunction "GND4_16") (pintype "bidirectional"))
      (node (ref "P2") (pin "20") (pinfunction "GND5_20") (pintype "bidirectional"))
      (node (ref "P2") (pin "4") (pinfunction "TDIS_4") (pintype "bidirectional"))
      (node (ref "P2") (pin "8") (pinfunction "GND1_8") (pintype "bidirectional"))
      (node (ref "P8") (pin "1") (pinfunction "1_1") (pintype "passive"))
      (node (ref "P8") (pin "2") (pinfunction "2_2") (pintype "passive"))
      (node (ref "P9") (pin "1") (pinfunction "1_1") (pintype "passive"))
      (node (ref "P9") (pin "2") (pinfunction "2_2") (pintype "passive"))
      (node (ref "P9") (pin "43") (pinfunction "43_43") (pintype "passive"))
      (node (ref "P9") (pin "44") (pinfunction "44_44") (pintype "passive"))
      (node (ref "P9") (pin "45") (pinfunction "45_45") (pintype "passive"))
      (node (ref "P9") (pin "46") (pinfunction "46_46") (pintype "passive"))
      (node (ref "POWER") (pin "1") (pinfunction "1_1") (pintype "bidirectional"))
      (node (ref "POWER") (pin "2") (pinfunction "2_2") (pintype "bidirectional"))
      (node (ref "R10") (pin "2") (pinfunction "2_2") (pintype "passive"))
      (node (ref "R106") (pin "2") (pinfunction "2_2") (pintype "passive"))
      (node (ref "R108") (pin "2") (pinfunction "2_2") (pintype "passive"))
      (node (ref "R109") (pin "2") (pinfunction "2_2") (pintype "passive"))
      (node (ref "R11") (pin "2") (pinfunction "2_2") (pintype "passive"))
      (node (ref "R114") (pin "1") (pinfunction "1_1") (pintype "passive"))
      (node (ref "R119") (pin "2") (pinfunction "2_2") (pintype "passive"))
      (node (ref "R123") (pin "2") (pinfunction "2_2") (pintype "passive"))
      (node (ref "R17") (pin "1") (pinfunction "1_1") (pintype "passive"))
      (node (ref "R19") (pin "2") (pinfunction "2_2") (pintype "passive"))
      (node (ref "R22") (pin "2") (pinfunction "2_2") (pintype "passive"))
      (node (ref "R24") (pin "1") (pinfunction "1_1") (pintype "passive"))
      (node (ref "R27") (pin "2") (pinfunction "2_2") (pintype "passive"))
      (node (ref "R52") (pin "2") (pinfunction "2_2") (pintype "passive"))
      (node (ref "R55") (pin "1") (pinfunction "1_1") (pintype "passive"))
      (node (ref "R57") (pin "1") (pinfunction "1_1") (pintype "passive"))
      (node (ref "R61") (pin "1") (pinfunction "1_1") (pintype "passive"))
      (node (ref "R63") (pin "1") (pinfunction "1_1") (pintype "passive"))
      (node (ref "R65") (pin "1") (pinfunction "1_1") (pintype "passive"))
      (node (ref "R67") (pin "1") (pinfunction "1_1") (pintype "passive"))
      (node (ref "R69") (pin "1") (pinfunction "1_1") (pintype "passive"))
      (node (ref "R71") (pin "1") (pinfunction "1_1") (pintype "passive"))
      (node (ref "R73") (pin "1") (pinfunction "1_1") (pintype "passive"))
      (node (ref "R75") (pin "1") (pinfunction "1_1") (pintype "passive"))
      (node (ref "R85") (pin "1") (pinfunction "1_1") (pintype "passive"))
      (node (ref "R87") (pin "1") (pinfunction "1_1") (pintype "passive"))
      (node (ref "R94") (pin "2") (pinfunction "2_2") (pintype "passive"))
      (node (ref "R95") (pin "2") (pinfunction "2_2") (pintype "passive"))
      (node (ref "RESET") (pin "1") (pinfunction "1_1") (pintype "bidirectional"))
      (node (ref "RESET") (pin "2") (pinfunction "2_2") (pintype "bidirectional"))
      (node (ref "S2") (pin "3") (pinfunction "3_3") (pintype "bidirectional"))
      (node (ref "S2") (pin "4") (pinfunction "4_4") (pintype "bidirectional"))
      (node (ref "T3") (pin "S") (pinfunction "S_S") (pintype "bidirectional"))
      (node (ref "T4") (pin "S") (pinfunction "S_S") (pintype "bidirectional"))
      (node (ref "TP5") (pin "P$1") (pinfunction "TP_P$1") (pintype "bidirectional"))
      (node (ref "USR0") (pin "K") (pinfunction "K_K") (pintype "passive"))
      (node (ref "USR1") (pin "K") (pinfunction "K_K") (pintype "passive"))
      (node (ref "USR2") (pin "K") (pinfunction "K_K") (pintype "passive"))
      (node (ref "USR3") (pin "K") (pinfunction "K_K") (pintype "passive"))
      (node (ref "X1") (pin "1") (pinfunction "1_1") (pintype "passive"))
      (node (ref "X12") (pin "OUT") (pinfunction "OUT_OUT") (pintype "bidirectional"))
      (node (ref "X2") (pin "6") (pinfunction "VSS_6") (pintype "bidirectional"))
      (node (ref "X2") (pin "GND") (pinfunction "GND_GND") (pintype "bidirectional"))
      (node (ref "X3") (pin "4") (pinfunction "GND_4") (pintype "bidirectional"))
      (node (ref "X4") (pin "GND") (pinfunction "GND_GND") (pintype "input"))
      (node (ref "X5") (pin "10") (pinfunction "TMDS.DATA0.SHIELD_10") (pintype "bidirectional"))
      (node (ref "X5") (pin "13") (pinfunction "TMDS.CLOCK.SHIELD_13") (pintype "bidirectional"))
      (node (ref "X5") (pin "16") (pinfunction "DDC/CEC.GND_16") (pintype "bidirectional"))
      (node (ref "X5") (pin "4") (pinfunction "TMDS.DATA2.SHIELD_4") (pintype "bidirectional"))
      (node (ref "X5") (pin "7") (pinfunction "TMDS.DATA1.SHIELD_7") (pintype "bidirectional"))
    )
    (net (code "182") (name "HDMI_1V8") (class "Default")
      (node (ref "C50") (pin "1") (pinfunction "1_1") (pintype "passive"))
      (node (ref "C51") (pin "1") (pinfunction "1_1") (pintype "passive"))
      (node (ref "C52") (pin "1") (pinfunction "1_1") (pintype "passive"))
      (node (ref "C53") (pin "1") (pinfunction "1_1") (pintype "passive"))
      (node (ref "C54") (pin "1") (pinfunction "1_1") (pintype "passive"))
      (node (ref "C55") (pin "1") (pinfunction "1_1") (pintype "passive"))
      (node (ref "C56") (pin "1") (pinfunction "1_1") (pintype "passive"))
      (node (ref "C57") (pin "1") (pinfunction "1_1") (pintype "passive"))
      (node (ref "FB2") (pin "2") (pinfunction "P$2_2") (pintype "bidirectional"))
      (node (ref "IC9") (pin "14") (pinfunction "VDDD1(IO)(1V8)_14") (pintype "bidirectional"))
      (node (ref "IC9") (pin "29") (pinfunction "VDDDC2_29") (pintype "bidirectional"))
      (node (ref "IC9") (pin "35") (pinfunction "VDDA(1V8)_35") (pintype "bidirectional"))
      (node (ref "IC9") (pin "36") (pinfunction "VDDA1(TX)(1V8)_36") (pintype "bidirectional"))
      (node (ref "IC9") (pin "41") (pinfunction "VDDA2(TX)(1V8)_41") (pintype "bidirectional"))
      (node (ref "IC9") (pin "46") (pinfunction "VDDA3(TX)(1V8)_46") (pintype "bidirectional"))
      (node (ref "IC9") (pin "47") (pinfunction "VDDA1(PLL)(1V8)_47") (pintype "bidirectional"))
      (node (ref "IC9") (pin "48") (pinfunction "VDDA2(PLL)(1V8)_48") (pintype "bidirectional"))
      (node (ref "IC9") (pin "5") (pinfunction "VDDDC1_5") (pintype "bidirectional"))
      (node (ref "IC9") (pin "55") (pinfunction "VDDD2(IO)(1V8)_55") (pintype "bidirectional"))
    )
    (net (code "183") (name "Net-(ANT1-PadSIG)") (class "Default")
      (node (ref "ANT1") (pin "SIG") (pinfunction "SIG_SIG") (pintype "bidirectional"))
      (node (ref "C46") (pin "1") (pinfunction "1_1") (pintype "passive"))
    )
    (net (code "184") (name "Net-(ANT2-PadSIG)") (class "Default")
      (node (ref "ANT2") (pin "SIG") (pinfunction "SIG_SIG") (pintype "bidirectional"))
      (node (ref "C60") (pin "1") (pinfunction "1_1") (pintype "passive"))
    )
    (net (code "185") (name "Net-(BT-PadA)") (class "Default")
      (node (ref "BT") (pin "A") (pinfunction "A_A") (pintype "passive"))
      (node (ref "R124") (pin "1") (pinfunction "1_1") (pintype "passive"))
    )
    (net (code "186") (name "Net-(BT-PadK)") (class "Default")
      (node (ref "BT") (pin "K") (pinfunction "K_K") (pintype "passive"))
      (node (ref "T4") (pin "D") (pinfunction "D_D") (pintype "bidirectional"))
    )
    (net (code "187") (name "Net-(D1-ANODE)") (class "Default")
      (node (ref "D1") (pin "A") (pinfunction "ANODE_A") (pintype "bidirectional"))
      (node (ref "R120") (pin "2") (pinfunction "2_2") (pintype "passive"))
    )
    (net (code "188") (name "Net-(FB3-P$1)") (class "Default")
      (node (ref "C58") (pin "1") (pinfunction "1_1") (pintype "passive"))
      (node (ref "FB3") (pin "1") (pinfunction "P$1_1") (pintype "bidirectional"))
      (node (ref "FB4") (pin "1") (pinfunction "P$1_1") (pintype "bidirectional"))
      (node (ref "IC12") (pin "6") (pinfunction "OUT1_6") (pintype "bidirectional"))
      (node (ref "IC12") (pin "7") (pinfunction "OUT2_7") (pintype "bidirectional"))
      (node (ref "IC12") (pin "8") (pinfunction "OUT3_8") (pintype "bidirectional"))
      (node (ref "IC15") (pin "6") (pinfunction "VBUS_6") (pintype "bidirectional"))
    )
    (net (code "189") (name "Net-(FB3-P$2)") (class "Default")
      (node (ref "FB3") (pin "2") (pinfunction "P$2_2") (pintype "bidirectional"))
      (node (ref "X3") (pin "1") (pinfunction "VBUS_1") (pintype "bidirectional"))
    )
    (net (code "190") (name "Net-(IC1A-(EMMC_RSTN)GPIO1_20)") (class "Default")
      (node (ref "IC1") (pin "R14") (pinfunction "(EMMC_RSTN)GPIO1_20_R14") (pintype "bidirectional"))
      (node (ref "IC3") (pin "2") (pinfunction "A_2") (pintype "bidirectional"))
    )
    (net (code "191") (name "Net-(IC1A-CLKOUT1)") (class "Default")
      (node (ref "FB5") (pin "1") (pinfunction "1_1") (pintype "passive"))
      (node (ref "IC1") (pin "A15") (pinfunction "CLKOUT1_A15") (pintype "bidirectional"))
    )
    (net (code "192") (name "Net-(IC1A-CLKOUT2)") (class "Default")
      (node (ref "FB7") (pin "2") (pinfunction "2_2") (pintype "passive"))
      (node (ref "IC1") (pin "D14") (pinfunction "CLKOUT2_D14") (pintype "bidirectional"))
    )
    (net (code "193") (name "Net-(IC1A-DGND0)") (class "Default")
      (node (ref "C3") (pin "2") (pinfunction "2_2") (pintype "passive"))
      (node (ref "C4") (pin "2") (pinfunction "2_2") (pintype "passive"))
      (node (ref "IC1") (pin "L20") (pinfunction "DGND0_L20") (pintype "bidirectional"))
    )
    (net (code "194") (name "Net-(IC1A-DGND1)") (class "Default")
      (node (ref "C5") (pin "2") (pinfunction "2_2") (pintype "passive"))
      (node (ref "C6") (pin "2") (pinfunction "2_2") (pintype "passive"))
      (node (ref "IC1") (pin "G20") (pinfunction "DGND1_G20") (pintype "bidirectional"))
    )
    (net (code "195") (name "Net-(IC1A-GPIO3_20)") (class "Default")
      (node (ref "IC1") (pin "D13") (pinfunction "GPIO3_20_D13") (pintype "bidirectional"))
      (node (ref "R14") (pin "2") (pinfunction "2_2") (pintype "passive"))
    )
    (net (code "196") (name "Net-(IC1A-OSC0_IN)") (class "Default")
      (node (ref "C3") (pin "1") (pinfunction "1_1") (pintype "passive"))
      (node (ref "IC1") (pin "M20") (pinfunction "OSC0_IN_M20") (pintype "bidirectional"))
      (node (ref "Q4") (pin "2") (pinfunction "P$2_2") (pintype "passive"))
      (node (ref "R8") (pin "2") (pinfunction "2_2") (pintype "passive"))
    )
    (net (code "197") (name "Net-(IC1A-OSC0_OUT)") (class "Default")
      (node (ref "C4") (pin "1") (pinfunction "1_1") (pintype "passive"))
      (node (ref "IC1") (pin "K20") (pinfunction "OSC0_OUT_K20") (pintype "bidirectional"))
      (node (ref "Q4") (pin "1") (pinfunction "P$1_1") (pintype "passive"))
      (node (ref "R8") (pin "1") (pinfunction "1_1") (pintype "passive"))
    )
    (net (code "198") (name "Net-(IC1A-OSC1_IN)") (class "Default")
      (node (ref "C5") (pin "1") (pinfunction "1_1") (pintype "passive"))
      (node (ref "IC1") (pin "H20") (pinfunction "OSC1_IN_H20") (pintype "bidirectional"))
      (node (ref "Q2") (pin "P$1") (pinfunction "P$1_P$1") (pintype "passive"))
      (node (ref "R56") (pin "2") (pinfunction "2_2") (pintype "passive"))
    )
    (net (code "199") (name "Net-(IC1A-OSC1_OUT)") (class "Default")
      (node (ref "C6") (pin "1") (pinfunction "1_1") (pintype "passive"))
      (node (ref "IC1") (pin "F20") (pinfunction "OSC1_OUT_F20") (pintype "bidirectional"))
      (node (ref "Q2") (pin "P$2") (pinfunction "P$2_P$2") (pintype "passive"))
      (node (ref "R56") (pin "1") (pinfunction "1_1") (pintype "passive"))
    )
    (net (code "200") (name "Net-(IC1B-AIN7)") (class "Default")
      (node (ref "IC1") (pin "C9") (pinfunction "AIN7_C9") (pintype "bidirectional"))
      (node (ref "R21") (pin "2") (pinfunction "2_2") (pintype "passive"))
      (node (ref "R22") (pin "1") (pinfunction "1_1") (pintype "passive"))
    )
    (net (code "201") (name "Net-(IC1B-GPIO0_7)") (class "Default")
      (node (ref "IC1") (pin "C18") (pinfunction "GPIO0_7_C18") (pintype "bidirectional"))
      (node (ref "R36") (pin "2") (pinfunction "2_2") (pintype "passive"))
    )
    (net (code "202") (name "Net-(IC1B-GPIO3_18)") (class "Default")
      (node (ref "IC1") (pin "B12") (pinfunction "GPIO3_18_B12") (pintype "bidirectional"))
      (node (ref "R38") (pin "2") (pinfunction "2_2") (pintype "passive"))
    )
    (net (code "203") (name "Net-(IC1B-USB0_VBUS)") (class "Default")
      (node (ref "IC1") (pin "P15") (pinfunction "USB0_VBUS_P15") (pintype "bidirectional"))
      (node (ref "R26") (pin "1") (pinfunction "1_1") (pintype "passive"))
    )
    (net (code "204") (name "Net-(IC1B-USB1_ID)") (class "Default")
      (node (ref "IC1") (pin "P17") (pinfunction "USB1_ID_P17") (pintype "bidirectional"))
      (node (ref "R27") (pin "1") (pinfunction "1_1") (pintype "passive"))
    )
    (net (code "205") (name "Net-(IC1C-PMIC_POWER_EN)") (class "Default")
      (node (ref "IC1") (pin "C6") (pinfunction "PMIC_POWER_EN_C6") (pintype "bidirectional"))
      (node (ref "IC1") (pin "D19") (pinfunction "PWR_EN_D19") (pintype "bidirectional"))
    )
    (net (code "206") (name "Net-(IC1E-RTC_KALDO_ENN)") (class "Default")
      (node (ref "IC1") (pin "B4") (pinfunction "RTC_KALDO_ENN_B4") (pintype "bidirectional"))
      (node (ref "R24") (pin "2") (pinfunction "2_2") (pintype "passive"))
    )
    (net (code "207") (name "Net-(IC3-Y)") (class "Default")
      (node (ref "IC3") (pin "4") (pinfunction "Y_4") (pintype "bidirectional"))
      (node (ref "R29") (pin "2") (pinfunction "2_2") (pintype "passive"))
    )
    (net (code "208") (name "Net-(IC4-WP)") (class "Default")
      (node (ref "IC4") (pin "5") (pinfunction "WP_5") (pintype "bidirectional"))
      (node (ref "R40") (pin "2") (pinfunction "2_2") (pintype "passive"))
      (node (ref "TP1") (pin "P$1") (pinfunction "TP_P$1") (pintype "bidirectional"))
    )
    (net (code "209") (name "Net-(IC5-C)") (class "Default")
      (node (ref "IC5") (pin "2") (pinfunction "C_2") (pintype "passive"))
      (node (ref "R44") (pin "2") (pinfunction "2_2") (pintype "passive"))
      (node (ref "R45") (pin "1") (pinfunction "1_1") (pintype "passive"))
      (node (ref "T1") (pin "B") (pinfunction "B_B") (pintype "passive"))
    )
    (net (code "210") (name "Net-(IC5-FB)") (class "Default")
      (node (ref "IC5") (pin "1") (pinfunction "FB_1") (pintype "passive"))
      (node (ref "R45") (pin "2") (pinfunction "2_2") (pintype "passive"))
      (node (ref "R46") (pin "2") (pinfunction "2_2") (pintype "passive"))
      (node (ref "R47") (pin "1") (pinfunction "1_1") (pintype "passive"))
    )
    (net (code "211") (name "Net-(IC6-C)") (class "Default")
      (node (ref "IC6") (pin "2") (pinfunction "C_2") (pintype "passive"))
      (node (ref "R48") (pin "2") (pinfunction "2_2") (pintype "passive"))
      (node (ref "R49") (pin "1") (pinfunction "1_1") (pintype "passive"))
      (node (ref "T2") (pin "B") (pinfunction "B_B") (pintype "passive"))
    )
    (net (code "212") (name "Net-(IC6-FB)") (class "Default")
      (node (ref "IC6") (pin "1") (pinfunction "FB_1") (pintype "passive"))
      (node (ref "R49") (pin "2") (pinfunction "2_2") (pintype "passive"))
      (node (ref "R50") (pin "2") (pinfunction "2_2") (pintype "passive"))
      (node (ref "R51") (pin "1") (pinfunction "1_1") (pintype "passive"))
    )
    (net (code "213") (name "Net-(IC9-DSCL)") (class "Default")
      (node (ref "IC9") (pin "33") (pinfunction "DSCL_33") (pintype "bidirectional"))
      (node (ref "R115") (pin "2") (pinfunction "2_2") (pintype "passive"))
      (node (ref "X5") (pin "17") (pinfunction "SCL_17") (pintype "bidirectional"))
    )
    (net (code "214") (name "Net-(IC9-DSDA)") (class "Default")
      (node (ref "IC9") (pin "32") (pinfunction "DSDA_32") (pintype "bidirectional"))
      (node (ref "R118") (pin "2") (pinfunction "2_2") (pintype "passive"))
      (node (ref "X5") (pin "18") (pinfunction "SDA_18") (pintype "bidirectional"))
    )
    (net (code "215") (name "Net-(IC10-B1)") (class "Default")
      (node (ref "IC10") (pin "20") (pinfunction "B1_20") (pintype "bidirectional"))
      (node (ref "R130") (pin "2") (pinfunction "2_2") (pintype "passive"))
    )
    (net (code "216") (name "Net-(IC10-B2)") (class "Default")
      (node (ref "IC10") (pin "18") (pinfunction "B2_18") (pintype "bidirectional"))
      (node (ref "R129") (pin "2") (pinfunction "2_2") (pintype "passive"))
    )
    (net (code "217") (name "Net-(IC10-B3)") (class "Default")
      (node (ref "IC10") (pin "17") (pinfunction "B3_17") (pintype "bidirectional"))
      (node (ref "R128") (pin "2") (pinfunction "2_2") (pintype "passive"))
    )
    (net (code "218") (name "Net-(IC10-B4)") (class "Default")
      (node (ref "IC10") (pin "16") (pinfunction "B4_16") (pintype "bidirectional"))
      (node (ref "R127") (pin "2") (pinfunction "2_2") (pintype "passive"))
    )
    (net (code "219") (name "Net-(IC10-B5)") (class "Default")
      (node (ref "IC10") (pin "15") (pinfunction "B5_15") (pintype "bidirectional"))
      (node (ref "R126") (pin "2") (pinfunction "2_2") (pintype "passive"))
    )
    (net (code "220") (name "Net-(IC10-B6)") (class "Default")
      (node (ref "IC10") (pin "14") (pinfunction "B6_14") (pintype "bidirectional"))
      (node (ref "R86") (pin "2") (pinfunction "2_2") (pintype "passive"))
    )
    (net (code "221") (name "Net-(IC10-OE)") (class "Default")
      (node (ref "IC10") (pin "10") (pinfunction "OE_10") (pintype "bidirectional"))
      (node (ref "IC11") (pin "10") (pinfunction "OE_10") (pintype "bidirectional"))
      (node (ref "R106") (pin "1") (pinfunction "1_1") (pintype "passive"))
      (node (ref "R131") (pin "1") (pinfunction "1_1") (pintype "passive"))
    )
    (net (code "222") (name "Net-(IC11-B2)") (class "Default")
      (node (ref "IC11") (pin "18") (pinfunction "B2_18") (pintype "bidirectional"))
      (node (ref "R136") (pin "2") (pinfunction "2_2") (pintype "passive"))
    )
    (net (code "223") (name "Net-(IC11-B3)") (class "Default")
      (node (ref "IC11") (pin "17") (pinfunction "B3_17") (pintype "bidirectional"))
      (node (ref "R135") (pin "2") (pinfunction "2_2") (pintype "passive"))
    )
    (net (code "224") (name "Net-(IC11-B8)") (class "Default")
      (node (ref "IC11") (pin "12") (pinfunction "B8_12") (pintype "bidirectional"))
      (node (ref "R134") (pin "2") (pinfunction "2_2") (pintype "passive"))
    )
    (net (code "225") (name "Net-(IC13-Q)") (class "Default")
      (node (ref "FB6") (pin "1") (pinfunction "1_1") (pintype "passive"))
      (node (ref "IC13") (pin "5") (pinfunction "Q_5") (pintype "bidirectional"))
    )
    (net (code "226") (name "Net-(IC18-ADJ)") (class "Default")
      (node (ref "IC18") (pin "5") (pinfunction "ADJ_5") (pintype "bidirectional"))
      (node (ref "R93") (pin "2") (pinfunction "2_2") (pintype "passive"))
      (node (ref "R94") (pin "1") (pinfunction "1_1") (pintype "passive"))
    )
    (net (code "227") (name "Net-(IC18-SHDN#)") (class "Default")
      (node (ref "IC18") (pin "1") (pinfunction "SHDN#_1") (pintype "bidirectional"))
      (node (ref "R89") (pin "2") (pinfunction "2_2") (pintype "passive"))
      (node (ref "R97") (pin "2") (pinfunction "2_2") (pintype "passive"))
    )
    (net (code "228") (name "Net-(IC22-VDDI)") (class "Default")
      (node (ref "C69") (pin "1") (pinfunction "1_1") (pintype "passive"))
      (node (ref "C7") (pin "1") (pinfunction "1_1") (pintype "passive"))
      (node (ref "IC22") (pin "C2") (pinfunction "VDDI_C2") (pintype "bidirectional"))
    )
    (net (code "229") (name "Net-(MOD1-BT_AUD_CLK)") (class "Default")
      (node (ref "MOD1") (pin "60") (pinfunction "BT_AUD_CLK_60") (pintype "bidirectional"))
      (node (ref "TP19") (pin "TP") (pinfunction "TP_TP") (pintype "input"))
    )
    (net (code "230") (name "Net-(MOD1-BT_AUD_FSYNC)") (class "Default")
      (node (ref "MOD1") (pin "58") (pinfunction "BT_AUD_FSYNC_58") (pintype "bidirectional"))
      (node (ref "TP18") (pin "TP") (pinfunction "TP_TP") (pintype "input"))
    )
    (net (code "231") (name "Net-(MOD1-BT_AUD_IN)") (class "Default")
      (node (ref "MOD1") (pin "56") (pinfunction "BT_AUD_IN_56") (pintype "bidirectional"))
      (node (ref "TP16") (pin "TP") (pinfunction "TP_TP") (pintype "input"))
    )
    (net (code "232") (name "Net-(MOD1-BT_AUD_OUT)") (class "Default")
      (node (ref "MOD1") (pin "57") (pinfunction "BT_AUD_OUT_57") (pintype "bidirectional"))
      (node (ref "TP17") (pin "TP") (pinfunction "TP_TP") (pintype "input"))
    )
    (net (code "233") (name "Net-(MOD1-BT_HCI_CTS)") (class "Default")
      (node (ref "MOD1") (pin "51") (pinfunction "BT_HCI_CTS_51") (pintype "bidirectional"))
      (node (ref "R141") (pin "1") (pinfunction "1_1") (pintype "passive"))
    )
    (net (code "234") (name "Net-(MOD1-BT_HCI_RTS)") (class "Default")
      (node (ref "MOD1") (pin "50") (pinfunction "BT_HCI_RTS_50") (pintype "bidirectional"))
      (node (ref "R140") (pin "1") (pinfunction "1_1") (pintype "passive"))
    )
    (net (code "235") (name "Net-(MOD1-BT_HCI_RX)") (class "Default")
      (node (ref "MOD1") (pin "53") (pinfunction "BT_HCI_RX_53") (pintype "bidirectional"))
      (node (ref "R143") (pin "1") (pinfunction "1_1") (pintype "passive"))
    )
    (net (code "236") (name "Net-(MOD1-BT_HCI_TX)") (class "Default")
      (node (ref "MOD1") (pin "52") (pinfunction "BT_HCI_TX_52") (pintype "bidirectional"))
      (node (ref "R142") (pin "1") (pinfunction "1_1") (pintype "passive"))
    )
    (net (code "237") (name "Net-(MOD1-BT_UART_DBG)") (class "Default")
      (node (ref "MOD1") (pin "43") (pinfunction "BT_UART_DBG_43") (pintype "bidirectional"))
      (node (ref "TP15") (pin "TP") (pinfunction "TP_TP") (pintype "input"))
    )
    (net (code "238") (name "Net-(MOD1-GPIO1)") (class "Default")
      (node (ref "MOD1") (pin "27") (pinfunction "GPIO1_27") (pintype "bidirectional"))
      (node (ref "TP13") (pin "TP") (pinfunction "TP_TP") (pintype "input"))
    )
    (net (code "239") (name "Net-(MOD1-GPIO2)") (class "Default")
      (node (ref "MOD1") (pin "26") (pinfunction "GPIO2_26") (pintype "bidirectional"))
      (node (ref "TP12") (pin "TP") (pinfunction "TP_TP") (pintype "input"))
    )
    (net (code "240") (name "Net-(MOD1-RF_ANT1)") (class "Default")
      (node (ref "C46") (pin "2") (pinfunction "2_2") (pintype "passive"))
      (node (ref "MOD1") (pin "32") (pinfunction "RF_ANT1_32") (pintype "bidirectional"))
    )
    (net (code "241") (name "Net-(MOD1-RF_ANT2)") (class "Default")
      (node (ref "C60") (pin "2") (pinfunction "2_2") (pintype "passive"))
      (node (ref "MOD1") (pin "18") (pinfunction "RF_ANT2_18") (pintype "bidirectional"))
    )
    (net (code "242") (name "Net-(MOD1-WLAN_IRQ)") (class "Default")
      (node (ref "MOD1") (pin "14") (pinfunction "WLAN_IRQ_14") (pintype "bidirectional"))
      (node (ref "R111") (pin "2") (pinfunction "2_2") (pintype "passive"))
      (node (ref "R60") (pin "1") (pinfunction "1_1") (pintype "passive"))
    )
    (net (code "243") (name "Net-(MOD1-WL_SDIO_CLK)") (class "Default")
      (node (ref "MOD1") (pin "8") (pinfunction "WL_SDIO_CLK_8") (pintype "bidirectional"))
      (node (ref "R64") (pin "1") (pinfunction "1_1") (pintype "passive"))
    )
    (net (code "244") (name "Net-(MOD1-WL_SDIO_CMD)") (class "Default")
      (node (ref "MOD1") (pin "6") (pinfunction "WL_SDIO_CMD_6") (pintype "bidirectional"))
      (node (ref "R62") (pin "1") (pinfunction "1_1") (pintype "passive"))
    )
    (net (code "245") (name "Net-(MOD1-WL_SDIO_D0)") (class "Default")
      (node (ref "MOD1") (pin "10") (pinfunction "WL_SDIO_D0_10") (pintype "bidirectional"))
      (node (ref "R66") (pin "1") (pinfunction "1_1") (pintype "passive"))
    )
    (net (code "246") (name "Net-(MOD1-WL_SDIO_D1)") (class "Default")
      (node (ref "MOD1") (pin "11") (pinfunction "WL_SDIO_D1_11") (pintype "bidirectional"))
      (node (ref "R68") (pin "1") (pinfunction "1_1") (pintype "passive"))
    )
    (net (code "247") (name "Net-(MOD1-WL_SDIO_D2)") (class "Default")
      (node (ref "MOD1") (pin "12") (pinfunction "WL_SDIO_D2_12") (pintype "bidirectional"))
      (node (ref "R70") (pin "1") (pinfunction "1_1") (pintype "passive"))
    )
    (net (code "248") (name "Net-(MOD1-WL_SDIO_D3)") (class "Default")
      (node (ref "MOD1") (pin "13") (pinfunction "WL_SDIO_D3_13") (pintype "bidirectional"))
      (node (ref "R72") (pin "1") (pinfunction "1_1") (pintype "passive"))
    )
    (net (code "249") (name "Net-(MOD1-WL_UART_DBG)") (class "Default")
      (node (ref "MOD1") (pin "42") (pinfunction "WL_UART_DBG_42") (pintype "bidirectional"))
      (node (ref "TP14") (pin "TP") (pinfunction "TP_TP") (pintype "input"))
    )
    (net (code "250") (name "Net-(OSC1-OUT)") (class "Default")
      (node (ref "OSC1") (pin "3") (pinfunction "OUT_3") (pintype "bidirectional"))
      (node (ref "R110") (pin "1") (pinfunction "1_1") (pintype "passive"))
    )
    (net (code "251") (name "Net-(OSC2-EN)") (class "Default")
      (node (ref "OSC2") (pin "1") (pinfunction "EN_1") (pintype "bidirectional"))
      (node (ref "R90") (pin "2") (pinfunction "2_2") (pintype "passive"))
    )
    (net (code "252") (name "Net-(PWR-PadK)") (class "Default")
      (node (ref "PWR") (pin "K") (pinfunction "K_K") (pintype "passive"))
      (node (ref "R55") (pin "2") (pinfunction "2_2") (pintype "passive"))
    )
    (net (code "253") (name "Net-(R88-Pad2)") (class "Default")
      (node (ref "R88") (pin "2") (pinfunction "2_2") (pintype "passive"))
      (node (ref "S2") (pin "1") (pinfunction "1_1") (pintype "bidirectional"))
      (node (ref "S2") (pin "2") (pinfunction "2_2") (pintype "bidirectional"))
    )
    (net (code "254") (name "Net-(R92-Pad1)") (class "Default")
      (node (ref "R92") (pin "1") (pinfunction "1_1") (pintype "passive"))
      (node (ref "USR3") (pin "A") (pinfunction "A_A") (pintype "passive"))
    )
    (net (code "255") (name "Net-(R96-Pad1)") (class "Default")
      (node (ref "R96") (pin "1") (pinfunction "1_1") (pintype "passive"))
      (node (ref "USR2") (pin "A") (pinfunction "A_A") (pintype "passive"))
    )
    (net (code "256") (name "Net-(R100-Pad1)") (class "Default")
      (node (ref "R100") (pin "1") (pinfunction "1_1") (pintype "passive"))
      (node (ref "USR1") (pin "A") (pinfunction "A_A") (pintype "passive"))
    )
    (net (code "257") (name "Net-(R104-Pad1)") (class "Default")
      (node (ref "R104") (pin "1") (pinfunction "1_1") (pintype "passive"))
      (node (ref "USR0") (pin "A") (pinfunction "A_A") (pintype "passive"))
    )
    (net (code "258") (name "Net-(R125-Pad1)") (class "Default")
      (node (ref "R125") (pin "1") (pinfunction "1_1") (pintype "passive"))
      (node (ref "WL") (pin "A") (pinfunction "A_A") (pintype "passive"))
    )
    (net (code "259") (name "Net-(T3-PadD)") (class "Default")
      (node (ref "T3") (pin "D") (pinfunction "D_D") (pintype "bidirectional"))
      (node (ref "WL") (pin "K") (pinfunction "K_K") (pintype "passive"))
    )
    (net (code "260") (name "SYS_5V") (class "Default")
      (node (ref "C62") (pin "+") (pinfunction "+_+") (pintype "passive"))
      (node (ref "D2") (pin "A") (pinfunction "A_A") (pintype "bidirectional"))
      (node (ref "F1") (pin "2") (pinfunction "2_2") (pintype "passive"))
      (node (ref "IC1") (pin "W4") (pinfunction "SYS_5V_1_W4") (pintype "bidirectional"))
      (node (ref "IC1") (pin "Y4") (pinfunction "SYS_5V_2_Y4") (pintype "bidirectional"))
      (node (ref "IC12") (pin "2") (pinfunction "IN1_2") (pintype "bidirectional"))
      (node (ref "IC12") (pin "3") (pinfunction "IN2_3") (pintype "bidirectional"))
      (node (ref "P9") (pin "7") (pinfunction "7_7") (pintype "passive"))
      (node (ref "P9") (pin "8") (pinfunction "8_8") (pintype "passive"))
    )
    (net (code "261") (name "USB_DC") (class "Default")
      (node (ref "C59") (pin "1") (pinfunction "1_1") (pintype "passive"))
      (node (ref "D4") (pin "A") (pinfunction "A_A") (pintype "bidirectional"))
      (node (ref "IC1") (pin "Y8") (pinfunction "VIN_USB_0_Y8") (pintype "bidirectional"))
      (node (ref "IC1") (pin "Y9") (pinfunction "VIN_USB_1_Y9") (pintype "bidirectional"))
      (node (ref "IC14") (pin "6") (pinfunction "VBUS_6") (pintype "bidirectional"))
      (node (ref "R26") (pin "2") (pinfunction "2_2") (pintype "passive"))
      (node (ref "X4") (pin "VBUS") (pinfunction "VBUS_VBUS") (pintype "input"))
    )
    (net (code "262") (name "VDDS_DDR") (class "Default")
      (node (ref "IC1") (pin "H5") (pinfunction "VDDS_DDR4_H5") (pintype "bidirectional"))
    )
    (net (code "263") (name "VDDS_PLL") (class "Default")
      (node (ref "IC1") (pin "E7") (pinfunction "VDD_PLL1_E7") (pintype "bidirectional"))
    )
    (net (code "264") (name "VDD_1V8") (class "Default")
      (node (ref "FB2") (pin "1") (pinfunction "P$1_1") (pintype "bidirectional"))
      (node (ref "IC1") (pin "D10") (pinfunction "VDD_1V84_D10") (pintype "bidirectional"))
      (node (ref "IC1") (pin "E9") (pinfunction "VDD_1V83_E9") (pintype "bidirectional"))
      (node (ref "IC1") (pin "N16") (pinfunction "VDD_1V8_0_N16") (pintype "bidirectional"))
      (node (ref "IC1") (pin "R16") (pinfunction "VDD_1V8_1_R16") (pintype "bidirectional"))
      (node (ref "IC2") (pin "5") (pinfunction "VCC_5") (pintype "bidirectional"))
      (node (ref "IC5") (pin "3") (pinfunction "A_3") (pintype "passive"))
      (node (ref "IC6") (pin "3") (pinfunction "A_3") (pintype "passive"))
      (node (ref "R47") (pin "2") (pinfunction "2_2") (pintype "passive"))
      (node (ref "R51") (pin "2") (pinfunction "2_2") (pintype "passive"))
      (node (ref "T1") (pin "C") (pinfunction "C_C") (pintype "passive"))
      (node (ref "T2") (pin "C") (pinfunction "C_C") (pintype "passive"))
    )
    (net (code "265") (name "VDD_3V3A") (class "Default")
      (node (ref "IC1") (pin "N5") (pinfunction "VDD_3V3A18_N5") (pintype "bidirectional"))
      (node (ref "IC1") (pin "P5") (pinfunction "VDD_3V3A17_P5") (pintype "bidirectional"))
      (node (ref "IC1") (pin "P6") (pinfunction "VDD_3V3A16_P6") (pintype "bidirectional"))
      (node (ref "IC1") (pin "P7") (pinfunction "VDD_3V3A15_P7") (pintype "bidirectional"))
      (node (ref "R44") (pin "1") (pinfunction "1_1") (pintype "passive"))
      (node (ref "R46") (pin "1") (pinfunction "1_1") (pintype "passive"))
      (node (ref "T1") (pin "E") (pinfunction "E_E") (pintype "passive"))
    )
    (net (code "266") (name "VDD_3V3AUX") (class "Default")
      (node (ref "IC1") (pin "Y11") (pinfunction "VDD_3V3AUX_Y11") (pintype "bidirectional"))
      (node (ref "PWR") (pin "A") (pinfunction "A_A") (pintype "passive"))
    )
    (net (code "267") (name "VDD_3V3B") (class "Default")
      (node (ref "C1") (pin "1") (pinfunction "1_1") (pintype "passive"))
      (node (ref "C12") (pin "1") (pinfunction "1_1") (pintype "passive"))
      (node (ref "C13") (pin "1") (pinfunction "1_1") (pintype "passive"))
      (node (ref "C14") (pin "1") (pinfunction "1_1") (pintype "passive"))
      (node (ref "C15") (pin "1") (pinfunction "1_1") (pintype "passive"))
      (node (ref "C17") (pin "1") (pinfunction "1_1") (pintype "passive"))
      (node (ref "C18") (pin "1") (pinfunction "1_1") (pintype "passive"))
      (node (ref "C2") (pin "1") (pinfunction "1_1") (pintype "passive"))
      (node (ref "C22") (pin "1") (pinfunction "1_1") (pintype "passive"))
      (node (ref "C47") (pin "1") (pinfunction "1_1") (pintype "passive"))
      (node (ref "C48") (pin "1") (pinfunction "1_1") (pintype "passive"))
      (node (ref "C49") (pin "1") (pinfunction "1_1") (pintype "passive"))
      (node (ref "C9") (pin "1") (pinfunction "1_1") (pintype "passive"))
      (node (ref "IC1") (pin "U20") (pinfunction "VDD_3V3B_0_U20") (pintype "bidirectional"))
      (node (ref "IC1") (pin "V20") (pinfunction "VDD_3V3B_1_V20") (pintype "bidirectional"))
      (node (ref "IC13") (pin "6") (pinfunction "CLR#_6") (pintype "bidirectional"))
      (node (ref "IC13") (pin "7") (pinfunction "PRE#_7") (pintype "bidirectional"))
      (node (ref "IC13") (pin "8") (pinfunction "VCC_8") (pintype "bidirectional"))
      (node (ref "IC17") (pin "7") (pinfunction "2OE_7") (pintype "bidirectional"))
      (node (ref "IC17") (pin "8") (pinfunction "VCC_8") (pintype "bidirectional"))
      (node (ref "IC22") (pin "C6") (pinfunction "VCCQ1_C6") (pintype "bidirectional"))
      (node (ref "IC22") (pin "E6") (pinfunction "VCC1_E6") (pintype "bidirectional"))
      (node (ref "IC22") (pin "F5") (pinfunction "VCC2_F5") (pintype "bidirectional"))
      (node (ref "IC22") (pin "J10") (pinfunction "VCC3_J10") (pintype "bidirectional"))
      (node (ref "IC22") (pin "K9") (pinfunction "VCC4_K9") (pintype "bidirectional"))
      (node (ref "IC22") (pin "M4") (pinfunction "VCCQ2_M4") (pintype "bidirectional"))
      (node (ref "IC22") (pin "N4") (pinfunction "VCCQ3_N4") (pintype "bidirectional"))
      (node (ref "IC22") (pin "P3") (pinfunction "VCCQ4_P3") (pintype "bidirectional"))
      (node (ref "IC22") (pin "P5") (pinfunction "VCCQ5_P5") (pintype "bidirectional"))
      (node (ref "IC3") (pin "5") (pinfunction "VCC_5") (pintype "bidirectional"))
      (node (ref "IC4") (pin "4") (pinfunction "VCC_4") (pintype "bidirectional"))
      (node (ref "OSC1") (pin "4") (pinfunction "VCC_4") (pintype "bidirectional"))
      (node (ref "P2") (pin "5") (pinfunction "TVDD_5") (pintype "bidirectional"))
      (node (ref "P9") (pin "3") (pinfunction "3_3") (pintype "passive"))
      (node (ref "P9") (pin "4") (pinfunction "4_4") (pintype "passive"))
      (node (ref "R1") (pin "2") (pinfunction "2_2") (pintype "passive"))
      (node (ref "R12") (pin "2") (pinfunction "2_2") (pintype "passive"))
      (node (ref "R120") (pin "1") (pinfunction "1_1") (pintype "passive"))
      (node (ref "R121") (pin "1") (pinfunction "1_1") (pintype "passive"))
      (node (ref "R122") (pin "1") (pinfunction "1_1") (pintype "passive"))
      (node (ref "R13") (pin "2") (pinfunction "2_2") (pintype "passive"))
      (node (ref "R16") (pin "2") (pinfunction "2_2") (pintype "passive"))
      (node (ref "R18") (pin "2") (pinfunction "2_2") (pintype "passive"))
      (node (ref "R2") (pin "2") (pinfunction "2_2") (pintype "passive"))
      (node (ref "R20") (pin "2") (pinfunction "2_2") (pintype "passive"))
      (node (ref "R21") (pin "1") (pinfunction "1_1") (pintype "passive"))
      (node (ref "R23") (pin "2") (pinfunction "2_2") (pintype "passive"))
      (node (ref "R25") (pin "2") (pinfunction "2_2") (pintype "passive"))
      (node (ref "R28") (pin "2") (pinfunction "2_2") (pintype "passive"))
      (node (ref "R3") (pin "2") (pinfunction "2_2") (pintype "passive"))
      (node (ref "R30") (pin "2") (pinfunction "2_2") (pintype "passive"))
      (node (ref "R31") (pin "2") (pinfunction "2_2") (pintype "passive"))
      (node (ref "R32") (pin "1") (pinfunction "1_1") (pintype "passive"))
      (node (ref "R33") (pin "2") (pinfunction "2_2") (pintype "passive"))
      (node (ref "R4") (pin "2") (pinfunction "2_2") (pintype "passive"))
      (node (ref "R40") (pin "1") (pinfunction "1_1") (pintype "passive"))
      (node (ref "R41") (pin "1") (pinfunction "1_1") (pintype "passive"))
      (node (ref "R42") (pin "1") (pinfunction "1_1") (pintype "passive"))
      (node (ref "R43") (pin "1") (pinfunction "1_1") (pintype "passive"))
      (node (ref "R48") (pin "1") (pinfunction "1_1") (pintype "passive"))
      (node (ref "R5") (pin "2") (pinfunction "2_2") (pintype "passive"))
      (node (ref "R50") (pin "1") (pinfunction "1_1") (pintype "passive"))
      (node (ref "R53") (pin "1") (pinfunction "1_1") (pintype "passive"))
      (node (ref "R58") (pin "2") (pinfunction "2_2") (pintype "passive"))
      (node (ref "R6") (pin "2") (pinfunction "2_2") (pintype "passive"))
      (node (ref "R7") (pin "2") (pinfunction "2_2") (pintype "passive"))
      (node (ref "R76") (pin "2") (pinfunction "2_2") (pintype "passive"))
      (node (ref "R78") (pin "2") (pinfunction "2_2") (pintype "passive"))
      (node (ref "R80") (pin "2") (pinfunction "2_2") (pintype "passive"))
      (node (ref "R82") (pin "2") (pinfunction "2_2") (pintype "passive"))
      (node (ref "R89") (pin "1") (pinfunction "1_1") (pintype "passive"))
      (node (ref "T2") (pin "E") (pinfunction "E_E") (pintype "passive"))
      (node (ref "X2") (pin "4") (pinfunction "VDD_4") (pintype "bidirectional"))
    )
    (net (code "268") (name "VDD_5V") (class "Default")
      (node (ref "D3") (pin "A") (pinfunction "A_A") (pintype "bidirectional"))
      (node (ref "IC1") (pin "Y5") (pinfunction "VIN_5V_0_Y5") (pintype "bidirectional"))
      (node (ref "IC1") (pin "Y6") (pinfunction "VIN_5V_1_Y6") (pintype "bidirectional"))
      (node (ref "P9") (pin "5") (pinfunction "5_5") (pintype "passive"))
      (node (ref "P9") (pin "6") (pinfunction "6_6") (pintype "passive"))
      (node (ref "X12") (pin "IN") (pinfunction "IN_IN") (pintype "bidirectional"))
    )
    (net (code "269") (name "VDD_ADC") (class "Default")
      (node (ref "IC1") (pin "A4") (pinfunction "VDD_ADC_1_A4") (pintype "bidirectional"))
      (node (ref "IC1") (pin "A5") (pinfunction "VDD_ADC_0_A5") (pintype "bidirectional"))
      (node (ref "IC1") (pin "B9") (pinfunction "VREFP_ADC_B9") (pintype "bidirectional"))
      (node (ref "IC1") (pin "D8") (pinfunction "VDDA_ADC_D8") (pintype "bidirectional"))
      (node (ref "P9") (pin "32") (pinfunction "32_32") (pintype "passive"))
    )
    (net (code "270") (name "VDD_CORE") (class "Default")
      (node (ref "IC1") (pin "F6") (pinfunction "VDD_CORE1_F6") (pintype "bidirectional"))
    )
    (net (code "271") (name "VDD_MPU") (class "Default")
      (node (ref "IC1") (pin "F10") (pinfunction "VDD_MPU0_F10") (pintype "bidirectional"))
    )
    (net (code "272") (name "VDD_RTC") (class "Default")
      (node (ref "IC1") (pin "N6") (pinfunction "VDD_RTC4_N6") (pintype "bidirectional"))
    )
    (net (code "273") (name "unconnected-(D8-A1-Pad1)") (class "Default")
      (node (ref "D8") (pin "1") (pinfunction "A1_1") (pintype "passive"))
    )
    (net (code "274") (name "unconnected-(FUD1-PadP$1)") (class "Default")
      (node (ref "FUD1") (pin "P$1") (pinfunction "P$1_P$1") (pintype "no_connect"))
    )
    (net (code "275") (name "unconnected-(FUD2-PadP$1)") (class "Default")
      (node (ref "FUD2") (pin "P$1") (pinfunction "P$1_P$1") (pintype "no_connect"))
    )
    (net (code "276") (name "unconnected-(FUD3-PadP$1)") (class "Default")
      (node (ref "FUD3") (pin "P$1") (pinfunction "P$1_P$1") (pintype "no_connect"))
    )
    (net (code "277") (name "unconnected-(FUD4-PadP$1)") (class "Default")
      (node (ref "FUD4") (pin "P$1") (pinfunction "P$1_P$1") (pintype "no_connect"))
    )
    (net (code "278") (name "unconnected-(FUD5-PadP$1)") (class "Default")
      (node (ref "FUD5") (pin "P$1") (pinfunction "P$1_P$1") (pintype "no_connect"))
    )
    (net (code "279") (name "unconnected-(FUD6-PadP$1)") (class "Default")
      (node (ref "FUD6") (pin "P$1") (pinfunction "P$1_P$1") (pintype "no_connect"))
    )
    (net (code "280") (name "unconnected-(IC1B-UART0_CTSN-PadE18)") (class "Default")
      (node (ref "IC1") (pin "E18") (pinfunction "UART0_CTSN_E18") (pintype "bidirectional"))
    )
    (net (code "281") (name "unconnected-(IC1B-USB0_CE-PadM15)") (class "Default")
      (node (ref "IC1") (pin "M15") (pinfunction "USB0_CE_M15") (pintype "bidirectional"))
    )
    (net (code "282") (name "unconnected-(IC1B-USB0_DRVVBUS-PadF16)") (class "Default")
      (node (ref "IC1") (pin "F16") (pinfunction "USB0_DRVVBUS_F16") (pintype "bidirectional"))
    )
    (net (code "283") (name "unconnected-(IC1B-USB1_CE-PadP18)") (class "Default")
      (node (ref "IC1") (pin "P18") (pinfunction "USB1_CE_P18") (pintype "bidirectional"))
    )
    (net (code "284") (name "unconnected-(IC1C-L1_IN-PadY14)") (class "Default")
      (node (ref "IC1") (pin "Y14") (pinfunction "L1_IN_Y14") (pintype "bidirectional"))
    )
    (net (code "285") (name "unconnected-(IC1C-L2_IN-PadY17)") (class "Default")
      (node (ref "IC1") (pin "Y17") (pinfunction "L2_IN_Y17") (pintype "bidirectional"))
    )
    (net (code "286") (name "unconnected-(IC1C-L3_IN-PadY20)") (class "Default")
      (node (ref "IC1") (pin "Y20") (pinfunction "L3_IN_Y20") (pintype "bidirectional"))
    )
    (net (code "287") (name "unconnected-(IC1C-VDDS_DDR-PadY13)") (class "Default")
      (node (ref "IC1") (pin "Y13") (pinfunction "VDDS_DDR_Y13") (pintype "bidirectional"))
    )
    (net (code "288") (name "unconnected-(IC1C-VDD_CORE-PadY19)") (class "Default")
      (node (ref "IC1") (pin "Y19") (pinfunction "VDD_CORE_Y19") (pintype "bidirectional"))
    )
    (net (code "289") (name "unconnected-(IC1C-VDD_MPU-PadY16)") (class "Default")
      (node (ref "IC1") (pin "Y16") (pinfunction "VDD_MPU_Y16") (pintype "bidirectional"))
    )
    (net (code "290") (name "unconnected-(IC1D-NC1-PadB1)") (class "Default")
      (node (ref "IC1") (pin "B1") (pinfunction "NC1_B1") (pintype "bidirectional"))
    )
    (net (code "291") (name "unconnected-(IC1D-NC2-PadB2)") (class "Default")
      (node (ref "IC1") (pin "B2") (pinfunction "NC2_B2") (pintype "bidirectional"))
    )
    (net (code "292") (name "unconnected-(IC1D-NC3-PadB3)") (class "Default")
      (node (ref "IC1") (pin "B3") (pinfunction "NC3_B3") (pintype "bidirectional"))
    )
    (net (code "293") (name "unconnected-(IC1D-NC4-PadC1)") (class "Default")
      (node (ref "IC1") (pin "C1") (pinfunction "NC4_C1") (pintype "bidirectional"))
    )
    (net (code "294") (name "unconnected-(IC1D-NC5-PadC2)") (class "Default")
      (node (ref "IC1") (pin "C2") (pinfunction "NC5_C2") (pintype "bidirectional"))
    )
    (net (code "295") (name "unconnected-(IC1D-NC6-PadC3)") (class "Default")
      (node (ref "IC1") (pin "C3") (pinfunction "NC6_C3") (pintype "bidirectional"))
    )
    (net (code "296") (name "unconnected-(IC1D-NC12-PadC4)") (class "Default")
      (node (ref "IC1") (pin "C4") (pinfunction "NC12_C4") (pintype "bidirectional"))
    )
    (net (code "297") (name "unconnected-(IC1D-NC20-PadD1)") (class "Default")
      (node (ref "IC1") (pin "D1") (pinfunction "NC20_D1") (pintype "bidirectional"))
    )
    (net (code "298") (name "unconnected-(IC1D-NC21-PadD2)") (class "Default")
      (node (ref "IC1") (pin "D2") (pinfunction "NC21_D2") (pintype "bidirectional"))
    )
    (net (code "299") (name "unconnected-(IC1D-NC22-PadD3)") (class "Default")
      (node (ref "IC1") (pin "D3") (pinfunction "NC22_D3") (pintype "bidirectional"))
    )
    (net (code "300") (name "unconnected-(IC1D-NC23-PadD4)") (class "Default")
      (node (ref "IC1") (pin "D4") (pinfunction "NC23_D4") (pintype "bidirectional"))
    )
    (net (code "301") (name "unconnected-(IC1D-NC24-PadD5)") (class "Default")
      (node (ref "IC1") (pin "D5") (pinfunction "NC24_D5") (pintype "bidirectional"))
    )
    (net (code "302") (name "unconnected-(IC1D-NC31-PadE1)") (class "Default")
      (node (ref "IC1") (pin "E1") (pinfunction "NC31_E1") (pintype "bidirectional"))
    )
    (net (code "303") (name "unconnected-(IC1D-NC32-PadE2)") (class "Default")
      (node (ref "IC1") (pin "E2") (pinfunction "NC32_E2") (pintype "bidirectional"))
    )
    (net (code "304") (name "unconnected-(IC1D-NC33-PadE3)") (class "Default")
      (node (ref "IC1") (pin "E3") (pinfunction "NC33_E3") (pintype "bidirectional"))
    )
    (net (code "305") (name "unconnected-(IC1D-NC34-PadE4)") (class "Default")
      (node (ref "IC1") (pin "E4") (pinfunction "NC34_E4") (pintype "bidirectional"))
    )
    (net (code "306") (name "unconnected-(IC1D-NC45-PadF1)") (class "Default")
      (node (ref "IC1") (pin "F1") (pinfunction "NC45_F1") (pintype "bidirectional"))
    )
    (net (code "307") (name "unconnected-(IC1D-NC46-PadF2)") (class "Default")
      (node (ref "IC1") (pin "F2") (pinfunction "NC46_F2") (pintype "bidirectional"))
    )
    (net (code "308") (name "unconnected-(IC1D-NC47-PadF3)") (class "Default")
      (node (ref "IC1") (pin "F3") (pinfunction "NC47_F3") (pintype "bidirectional"))
    )
    (net (code "309") (name "unconnected-(IC1D-NC48-PadF4)") (class "Default")
      (node (ref "IC1") (pin "F4") (pinfunction "NC48_F4") (pintype "bidirectional"))
    )
    (net (code "310") (name "unconnected-(IC1D-NC58-PadG1)") (class "Default")
      (node (ref "IC1") (pin "G1") (pinfunction "NC58_G1") (pintype "bidirectional"))
    )
    (net (code "311") (name "unconnected-(IC1D-NC59-PadG2)") (class "Default")
      (node (ref "IC1") (pin "G2") (pinfunction "NC59_G2") (pintype "bidirectional"))
    )
    (net (code "312") (name "unconnected-(IC1D-NC60-PadG3)") (class "Default")
      (node (ref "IC1") (pin "G3") (pinfunction "NC60_G3") (pintype "bidirectional"))
    )
    (net (code "313") (name "unconnected-(IC1D-NC61-PadG4)") (class "Default")
      (node (ref "IC1") (pin "G4") (pinfunction "NC61_G4") (pintype "bidirectional"))
    )
    (net (code "314") (name "unconnected-(IC1D-NC68-PadH1)") (class "Default")
      (node (ref "IC1") (pin "H1") (pinfunction "NC68_H1") (pintype "bidirectional"))
    )
    (net (code "315") (name "unconnected-(IC1D-NC69-PadH2)") (class "Default")
      (node (ref "IC1") (pin "H2") (pinfunction "NC69_H2") (pintype "bidirectional"))
    )
    (net (code "316") (name "unconnected-(IC1D-NC70-PadH3)") (class "Default")
      (node (ref "IC1") (pin "H3") (pinfunction "NC70_H3") (pintype "bidirectional"))
    )
    (net (code "317") (name "unconnected-(IC1D-NC71-PadH4)") (class "Default")
      (node (ref "IC1") (pin "H4") (pinfunction "NC71_H4") (pintype "bidirectional"))
    )
    (net (code "318") (name "unconnected-(IC1D-NC76-PadJ1)") (class "Default")
      (node (ref "IC1") (pin "J1") (pinfunction "NC76_J1") (pintype "bidirectional"))
    )
    (net (code "319") (name "unconnected-(IC1D-NC77-PadJ2)") (class "Default")
      (node (ref "IC1") (pin "J2") (pinfunction "NC77_J2") (pintype "bidirectional"))
    )
    (net (code "320") (name "unconnected-(IC1D-NC78-PadJ3)") (class "Default")
      (node (ref "IC1") (pin "J3") (pinfunction "NC78_J3") (pintype "bidirectional"))
    )
    (net (code "321") (name "unconnected-(IC1D-NC79-PadJ4)") (class "Default")
      (node (ref "IC1") (pin "J4") (pinfunction "NC79_J4") (pintype "bidirectional"))
    )
    (net (code "322") (name "unconnected-(IC1D-NC84-PadK1)") (class "Default")
      (node (ref "IC1") (pin "K1") (pinfunction "NC84_K1") (pintype "bidirectional"))
    )
    (net (code "323") (name "unconnected-(IC1D-NC85-PadK2)") (class "Default")
      (node (ref "IC1") (pin "K2") (pinfunction "NC85_K2") (pintype "bidirectional"))
    )
    (net (code "324") (name "unconnected-(IC1D-NC86-PadK3)") (class "Default")
      (node (ref "IC1") (pin "K3") (pinfunction "NC86_K3") (pintype "bidirectional"))
    )
    (net (code "325") (name "unconnected-(IC1D-NC87-PadK4)") (class "Default")
      (node (ref "IC1") (pin "K4") (pinfunction "NC87_K4") (pintype "bidirectional"))
    )
    (net (code "326") (name "unconnected-(IC1D-NC94-PadL1)") (class "Default")
      (node (ref "IC1") (pin "L1") (pinfunction "NC94_L1") (pintype "bidirectional"))
    )
    (net (code "327") (name "unconnected-(IC1D-NC95-PadL2)") (class "Default")
      (node (ref "IC1") (pin "L2") (pinfunction "NC95_L2") (pintype "bidirectional"))
    )
    (net (code "328") (name "unconnected-(IC1D-NC96-PadL3)") (class "Default")
      (node (ref "IC1") (pin "L3") (pinfunction "NC96_L3") (pintype "bidirectional"))
    )
    (net (code "329") (name "unconnected-(IC1D-NC97-PadL4)") (class "Default")
      (node (ref "IC1") (pin "L4") (pinfunction "NC97_L4") (pintype "bidirectional"))
    )
    (net (code "330") (name "unconnected-(IC1D-NC104-PadM1)") (class "Default")
      (node (ref "IC1") (pin "M1") (pinfunction "NC104_M1") (pintype "bidirectional"))
    )
    (net (code "331") (name "unconnected-(IC1D-NC105-PadM2)") (class "Default")
      (node (ref "IC1") (pin "M2") (pinfunction "NC105_M2") (pintype "bidirectional"))
    )
    (net (code "332") (name "unconnected-(IC1D-NC106-PadM3)") (class "Default")
      (node (ref "IC1") (pin "M3") (pinfunction "NC106_M3") (pintype "bidirectional"))
    )
    (net (code "333") (name "unconnected-(IC1D-NC107-PadM4)") (class "Default")
      (node (ref "IC1") (pin "M4") (pinfunction "NC107_M4") (pintype "bidirectional"))
    )
    (net (code "334") (name "unconnected-(IC1D-NC111-PadN1)") (class "Default")
      (node (ref "IC1") (pin "N1") (pinfunction "NC111_N1") (pintype "bidirectional"))
    )
    (net (code "335") (name "unconnected-(IC1D-NC112-PadN2)") (class "Default")
      (node (ref "IC1") (pin "N2") (pinfunction "NC112_N2") (pintype "bidirectional"))
    )
    (net (code "336") (name "unconnected-(IC1D-NC113-PadN3)") (class "Default")
      (node (ref "IC1") (pin "N3") (pinfunction "NC113_N3") (pintype "bidirectional"))
    )
    (net (code "337") (name "unconnected-(IC1D-NC114-PadN4)") (class "Default")
      (node (ref "IC1") (pin "N4") (pinfunction "NC114_N4") (pintype "bidirectional"))
    )
    (net (code "338") (name "unconnected-(IC1D-NC121-PadP1)") (class "Default")
      (node (ref "IC1") (pin "P1") (pinfunction "NC121_P1") (pintype "bidirectional"))
    )
    (net (code "339") (name "unconnected-(IC1D-NC122-PadP2)") (class "Default")
      (node (ref "IC1") (pin "P2") (pinfunction "NC122_P2") (pintype "bidirectional"))
    )
    (net (code "340") (name "unconnected-(IC1D-NC123-PadP3)") (class "Default")
      (node (ref "IC1") (pin "P3") (pinfunction "NC123_P3") (pintype "bidirectional"))
    )
    (net (code "341") (name "unconnected-(IC1D-NC124-PadP4)") (class "Default")
      (node (ref "IC1") (pin "P4") (pinfunction "NC124_P4") (pintype "bidirectional"))
    )
    (net (code "342") (name "unconnected-(IC1D-NC136-PadU11)") (class "Default")
      (node (ref "IC1") (pin "U11") (pinfunction "NC136_U11") (pintype "bidirectional"))
    )
    (net (code "343") (name "unconnected-(IC1D-NC137-PadV10)") (class "Default")
      (node (ref "IC1") (pin "V10") (pinfunction "NC137_V10") (pintype "bidirectional"))
    )
    (net (code "344") (name "unconnected-(IC1D-NC138-PadV11)") (class "Default")
      (node (ref "IC1") (pin "V11") (pinfunction "NC138_V11") (pintype "bidirectional"))
    )
    (net (code "345") (name "unconnected-(IC1E-CAP_VBB_MPU-PadC10)") (class "Default")
      (node (ref "IC1") (pin "C10") (pinfunction "CAP_VBB_MPU_C10") (pintype "bidirectional"))
    )
    (net (code "346") (name "unconnected-(IC1E-CAP_VDD_RTC-PadD6)") (class "Default")
      (node (ref "IC1") (pin "D6") (pinfunction "CAP_VDD_RTC_D6") (pintype "bidirectional"))
    )
    (net (code "347") (name "unconnected-(IC1E-CAP_VDD_SRAM_COR-PadD9)") (class "Default")
      (node (ref "IC1") (pin "D9") (pinfunction "CAP_VDD_SRAM_COR_D9") (pintype "bidirectional"))
    )
    (net (code "348") (name "unconnected-(IC1E-CAP_VDD_SRAM_MPU-PadD11)") (class "Default")
      (node (ref "IC1") (pin "D11") (pinfunction "CAP_VDD_SRAM_MPU_D11") (pintype "bidirectional"))
    )
    (net (code "349") (name "unconnected-(IC1E-TESTOUT-PadA3)") (class "Default")
      (node (ref "IC1") (pin "A3") (pinfunction "TESTOUT_A3") (pintype "bidirectional"))
    )
    (net (code "350") (name "unconnected-(IC1E-VDDS_DDR1-PadE5)") (class "Default")
      (node (ref "IC1") (pin "E5") (pinfunction "VDDS_DDR1_E5") (pintype "bidirectional"))
    )
    (net (code "351") (name "unconnected-(IC1E-VDDS_DDR2-PadF5)") (class "Default")
      (node (ref "IC1") (pin "F5") (pinfunction "VDDS_DDR2_F5") (pintype "bidirectional"))
    )
    (net (code "352") (name "unconnected-(IC1E-VDDS_DDR3-PadG5)") (class "Default")
      (node (ref "IC1") (pin "G5") (pinfunction "VDDS_DDR3_G5") (pintype "bidirectional"))
    )
    (net (code "353") (name "unconnected-(IC1E-VDDS_DDR5-PadJ5)") (class "Default")
      (node (ref "IC1") (pin "J5") (pinfunction "VDDS_DDR5_J5") (pintype "bidirectional"))
    )
    (net (code "354") (name "unconnected-(IC1E-VDDS_DDR6-PadK5)") (class "Default")
      (node (ref "IC1") (pin "K5") (pinfunction "VDDS_DDR6_K5") (pintype "bidirectional"))
    )
    (net (code "355") (name "unconnected-(IC1E-VDDS_DDR7-PadL5)") (class "Default")
      (node (ref "IC1") (pin "L5") (pinfunction "VDDS_DDR7_L5") (pintype "bidirectional"))
    )
    (net (code "356") (name "unconnected-(IC1E-VDD_3V3A1-PadF14)") (class "Default")
      (node (ref "IC1") (pin "F14") (pinfunction "VDD_3V3A1_F14") (pintype "bidirectional"))
    )
    (net (code "357") (name "unconnected-(IC1E-VDD_3V3A2-PadG14)") (class "Default")
      (node (ref "IC1") (pin "G14") (pinfunction "VDD_3V3A2_G14") (pintype "bidirectional"))
    )
    (net (code "358") (name "unconnected-(IC1E-VDD_3V3A3-PadH14)") (class "Default")
      (node (ref "IC1") (pin "H14") (pinfunction "VDD_3V3A3_H14") (pintype "bidirectional"))
    )
    (net (code "359") (name "unconnected-(IC1E-VDD_3V3A4-PadJ14)") (class "Default")
      (node (ref "IC1") (pin "J14") (pinfunction "VDD_3V3A4_J14") (pintype "bidirectional"))
    )
    (net (code "360") (name "unconnected-(IC1E-VDD_3V3A5-PadK14)") (class "Default")
      (node (ref "IC1") (pin "K14") (pinfunction "VDD_3V3A5_K14") (pintype "bidirectional"))
    )
    (net (code "361") (name "unconnected-(IC1E-VDD_3V3A6-PadL14)") (class "Default")
      (node (ref "IC1") (pin "L14") (pinfunction "VDD_3V3A6_L14") (pintype "bidirectional"))
    )
    (net (code "362") (name "unconnected-(IC1E-VDD_3V3A7-PadN15)") (class "Default")
      (node (ref "IC1") (pin "N15") (pinfunction "VDD_3V3A7_N15") (pintype "bidirectional"))
    )
    (net (code "363") (name "unconnected-(IC1E-VDD_3V3A8-PadR15)") (class "Default")
      (node (ref "IC1") (pin "R15") (pinfunction "VDD_3V3A8_R15") (pintype "bidirectional"))
    )
    (net (code "364") (name "unconnected-(IC1E-VDD_3V3A9-PadP13)") (class "Default")
      (node (ref "IC1") (pin "P13") (pinfunction "VDD_3V3A9_P13") (pintype "bidirectional"))
    )
    (net (code "365") (name "unconnected-(IC1E-VDD_3V3A10-PadP12)") (class "Default")
      (node (ref "IC1") (pin "P12") (pinfunction "VDD_3V3A10_P12") (pintype "bidirectional"))
    )
    (net (code "366") (name "unconnected-(IC1E-VDD_3V3A11-PadP11)") (class "Default")
      (node (ref "IC1") (pin "P11") (pinfunction "VDD_3V3A11_P11") (pintype "bidirectional"))
    )
    (net (code "367") (name "unconnected-(IC1E-VDD_3V3A12-PadP10)") (class "Default")
      (node (ref "IC1") (pin "P10") (pinfunction "VDD_3V3A12_P10") (pintype "bidirectional"))
    )
    (net (code "368") (name "unconnected-(IC1E-VDD_3V3A14-PadP8)") (class "Default")
      (node (ref "IC1") (pin "P8") (pinfunction "VDD_3V3A14_P8") (pintype "bidirectional"))
    )
    (net (code "369") (name "unconnected-(IC1E-VDD_3V3A19-PadE13)") (class "Default")
      (node (ref "IC1") (pin "E13") (pinfunction "VDD_3V3A19_E13") (pintype "bidirectional"))
    )
    (net (code "370") (name "unconnected-(IC1E-VDD_3V3A20-PadE12)") (class "Default")
      (node (ref "IC1") (pin "E12") (pinfunction "VDD_3V3A20_E12") (pintype "bidirectional"))
    )
    (net (code "371") (name "unconnected-(IC1E-VDD_3V3A21-PadE11)") (class "Default")
      (node (ref "IC1") (pin "E11") (pinfunction "VDD_3V3A21_E11") (pintype "bidirectional"))
    )
    (net (code "372") (name "unconnected-(IC1E-VDD_3V3A22-PadE10)") (class "Default")
      (node (ref "IC1") (pin "E10") (pinfunction "VDD_3V3A22_E10") (pintype "bidirectional"))
    )
    (net (code "373") (name "unconnected-(IC1E-VDD_CORE2-PadF7)") (class "Default")
      (node (ref "IC1") (pin "F7") (pinfunction "VDD_CORE2_F7") (pintype "bidirectional"))
    )
    (net (code "374") (name "unconnected-(IC1E-VDD_CORE3-PadG6)") (class "Default")
      (node (ref "IC1") (pin "G6") (pinfunction "VDD_CORE3_G6") (pintype "bidirectional"))
    )
    (net (code "375") (name "unconnected-(IC1E-VDD_CORE4-PadG7)") (class "Default")
      (node (ref "IC1") (pin "G7") (pinfunction "VDD_CORE4_G7") (pintype "bidirectional"))
    )
    (net (code "376") (name "unconnected-(IC1E-VDD_CORE5-PadG10)") (class "Default")
      (node (ref "IC1") (pin "G10") (pinfunction "VDD_CORE5_G10") (pintype "bidirectional"))
    )
    (net (code "377") (name "unconnected-(IC1E-VDD_CORE6-PadH11)") (class "Default")
      (node (ref "IC1") (pin "H11") (pinfunction "VDD_CORE6_H11") (pintype "bidirectional"))
    )
    (net (code "378") (name "unconnected-(IC1E-VDD_CORE7-PadJ12)") (class "Default")
      (node (ref "IC1") (pin "J12") (pinfunction "VDD_CORE7_J12") (pintype "bidirectional"))
    )
    (net (code "379") (name "unconnected-(IC1E-VDD_CORE8-PadK6)") (class "Default")
      (node (ref "IC1") (pin "K6") (pinfunction "VDD_CORE8_K6") (pintype "bidirectional"))
    )
    (net (code "380") (name "unconnected-(IC1E-VDD_CORE9-PadK8)") (class "Default")
      (node (ref "IC1") (pin "K8") (pinfunction "VDD_CORE9_K8") (pintype "bidirectional"))
    )
    (net (code "381") (name "unconnected-(IC1E-VDD_CORE10-PadK12)") (class "Default")
      (node (ref "IC1") (pin "K12") (pinfunction "VDD_CORE10_K12") (pintype "bidirectional"))
    )
    (net (code "382") (name "unconnected-(IC1E-VDD_CORE11-PadL6)") (class "Default")
      (node (ref "IC1") (pin "L6") (pinfunction "VDD_CORE11_L6") (pintype "bidirectional"))
    )
    (net (code "383") (name "unconnected-(IC1E-VDD_CORE12-PadL7)") (class "Default")
      (node (ref "IC1") (pin "L7") (pinfunction "VDD_CORE12_L7") (pintype "bidirectional"))
    )
    (net (code "384") (name "unconnected-(IC1E-VDD_CORE13-PadL8)") (class "Default")
      (node (ref "IC1") (pin "L8") (pinfunction "VDD_CORE13_L8") (pintype "bidirectional"))
    )
    (net (code "385") (name "unconnected-(IC1E-VDD_CORE14-PadL9)") (class "Default")
      (node (ref "IC1") (pin "L9") (pinfunction "VDD_CORE14_L9") (pintype "bidirectional"))
    )
    (net (code "386") (name "unconnected-(IC1E-VDD_CORE15-PadM11)") (class "Default")
      (node (ref "IC1") (pin "M11") (pinfunction "VDD_CORE15_M11") (pintype "bidirectional"))
    )
    (net (code "387") (name "unconnected-(IC1E-VDD_CORE16-PadM13)") (class "Default")
      (node (ref "IC1") (pin "M13") (pinfunction "VDD_CORE16_M13") (pintype "bidirectional"))
    )
    (net (code "388") (name "unconnected-(IC1E-VDD_CORE17-PadN8)") (class "Default")
      (node (ref "IC1") (pin "N8") (pinfunction "VDD_CORE17_N8") (pintype "bidirectional"))
    )
    (net (code "389") (name "unconnected-(IC1E-VDD_CORE18-PadN9)") (class "Default")
      (node (ref "IC1") (pin "N9") (pinfunction "VDD_CORE18_N9") (pintype "bidirectional"))
    )
    (net (code "390") (name "unconnected-(IC1E-VDD_CORE19-PadN12)") (class "Default")
      (node (ref "IC1") (pin "N12") (pinfunction "VDD_CORE19_N12") (pintype "bidirectional"))
    )
    (net (code "391") (name "unconnected-(IC1E-VDD_CORE20-PadN13)") (class "Default")
      (node (ref "IC1") (pin "N13") (pinfunction "VDD_CORE20_N13") (pintype "bidirectional"))
    )
    (net (code "392") (name "unconnected-(IC1E-VDD_MPU1-PadF11)") (class "Default")
      (node (ref "IC1") (pin "F11") (pinfunction "VDD_MPU1_F11") (pintype "bidirectional"))
    )
    (net (code "393") (name "unconnected-(IC1E-VDD_MPU2-PadF12)") (class "Default")
      (node (ref "IC1") (pin "F12") (pinfunction "VDD_MPU2_F12") (pintype "bidirectional"))
    )
    (net (code "394") (name "unconnected-(IC1E-VDD_MPU3-PadF13)") (class "Default")
      (node (ref "IC1") (pin "F13") (pinfunction "VDD_MPU3_F13") (pintype "bidirectional"))
    )
    (net (code "395") (name "unconnected-(IC1E-VDD_MPU4-PadG13)") (class "Default")
      (node (ref "IC1") (pin "G13") (pinfunction "VDD_MPU4_G13") (pintype "bidirectional"))
    )
    (net (code "396") (name "unconnected-(IC1E-VDD_MPU5-PadH13)") (class "Default")
      (node (ref "IC1") (pin "H13") (pinfunction "VDD_MPU5_H13") (pintype "bidirectional"))
    )
    (net (code "397") (name "unconnected-(IC1E-VDD_MPU6-PadJ13)") (class "Default")
      (node (ref "IC1") (pin "J13") (pinfunction "VDD_MPU6_J13") (pintype "bidirectional"))
    )
    (net (code "398") (name "unconnected-(IC1E-VDD_MPU_MON-PadA2)") (class "Default")
      (node (ref "IC1") (pin "A2") (pinfunction "VDD_MPU_MON_A2") (pintype "bidirectional"))
    )
    (net (code "399") (name "unconnected-(IC1E-VDD_PLL2-PadR10)") (class "Default")
      (node (ref "IC1") (pin "R10") (pinfunction "VDD_PLL2_R10") (pintype "bidirectional"))
    )
    (net (code "400") (name "unconnected-(IC1E-VDD_PLL3-PadR11)") (class "Default")
      (node (ref "IC1") (pin "R11") (pinfunction "VDD_PLL3_R11") (pintype "bidirectional"))
    )
    (net (code "401") (name "unconnected-(IC1E-VDD_PLL4-PadH15)") (class "Default")
      (node (ref "IC1") (pin "H15") (pinfunction "VDD_PLL4_H15") (pintype "bidirectional"))
    )
    (net (code "402") (name "unconnected-(IC1E-VDD_RTC1-PadD7)") (class "Default")
      (node (ref "IC1") (pin "D7") (pinfunction "VDD_RTC1_D7") (pintype "bidirectional"))
    )
    (net (code "403") (name "unconnected-(IC1E-VDD_RTC2-PadE6)") (class "Default")
      (node (ref "IC1") (pin "E6") (pinfunction "VDD_RTC2_E6") (pintype "bidirectional"))
    )
    (net (code "404") (name "unconnected-(IC1E-VDD_RTC3-PadF9)") (class "Default")
      (node (ref "IC1") (pin "F9") (pinfunction "VDD_RTC3_F9") (pintype "bidirectional"))
    )
    (net (code "405") (name "unconnected-(IC1E-VDD_RTC5-PadP14)") (class "Default")
      (node (ref "IC1") (pin "P14") (pinfunction "VDD_RTC5_P14") (pintype "bidirectional"))
    )
    (net (code "406") (name "unconnected-(IC1E-VDD_RTC6-PadK13)") (class "Default")
      (node (ref "IC1") (pin "K13") (pinfunction "VDD_RTC6_K13") (pintype "bidirectional"))
    )
    (net (code "407") (name "unconnected-(IC1E-VDD_RTC7-PadE14)") (class "Default")
      (node (ref "IC1") (pin "E14") (pinfunction "VDD_RTC7_E14") (pintype "bidirectional"))
    )
    (net (code "408") (name "unconnected-(IC1E-VDD_RTC8-PadP9)") (class "Default")
      (node (ref "IC1") (pin "P9") (pinfunction "VDD_RTC8_P9") (pintype "bidirectional"))
    )
    (net (code "409") (name "unconnected-(IC1E-VPP-PadM5)") (class "Default")
      (node (ref "IC1") (pin "M5") (pinfunction "VPP_M5") (pintype "bidirectional"))
    )
    (net (code "410") (name "unconnected-(IC7-NC1-Pad6)") (class "Default")
      (node (ref "IC7") (pin "6") (pinfunction "NC1_6") (pintype "bidirectional"))
    )
    (net (code "411") (name "unconnected-(IC7-NC2-Pad7)") (class "Default")
      (node (ref "IC7") (pin "7") (pinfunction "NC2_7") (pintype "bidirectional"))
    )
    (net (code "412") (name "unconnected-(IC7-NC3-Pad9)") (class "Default")
      (node (ref "IC7") (pin "9") (pinfunction "NC3_9") (pintype "bidirectional"))
    )
    (net (code "413") (name "unconnected-(IC7-NC4-Pad10)") (class "Default")
      (node (ref "IC7") (pin "10") (pinfunction "NC4_10") (pintype "bidirectional"))
    )
    (net (code "414") (name "unconnected-(IC8-NC1-Pad6)") (class "Default")
      (node (ref "IC8") (pin "6") (pinfunction "NC1_6") (pintype "bidirectional"))
    )
    (net (code "415") (name "unconnected-(IC8-NC2-Pad7)") (class "Default")
      (node (ref "IC8") (pin "7") (pinfunction "NC2_7") (pintype "bidirectional"))
    )
    (net (code "416") (name "unconnected-(IC8-NC3-Pad9)") (class "Default")
      (node (ref "IC8") (pin "9") (pinfunction "NC3_9") (pintype "bidirectional"))
    )
    (net (code "417") (name "unconnected-(IC8-NC4-Pad10)") (class "Default")
      (node (ref "IC8") (pin "10") (pinfunction "NC4_10") (pintype "bidirectional"))
    )
    (net (code "418") (name "unconnected-(IC9-AP2-Pad26)") (class "Default")
      (node (ref "IC9") (pin "26") (pinfunction "AP2_26") (pintype "bidirectional"))
    )
    (net (code "419") (name "unconnected-(IC9-AP4-Pad28)") (class "Default")
      (node (ref "IC9") (pin "28") (pinfunction "AP4_28") (pintype "bidirectional"))
    )
    (net (code "420") (name "unconnected-(IC10-A7-Pad8)") (class "Default")
      (node (ref "IC10") (pin "8") (pinfunction "A7_8") (pintype "bidirectional"))
    )
    (net (code "421") (name "unconnected-(IC10-A8-Pad9)") (class "Default")
      (node (ref "IC10") (pin "9") (pinfunction "A8_9") (pintype "bidirectional"))
    )
    (net (code "422") (name "unconnected-(IC10-B7-Pad13)") (class "Default")
      (node (ref "IC10") (pin "13") (pinfunction "B7_13") (pintype "bidirectional"))
    )
    (net (code "423") (name "unconnected-(IC10-B8-Pad12)") (class "Default")
      (node (ref "IC10") (pin "12") (pinfunction "B8_12") (pintype "bidirectional"))
    )
    (net (code "424") (name "unconnected-(IC14-NC-Pad5)") (class "Default")
      (node (ref "IC14") (pin "5") (pinfunction "NC_5") (pintype "bidirectional"))
    )
    (net (code "425") (name "unconnected-(IC15-ID-Pad3)") (class "Default")
      (node (ref "IC15") (pin "3") (pinfunction "ID_3") (pintype "bidirectional"))
    )
    (net (code "426") (name "unconnected-(IC15-NC-Pad5)") (class "Default")
      (node (ref "IC15") (pin "5") (pinfunction "NC_5") (pintype "bidirectional"))
    )
    (net (code "427") (name "unconnected-(IC19-NC{slash}ADJ-Pad4)") (class "Default")
      (node (ref "IC19") (pin "4") (pinfunction "NC/ADJ_4") (pintype "bidirectional"))
    )
    (net (code "428") (name "unconnected-(MOD1-GPIO4-Pad25)") (class "Default")
      (node (ref "MOD1") (pin "25") (pinfunction "GPIO4_25") (pintype "bidirectional"))
    )
    (net (code "429") (name "unconnected-(MOD1-GPIO9-Pad3)") (class "Default")
      (node (ref "MOD1") (pin "3") (pinfunction "GPIO9_3") (pintype "bidirectional"))
    )
    (net (code "430") (name "unconnected-(MOD1-GPIO10-Pad4)") (class "Default")
      (node (ref "MOD1") (pin "4") (pinfunction "GPIO10_4") (pintype "bidirectional"))
    )
    (net (code "431") (name "unconnected-(MOD1-GPIO11-Pad2)") (class "Default")
      (node (ref "MOD1") (pin "2") (pinfunction "GPIO11_2") (pintype "bidirectional"))
    )
    (net (code "432") (name "unconnected-(MOD1-GPIO12-Pad5)") (class "Default")
      (node (ref "MOD1") (pin "5") (pinfunction "GPIO12_5") (pintype "bidirectional"))
    )
    (net (code "433") (name "unconnected-(MOD1-RESERVED1-Pad21)") (class "Default")
      (node (ref "MOD1") (pin "21") (pinfunction "RESERVED1_21") (pintype "bidirectional"))
    )
    (net (code "434") (name "unconnected-(MOD1-RESERVED2-Pad22)") (class "Default")
      (node (ref "MOD1") (pin "22") (pinfunction "RESERVED2_22") (pintype "bidirectional"))
    )
    (net (code "435") (name "unconnected-(MOD1-RESERVED3-Pad62)") (class "Default")
      (node (ref "MOD1") (pin "62") (pinfunction "RESERVED3_62") (pintype "bidirectional"))
    )
    (net (code "436") (name "unconnected-(P2-NC-Pad6)") (class "Default")
      (node (ref "P2") (pin "6") (pinfunction "NC_6") (pintype "bidirectional"))
    )
    (net (code "437") (name "unconnected-(X1-Pad2)") (class "Default")
      (node (ref "X1") (pin "2") (pinfunction "2_2") (pintype "passive"))
    )
    (net (code "438") (name "unconnected-(X1-Pad3)") (class "Default")
      (node (ref "X1") (pin "3") (pinfunction "3_3") (pintype "passive"))
    )
    (net (code "439") (name "unconnected-(X1-Pad6)") (class "Default")
      (node (ref "X1") (pin "6") (pinfunction "6_6") (pintype "passive"))
    )
    (net (code "440") (name "unconnected-(X5-NC-Pad2)") (class "Default")
      (node (ref "X5") (pin "2") (pinfunction "NC_2") (pintype "bidirectional"))
    )
    (net (code "441") (name "unconnected-(X12-PadOUT_CON)") (class "Default")
      (node (ref "X12") (pin "OUT_CON") (pinfunction "OUT_CON_OUT_CON") (pintype "bidirectional"))
    )
  )
)
